# pre-io.net
KiCad netlist of a schematic drawn in EAGLE
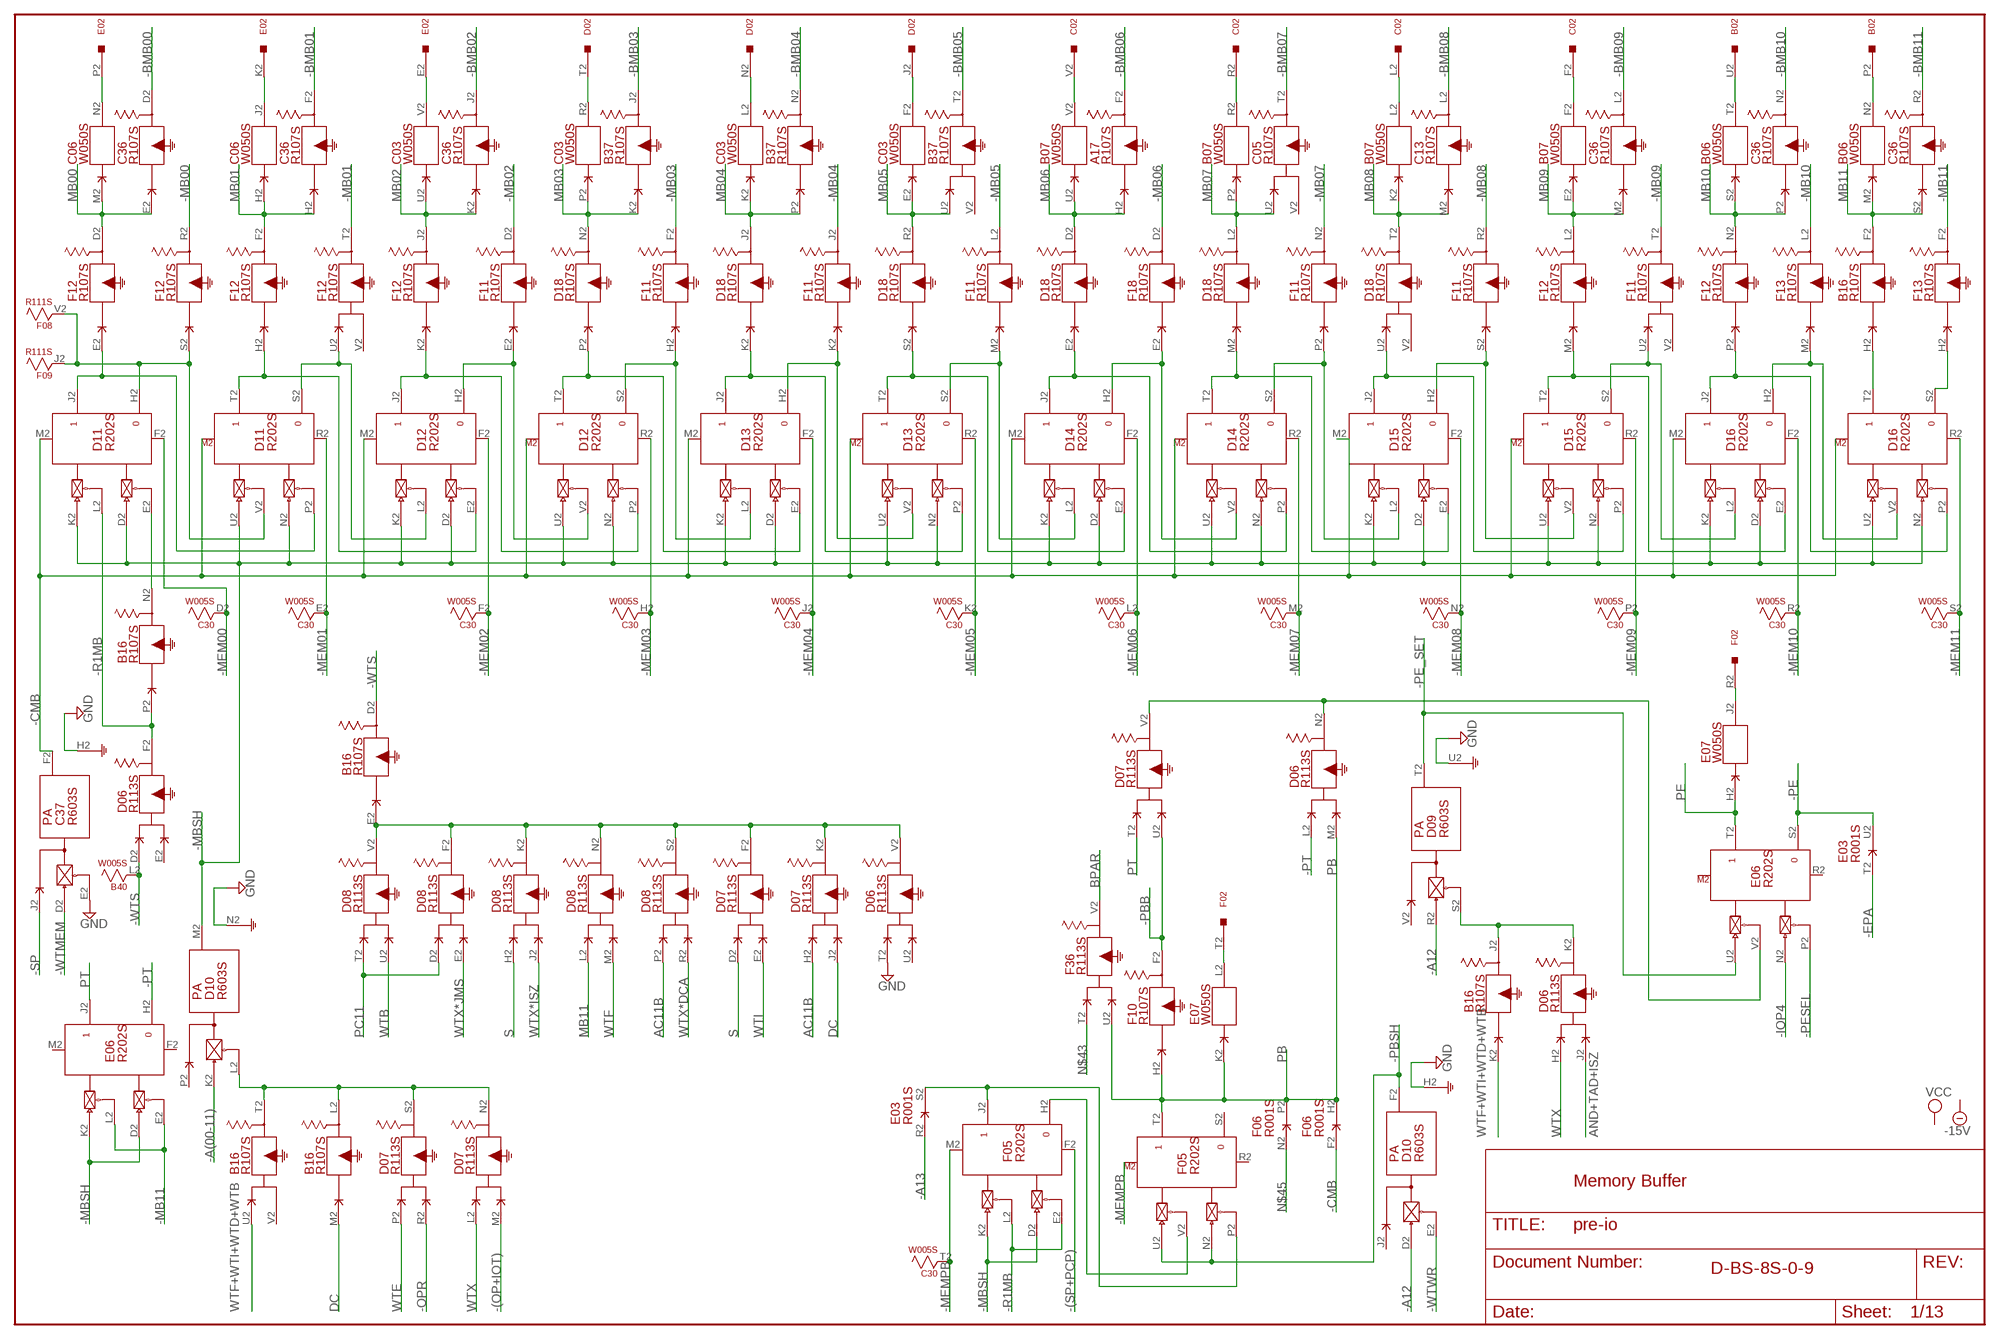
[diagram p0: schematic, sheet 1]
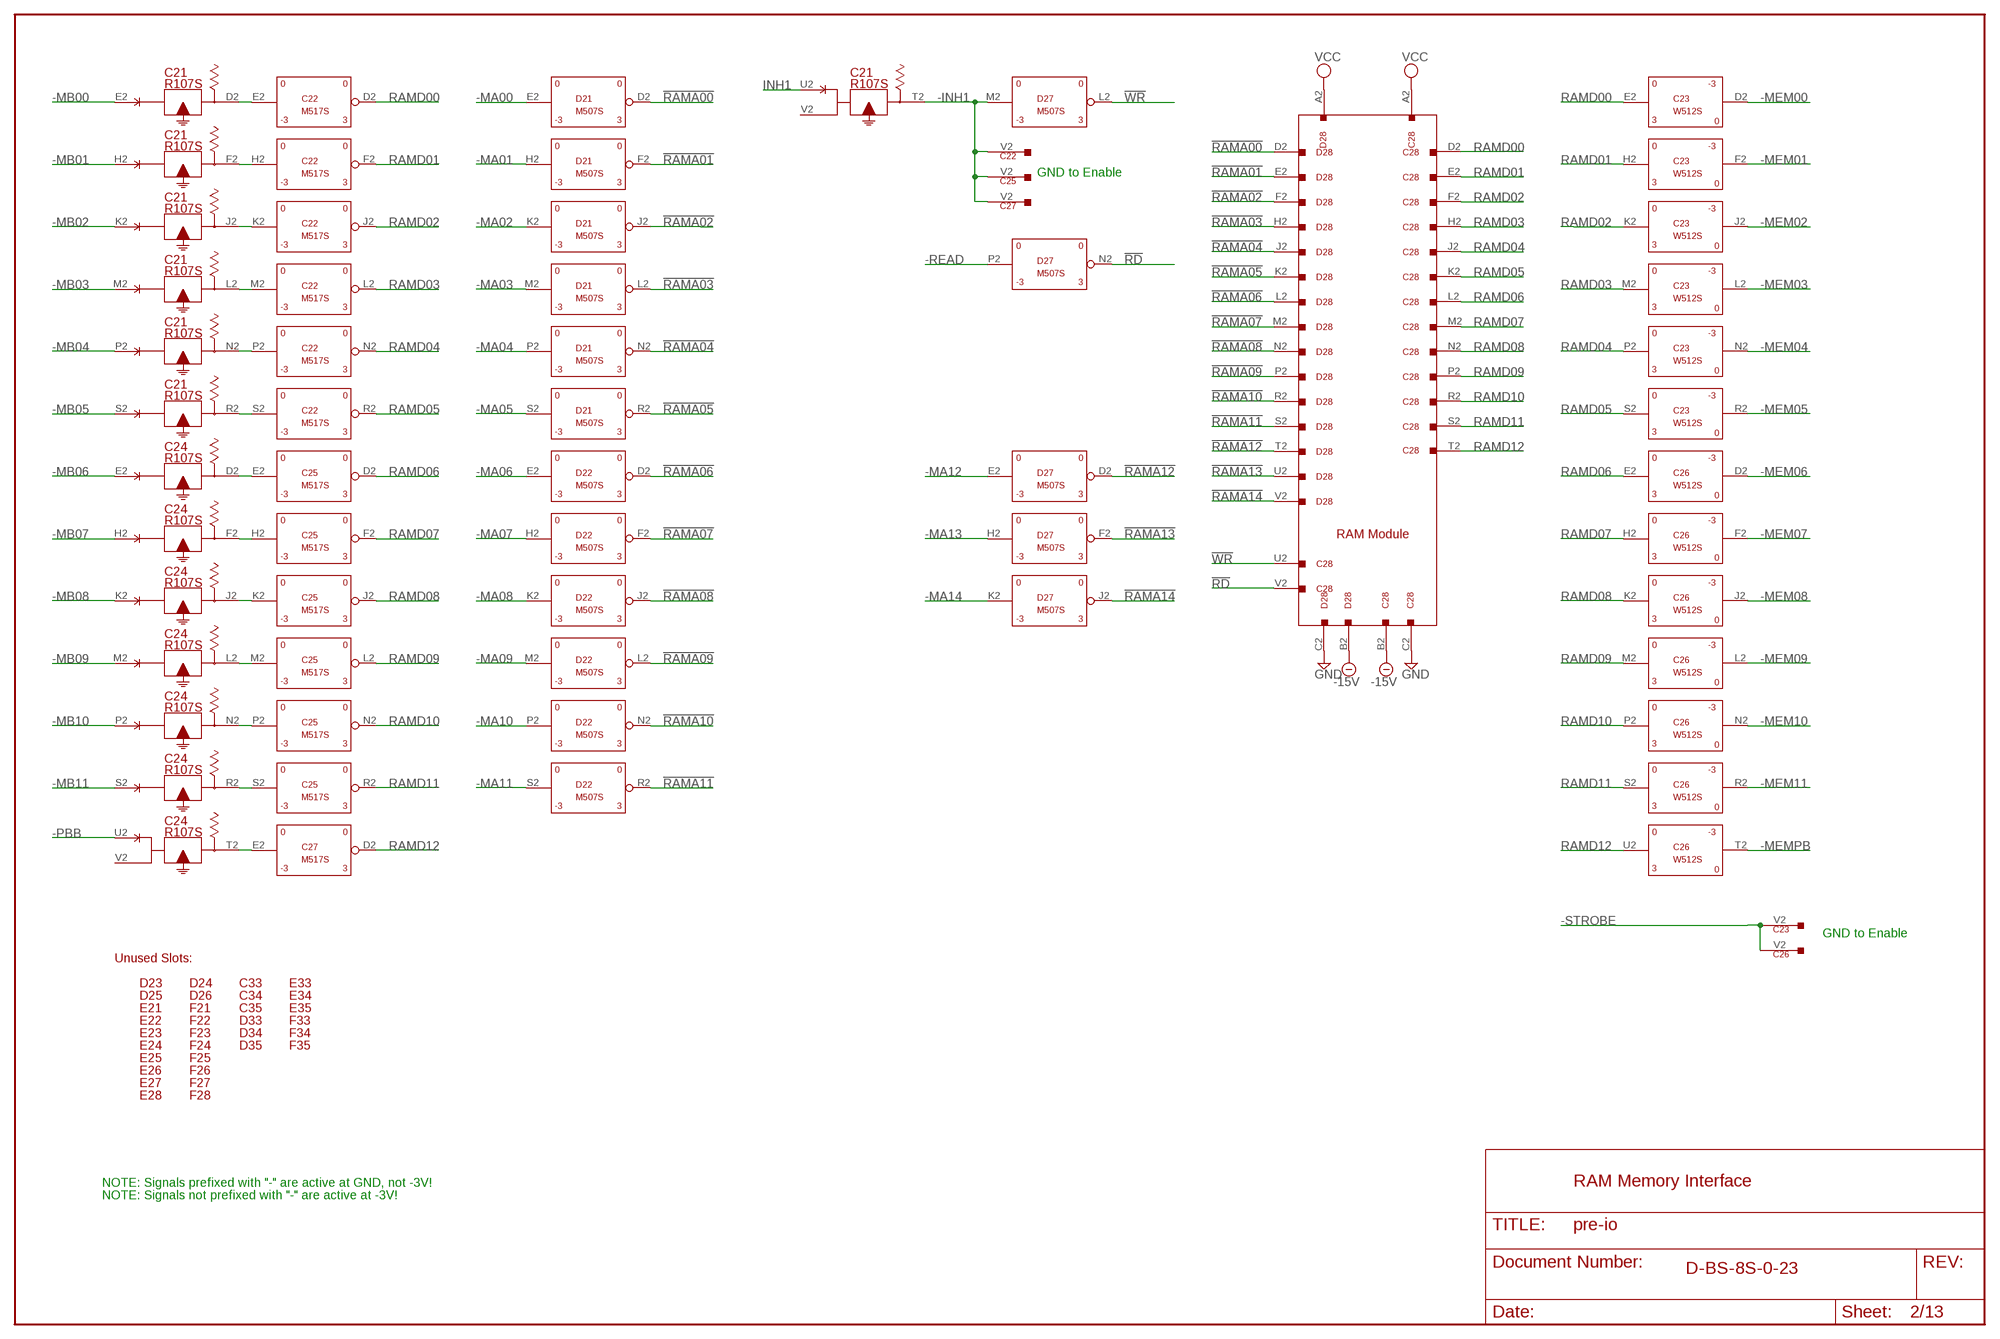
[diagram p1: schematic, sheet 2]
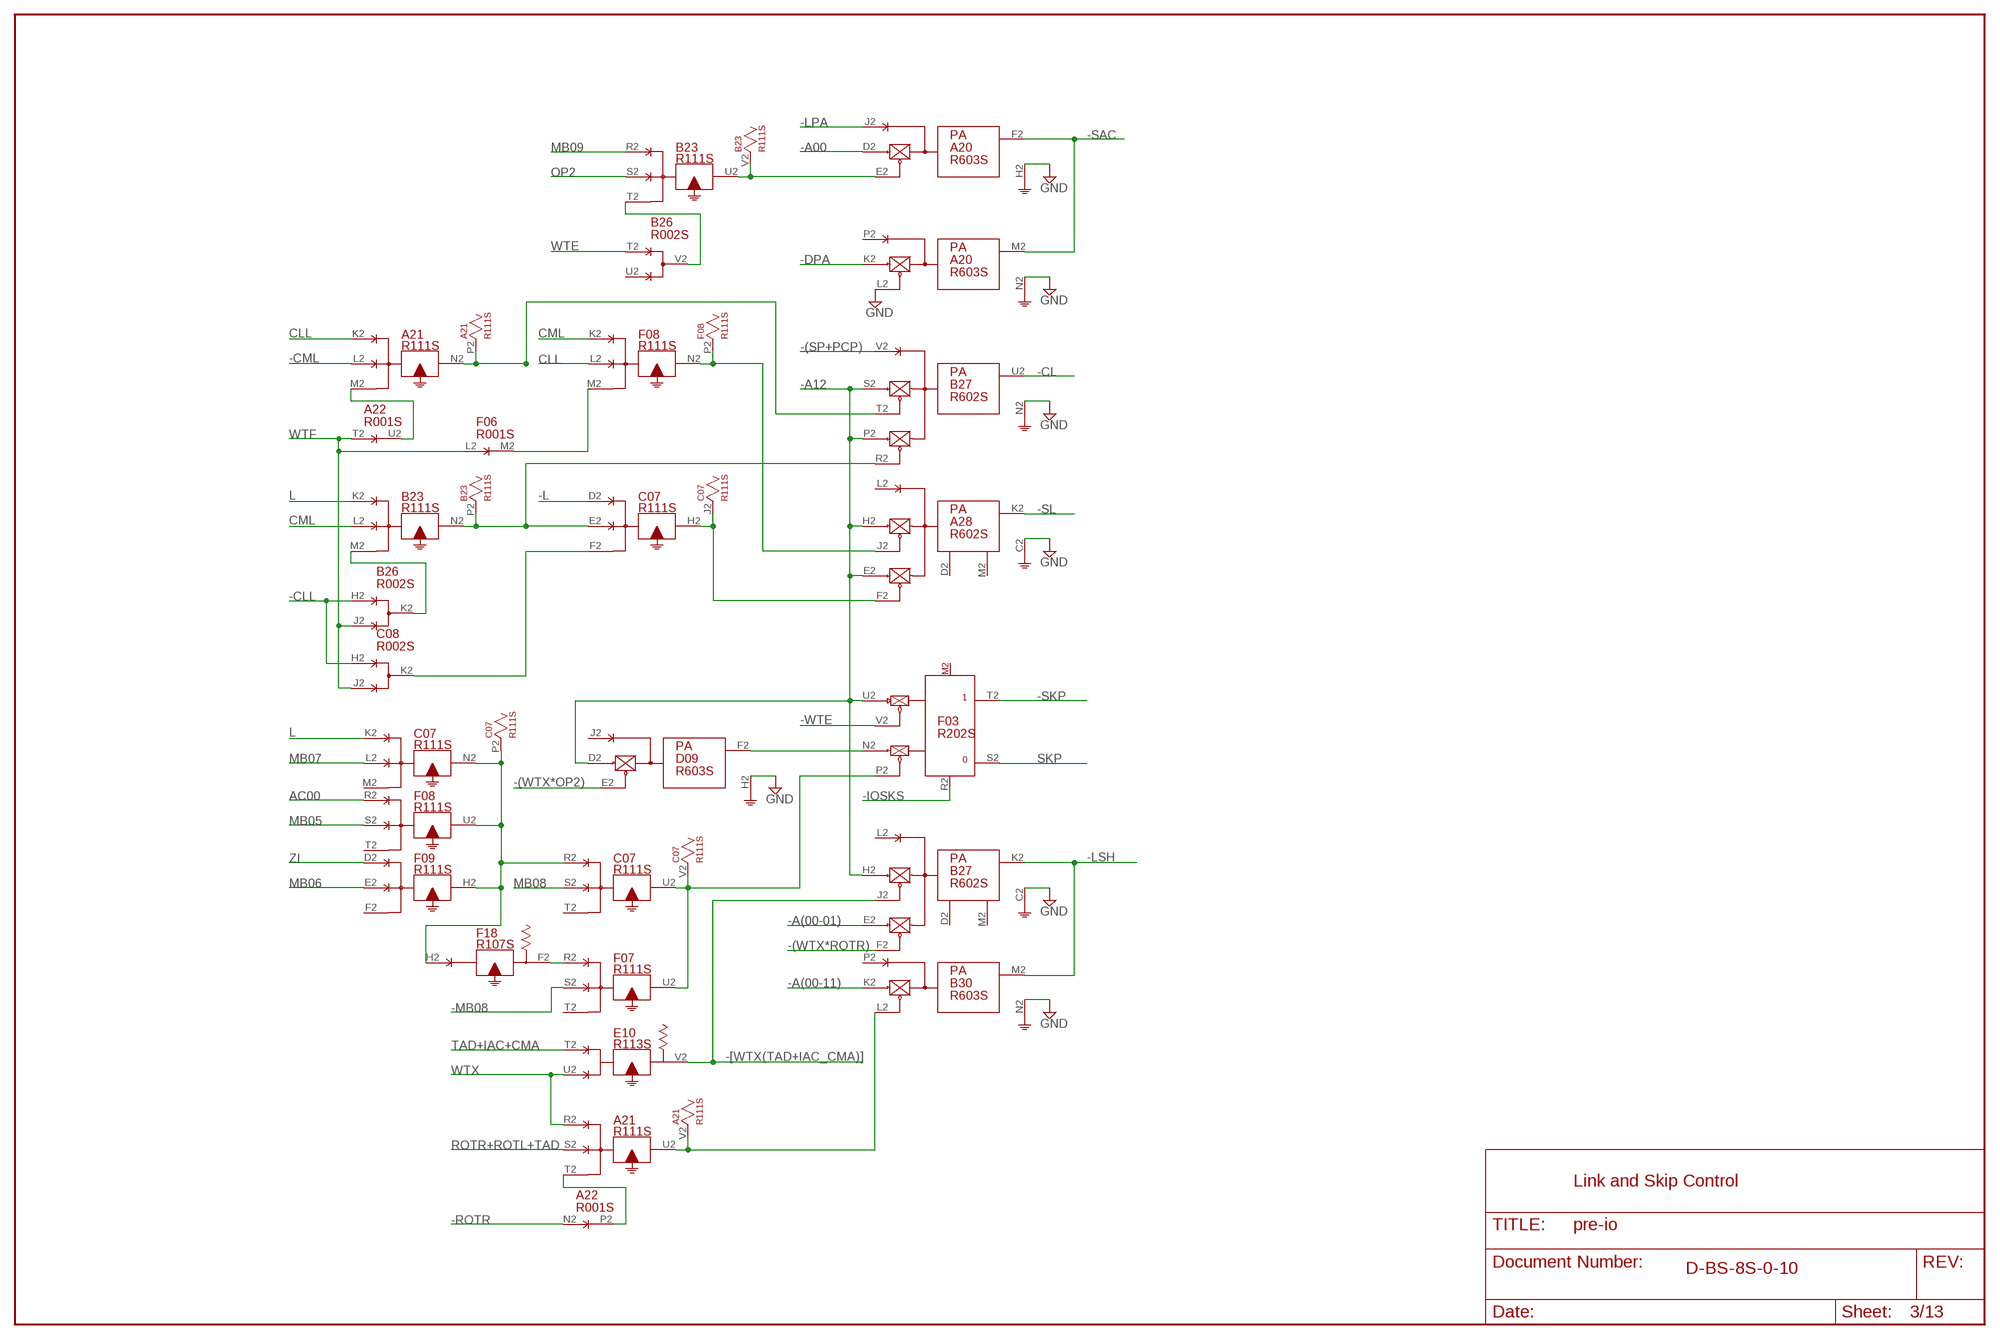
[diagram p2: schematic, sheet 3]
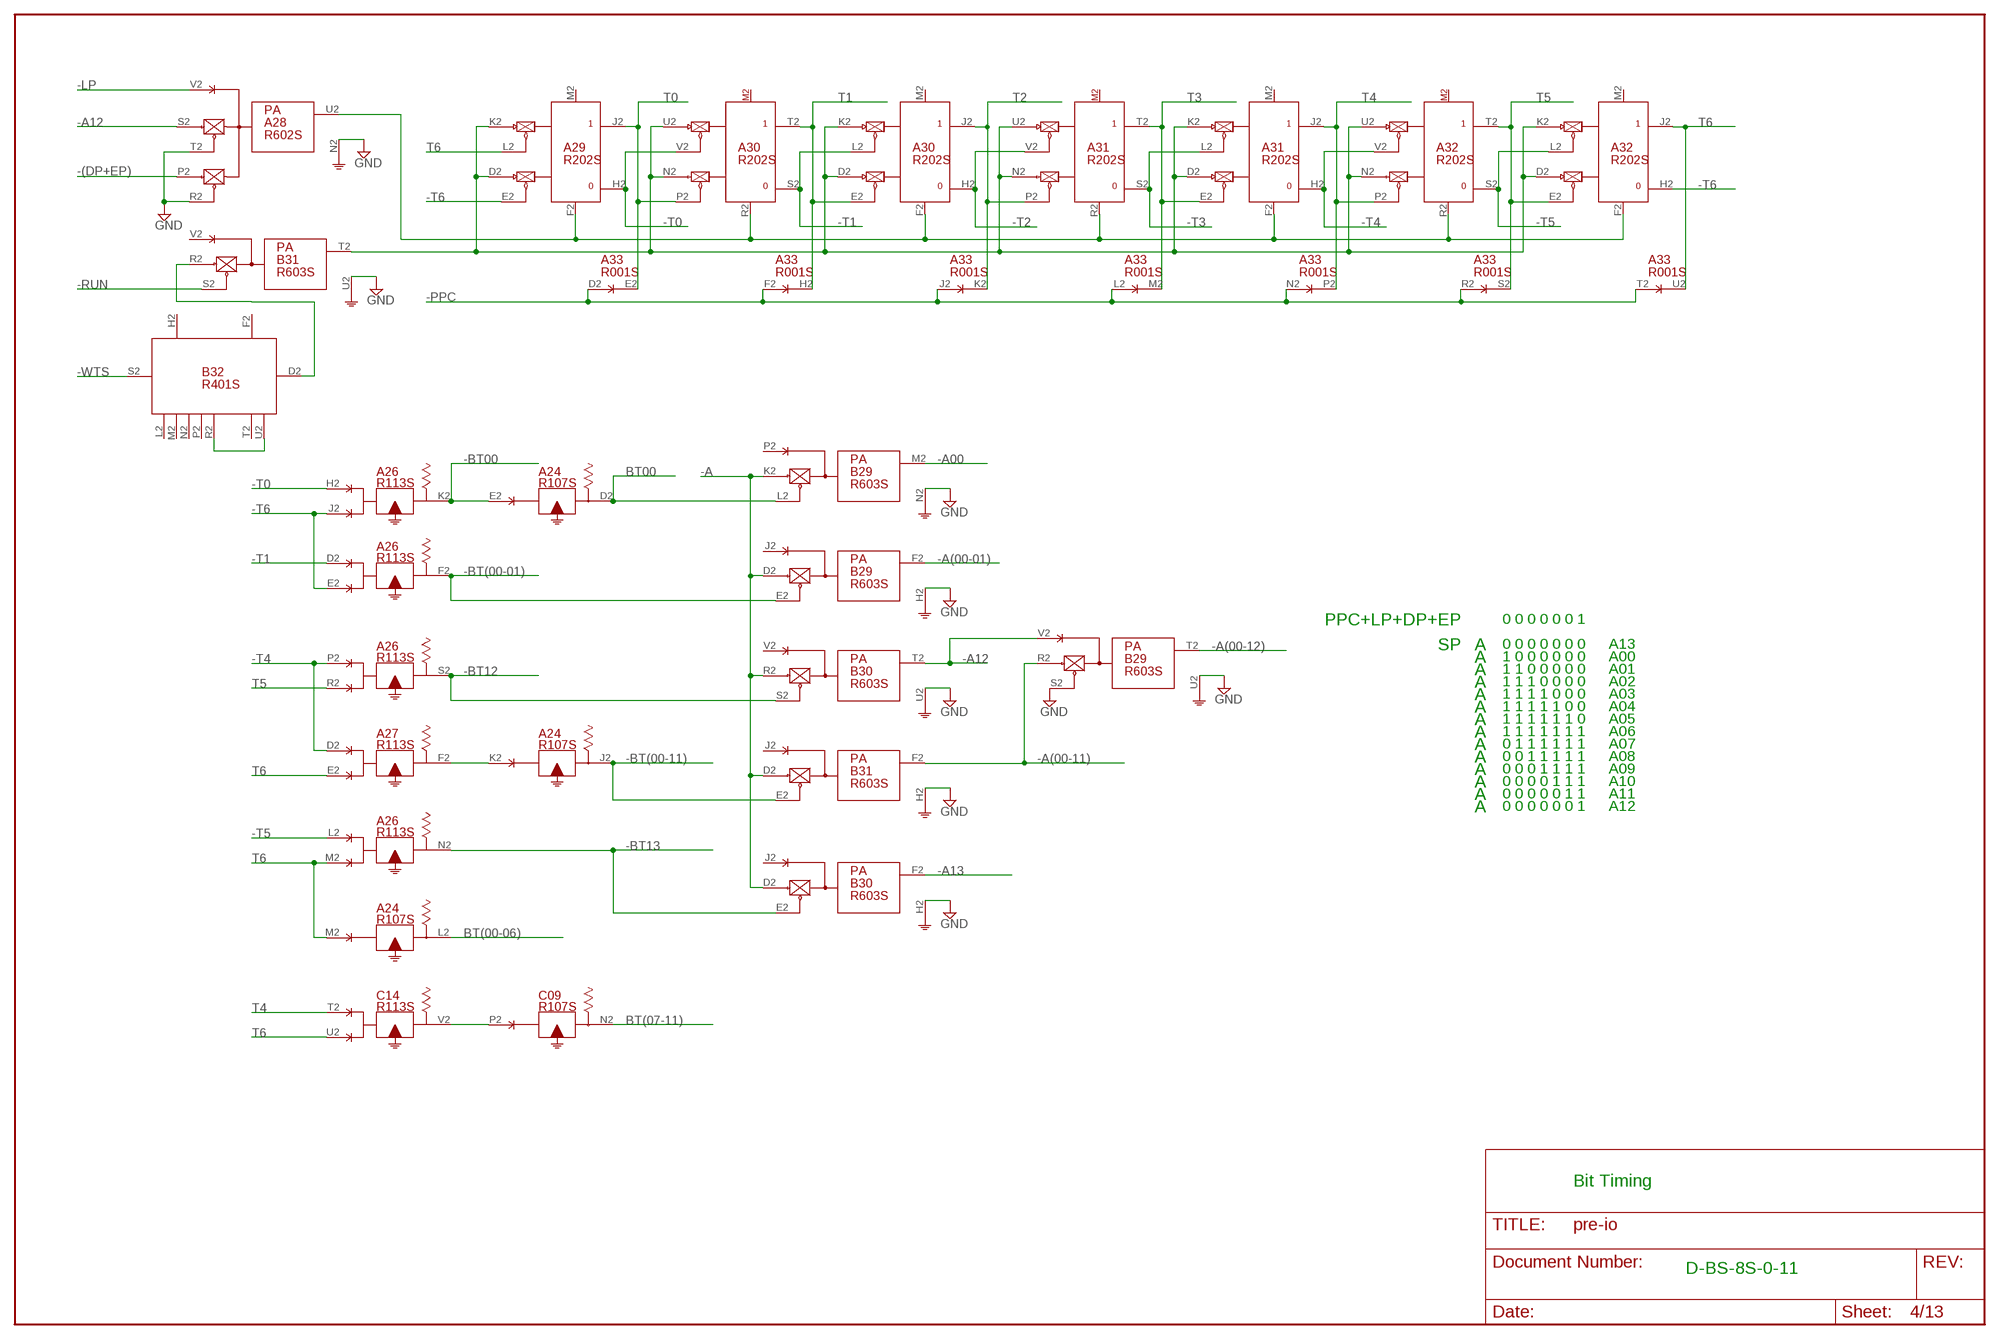
[diagram p3: schematic, sheet 4]
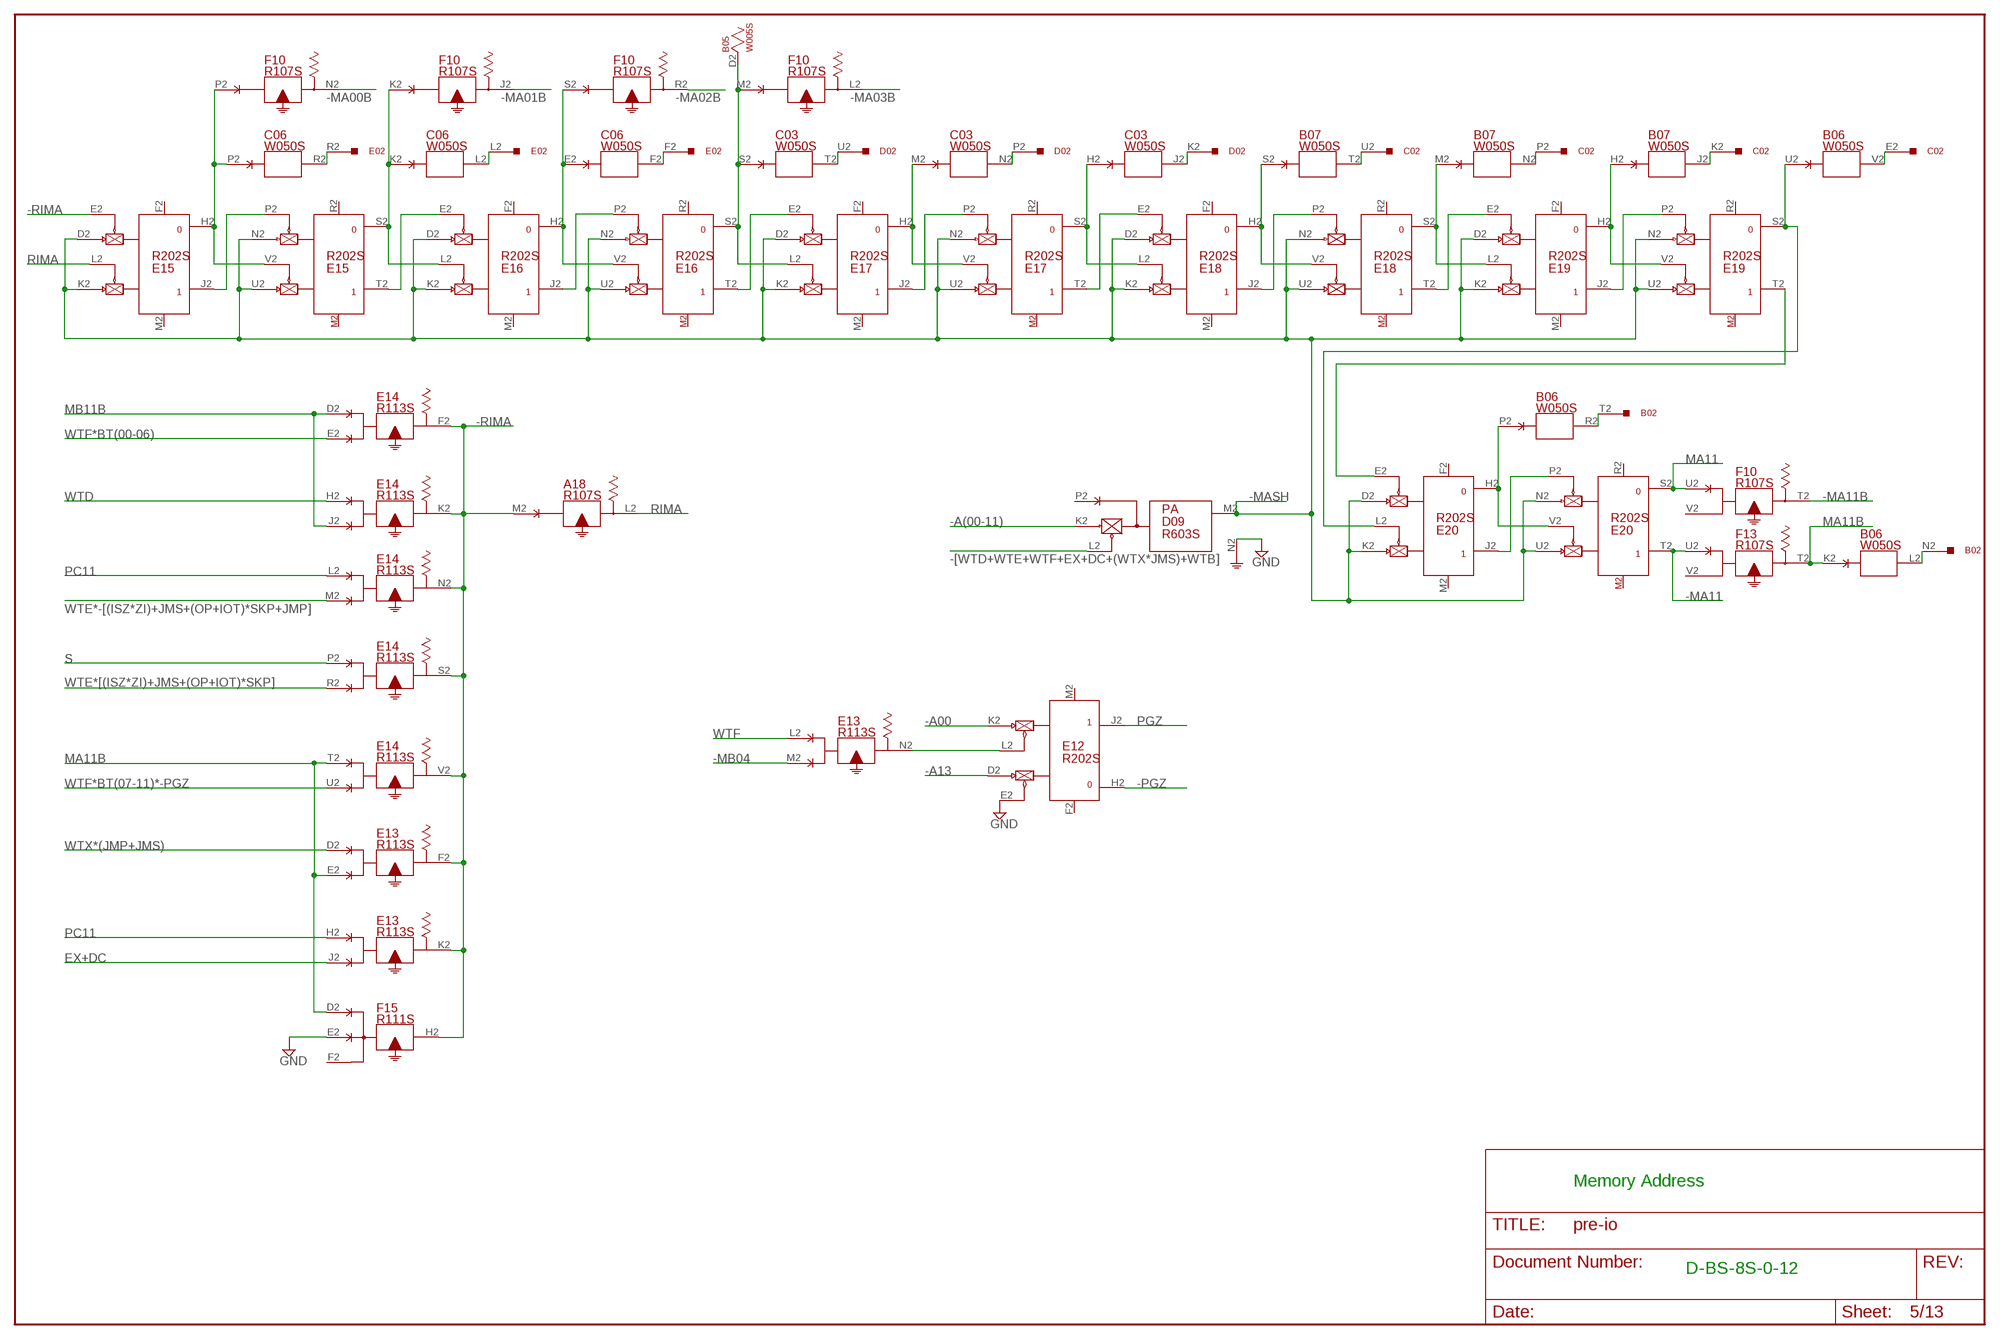
[diagram p4: schematic, sheet 5]
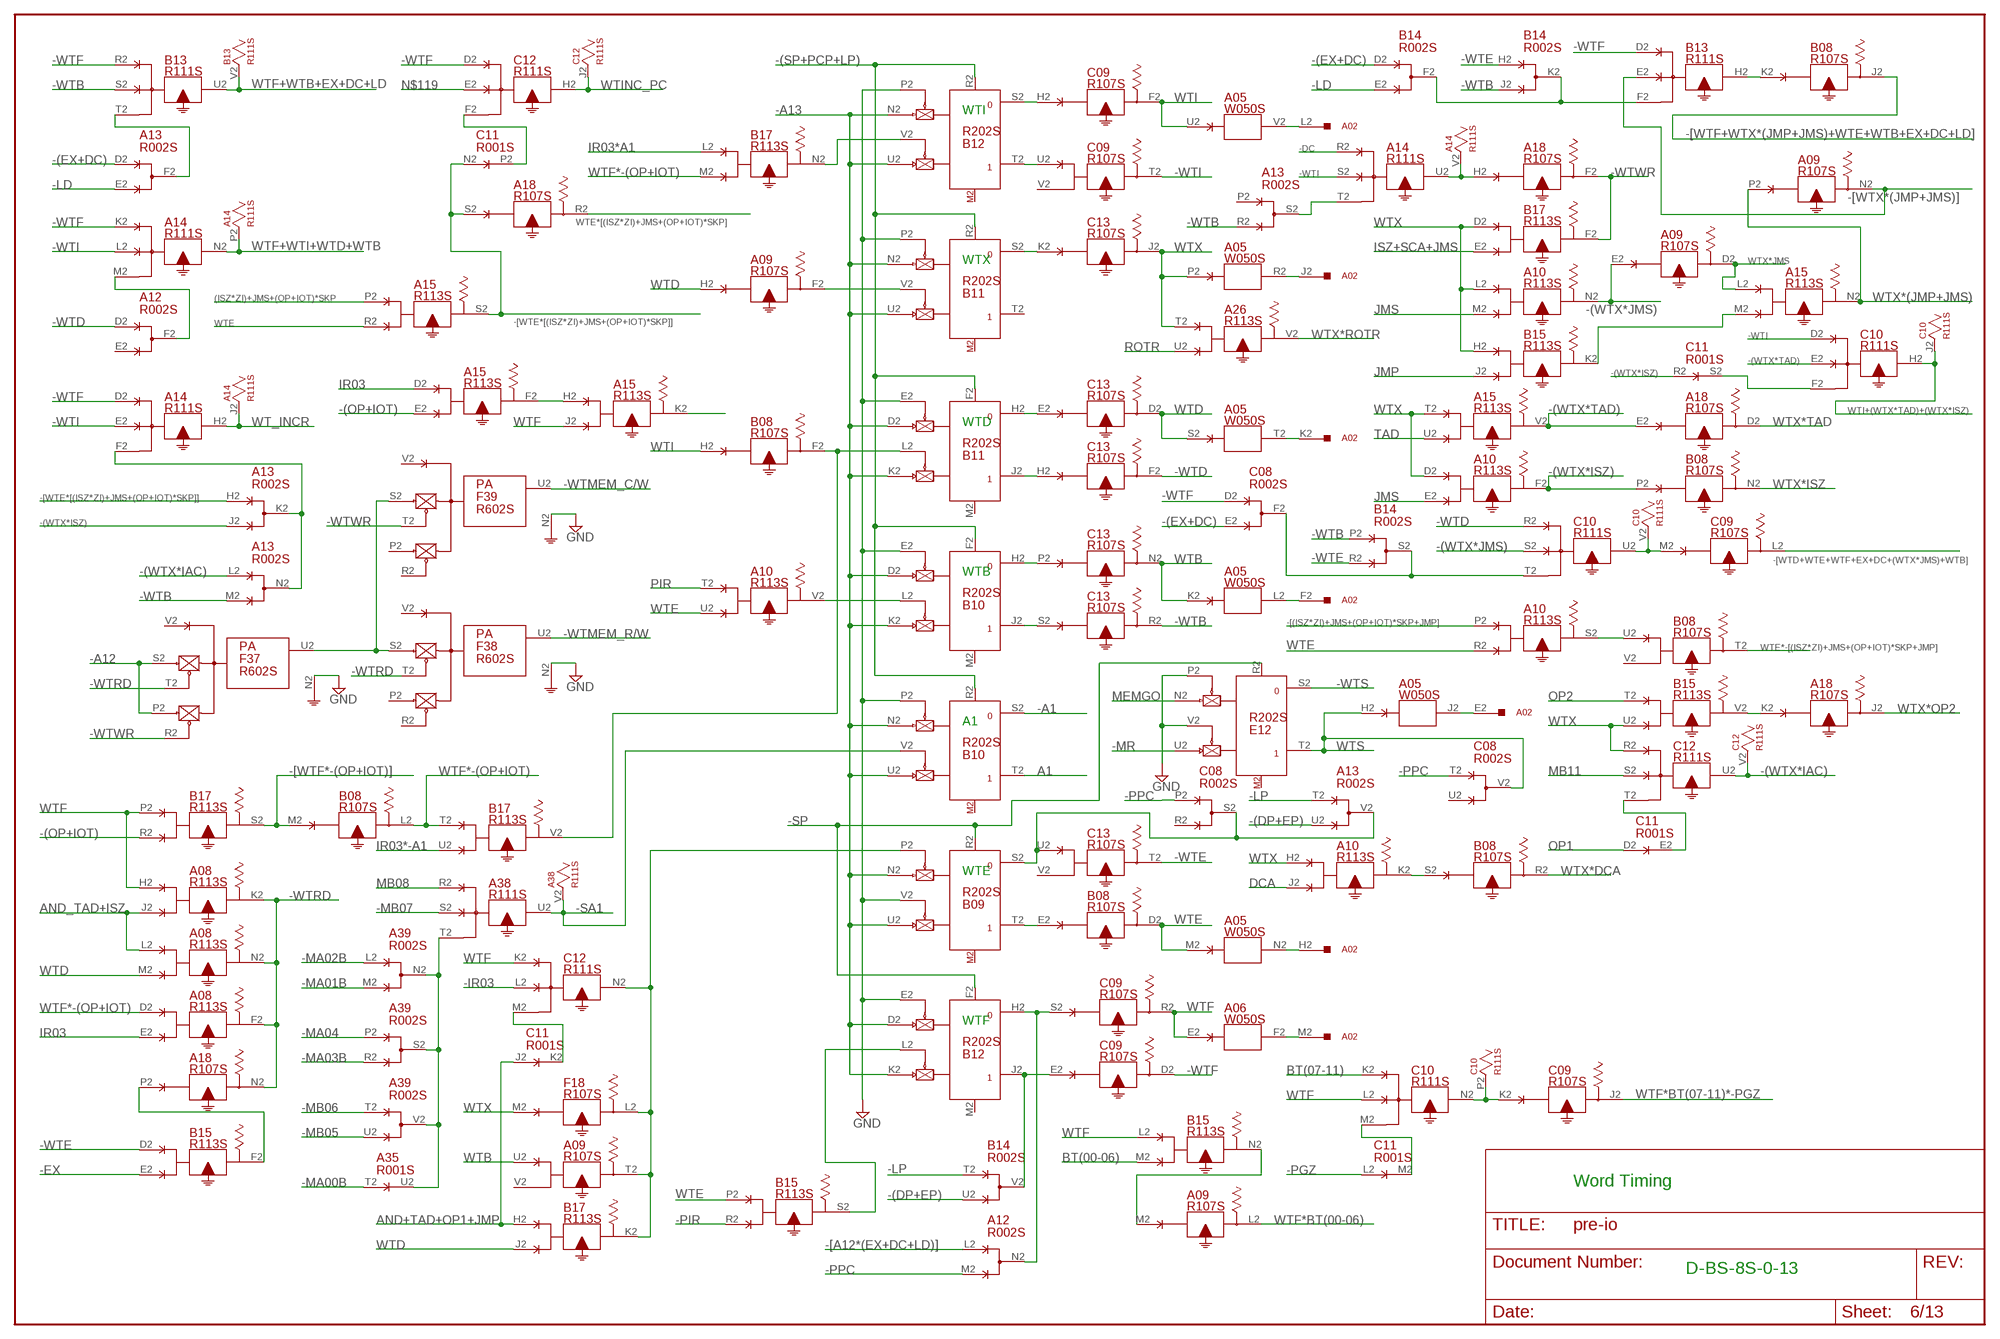
[diagram p5: schematic, sheet 6]
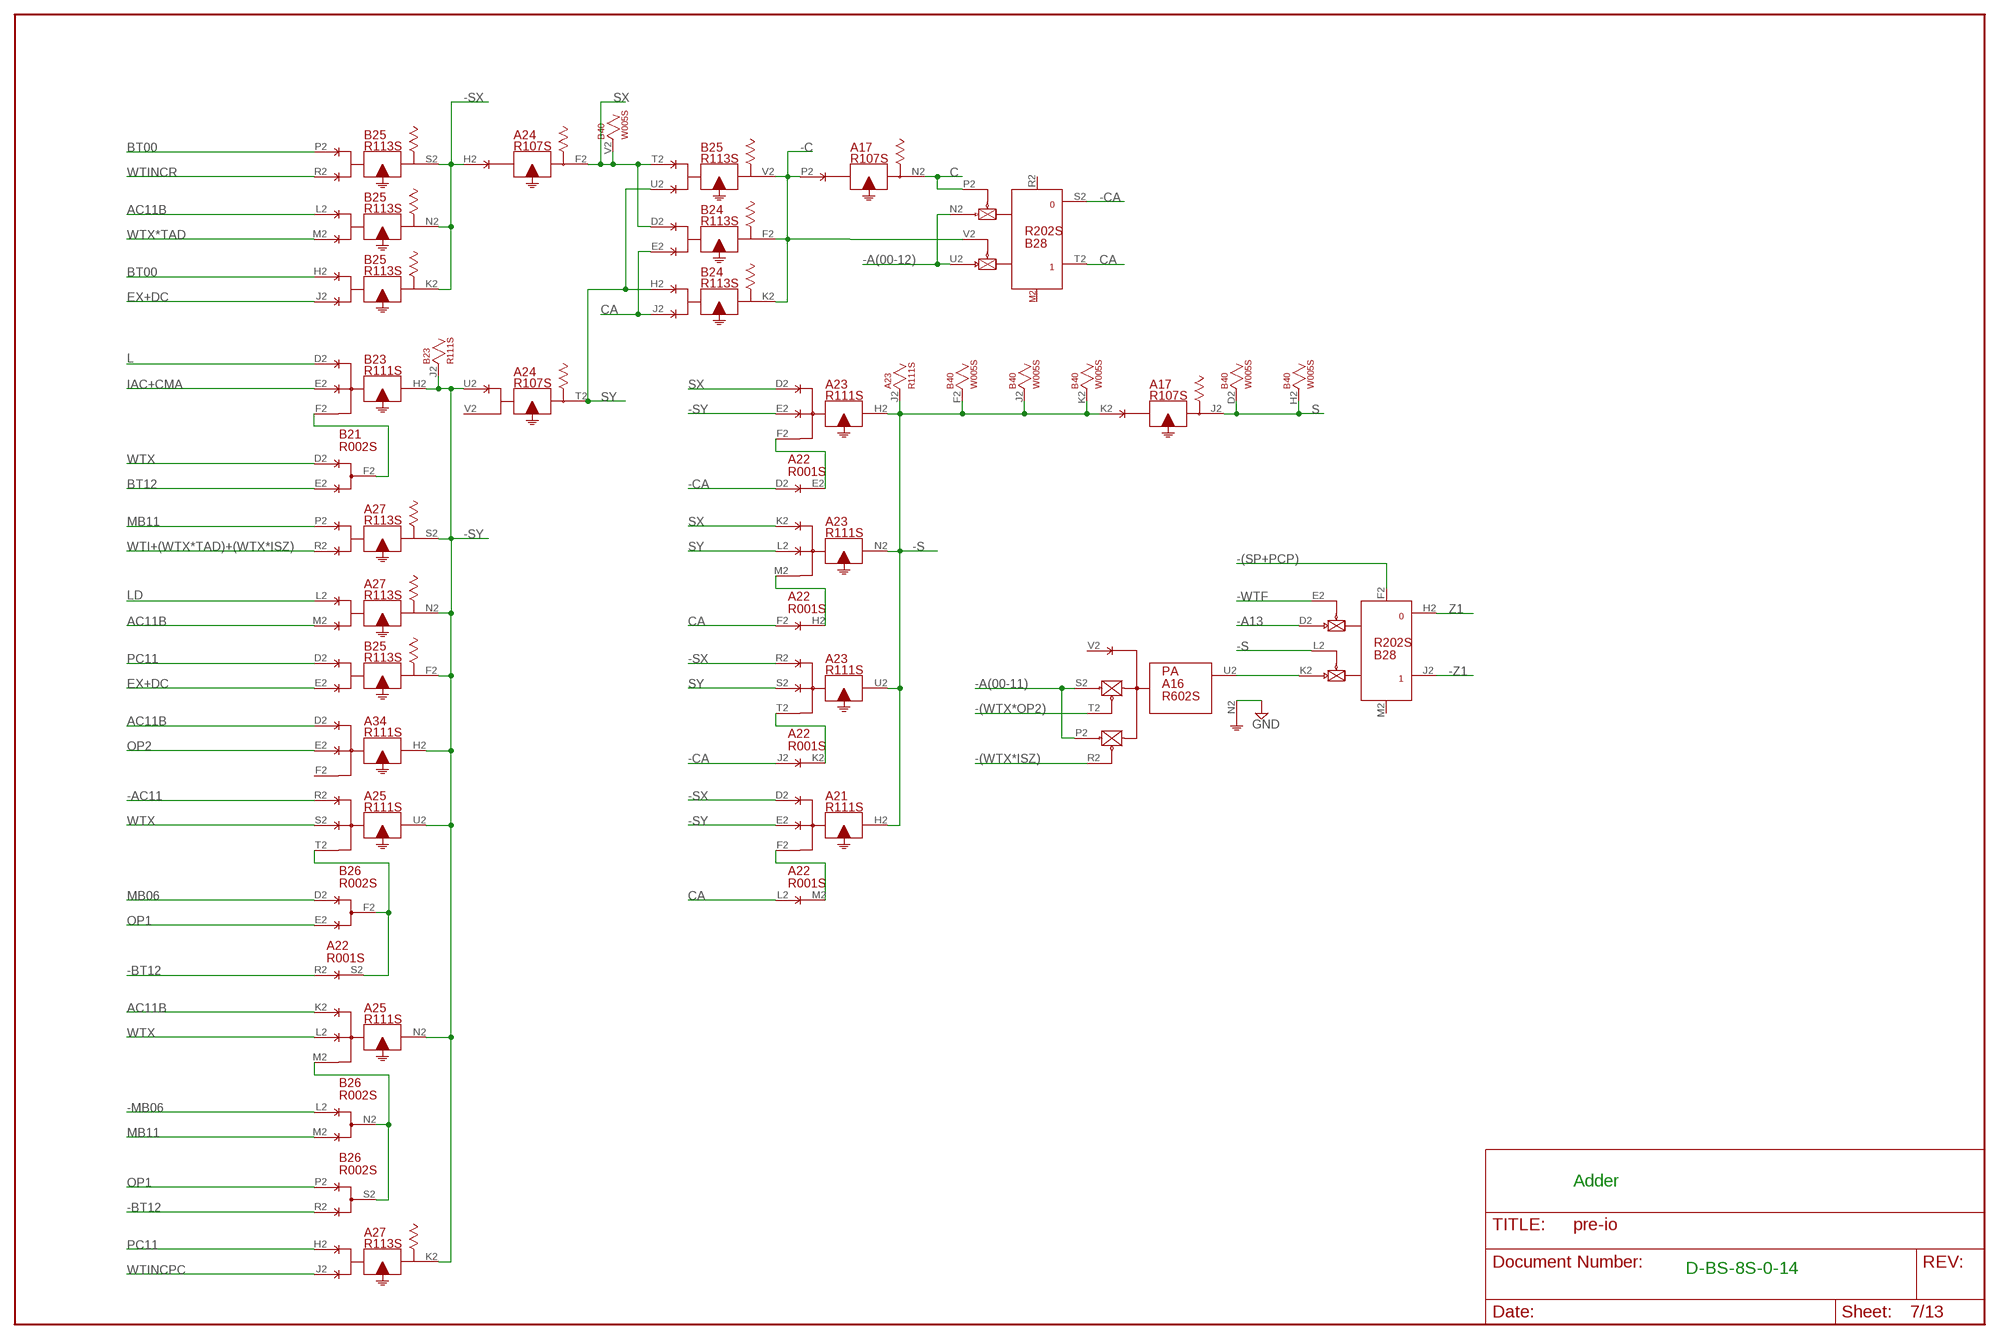
[diagram p6: schematic, sheet 7]
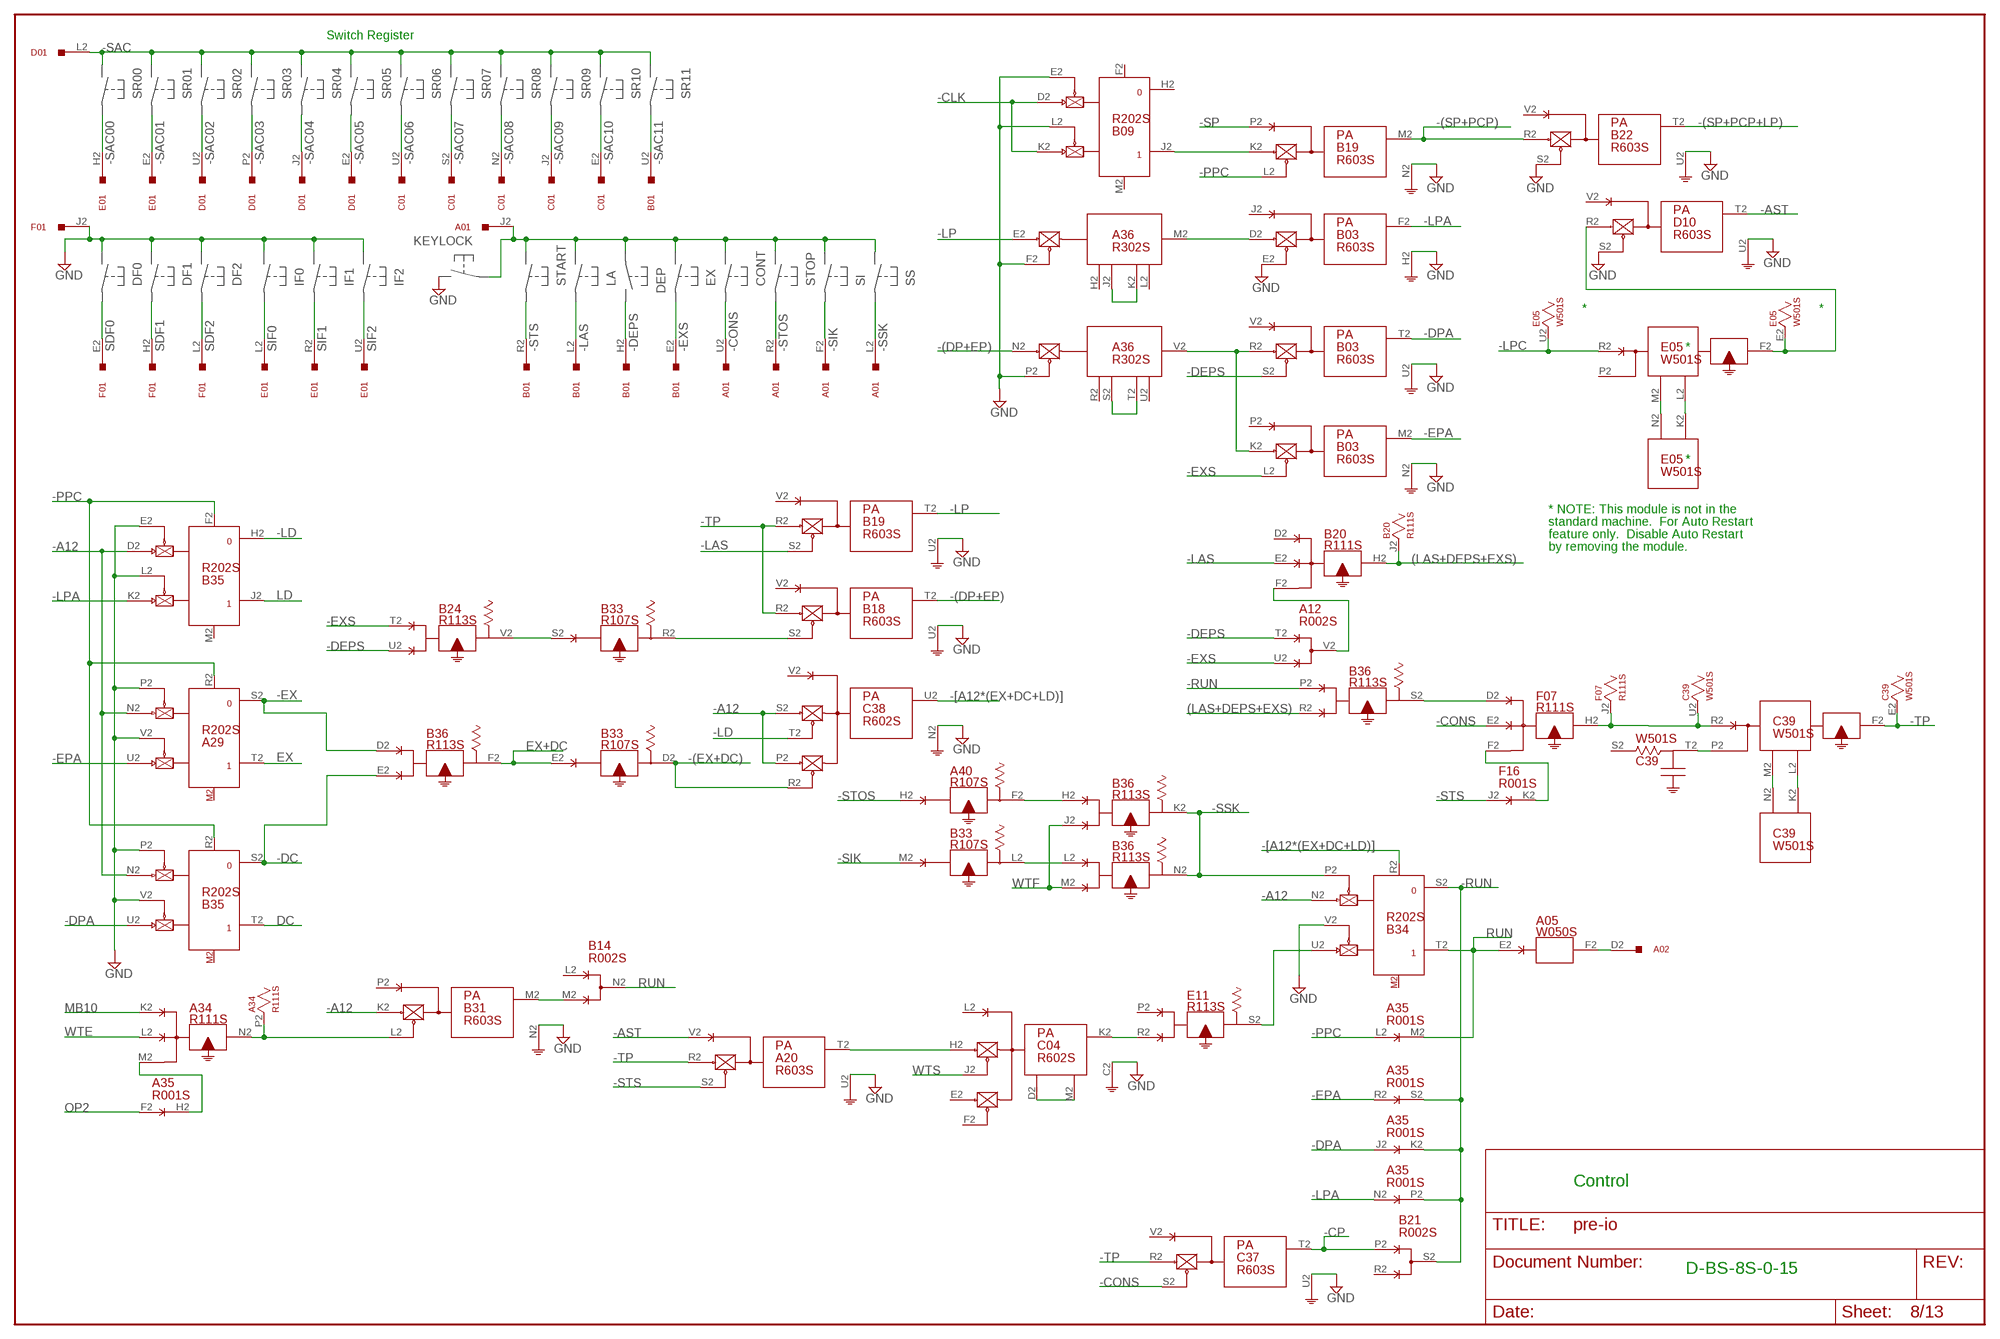
[diagram p7: schematic, sheet 8]
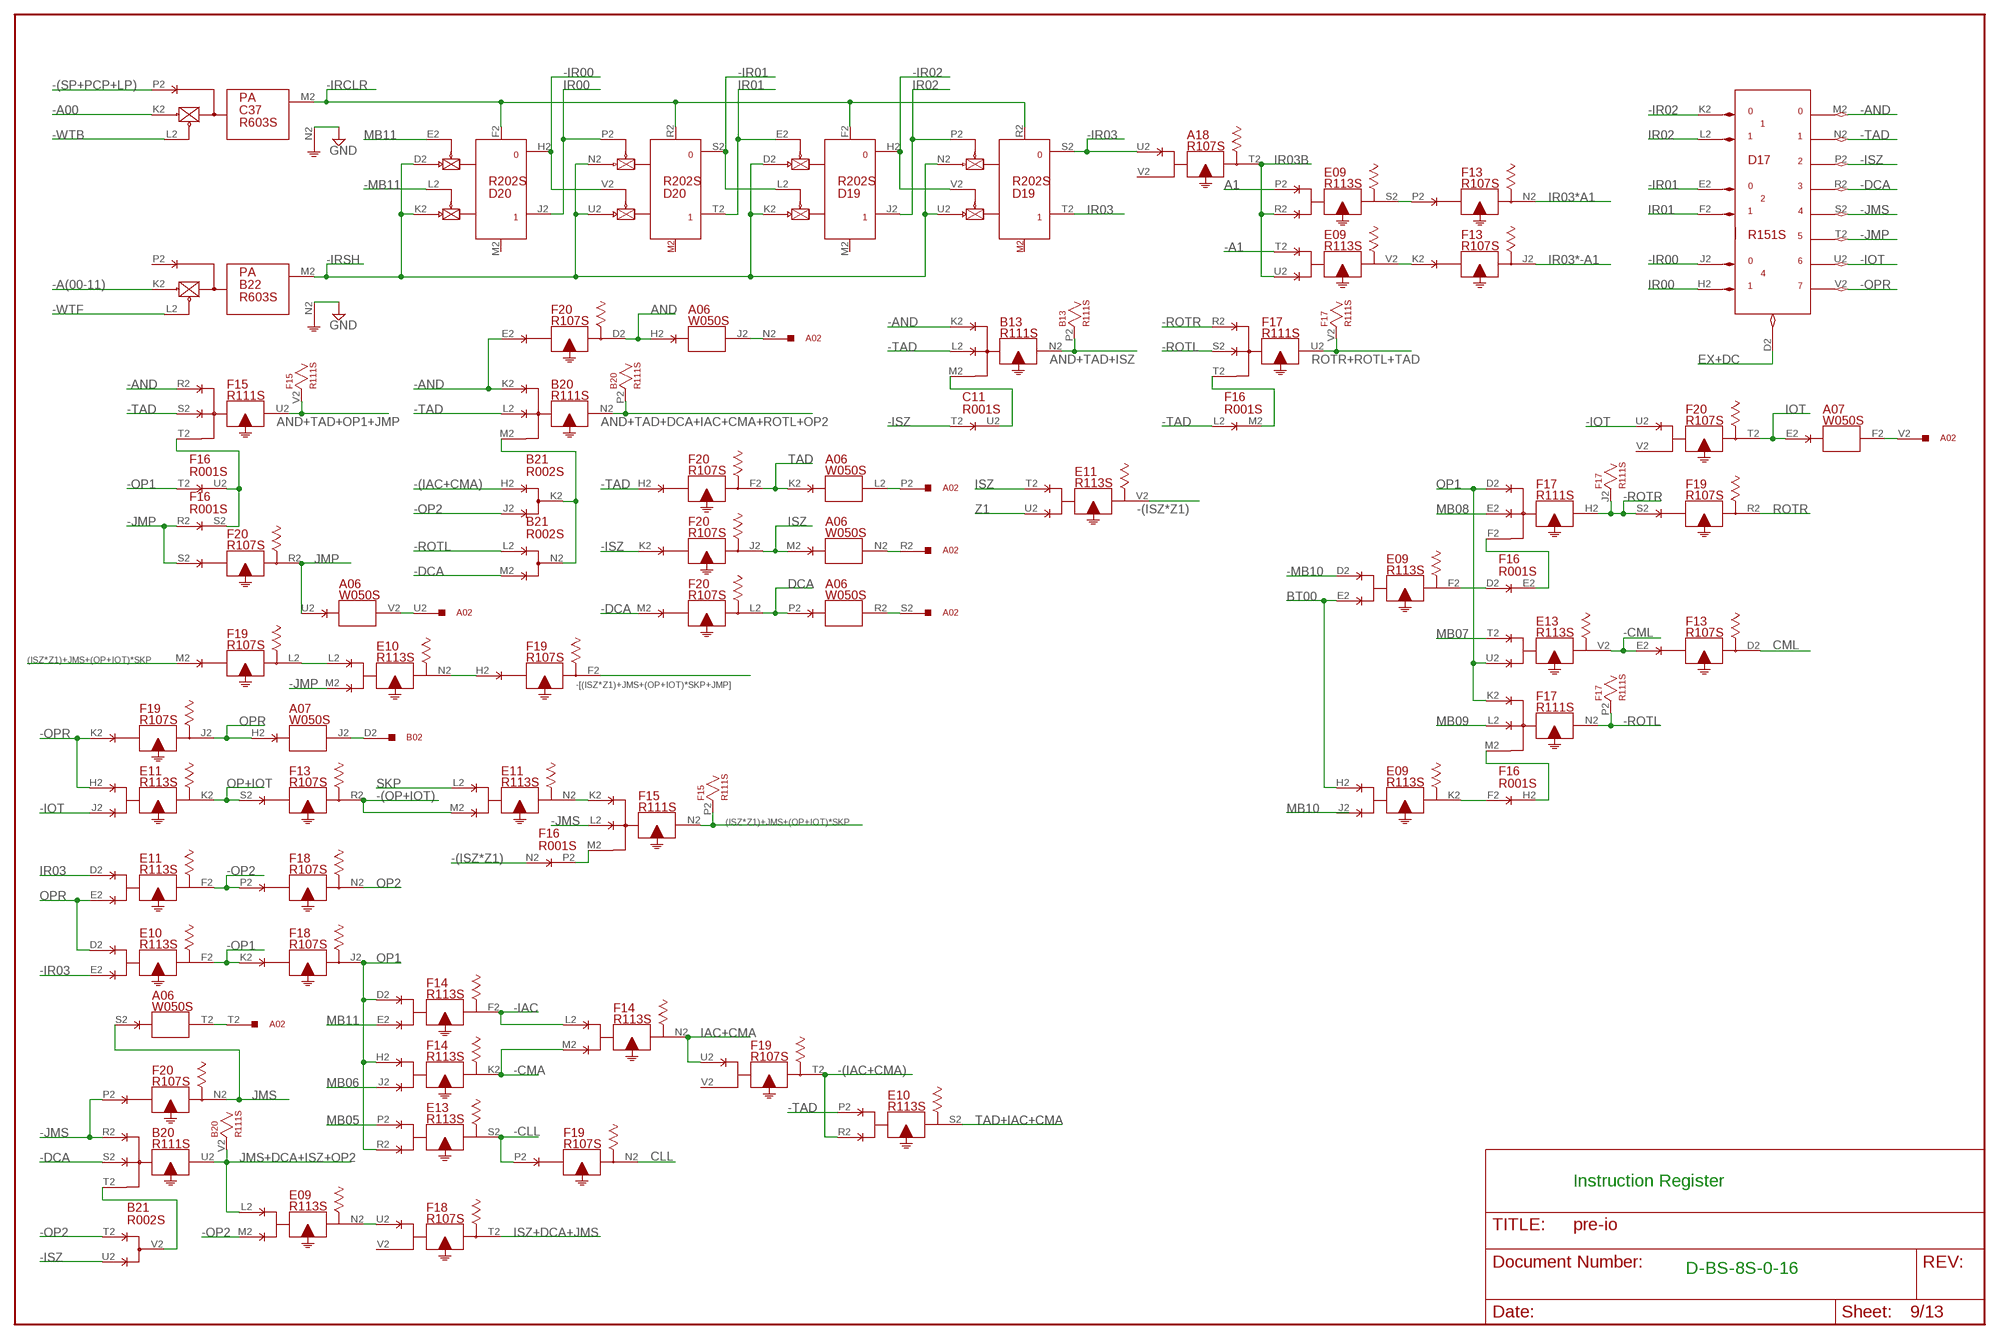
[diagram p8: schematic, sheet 9]
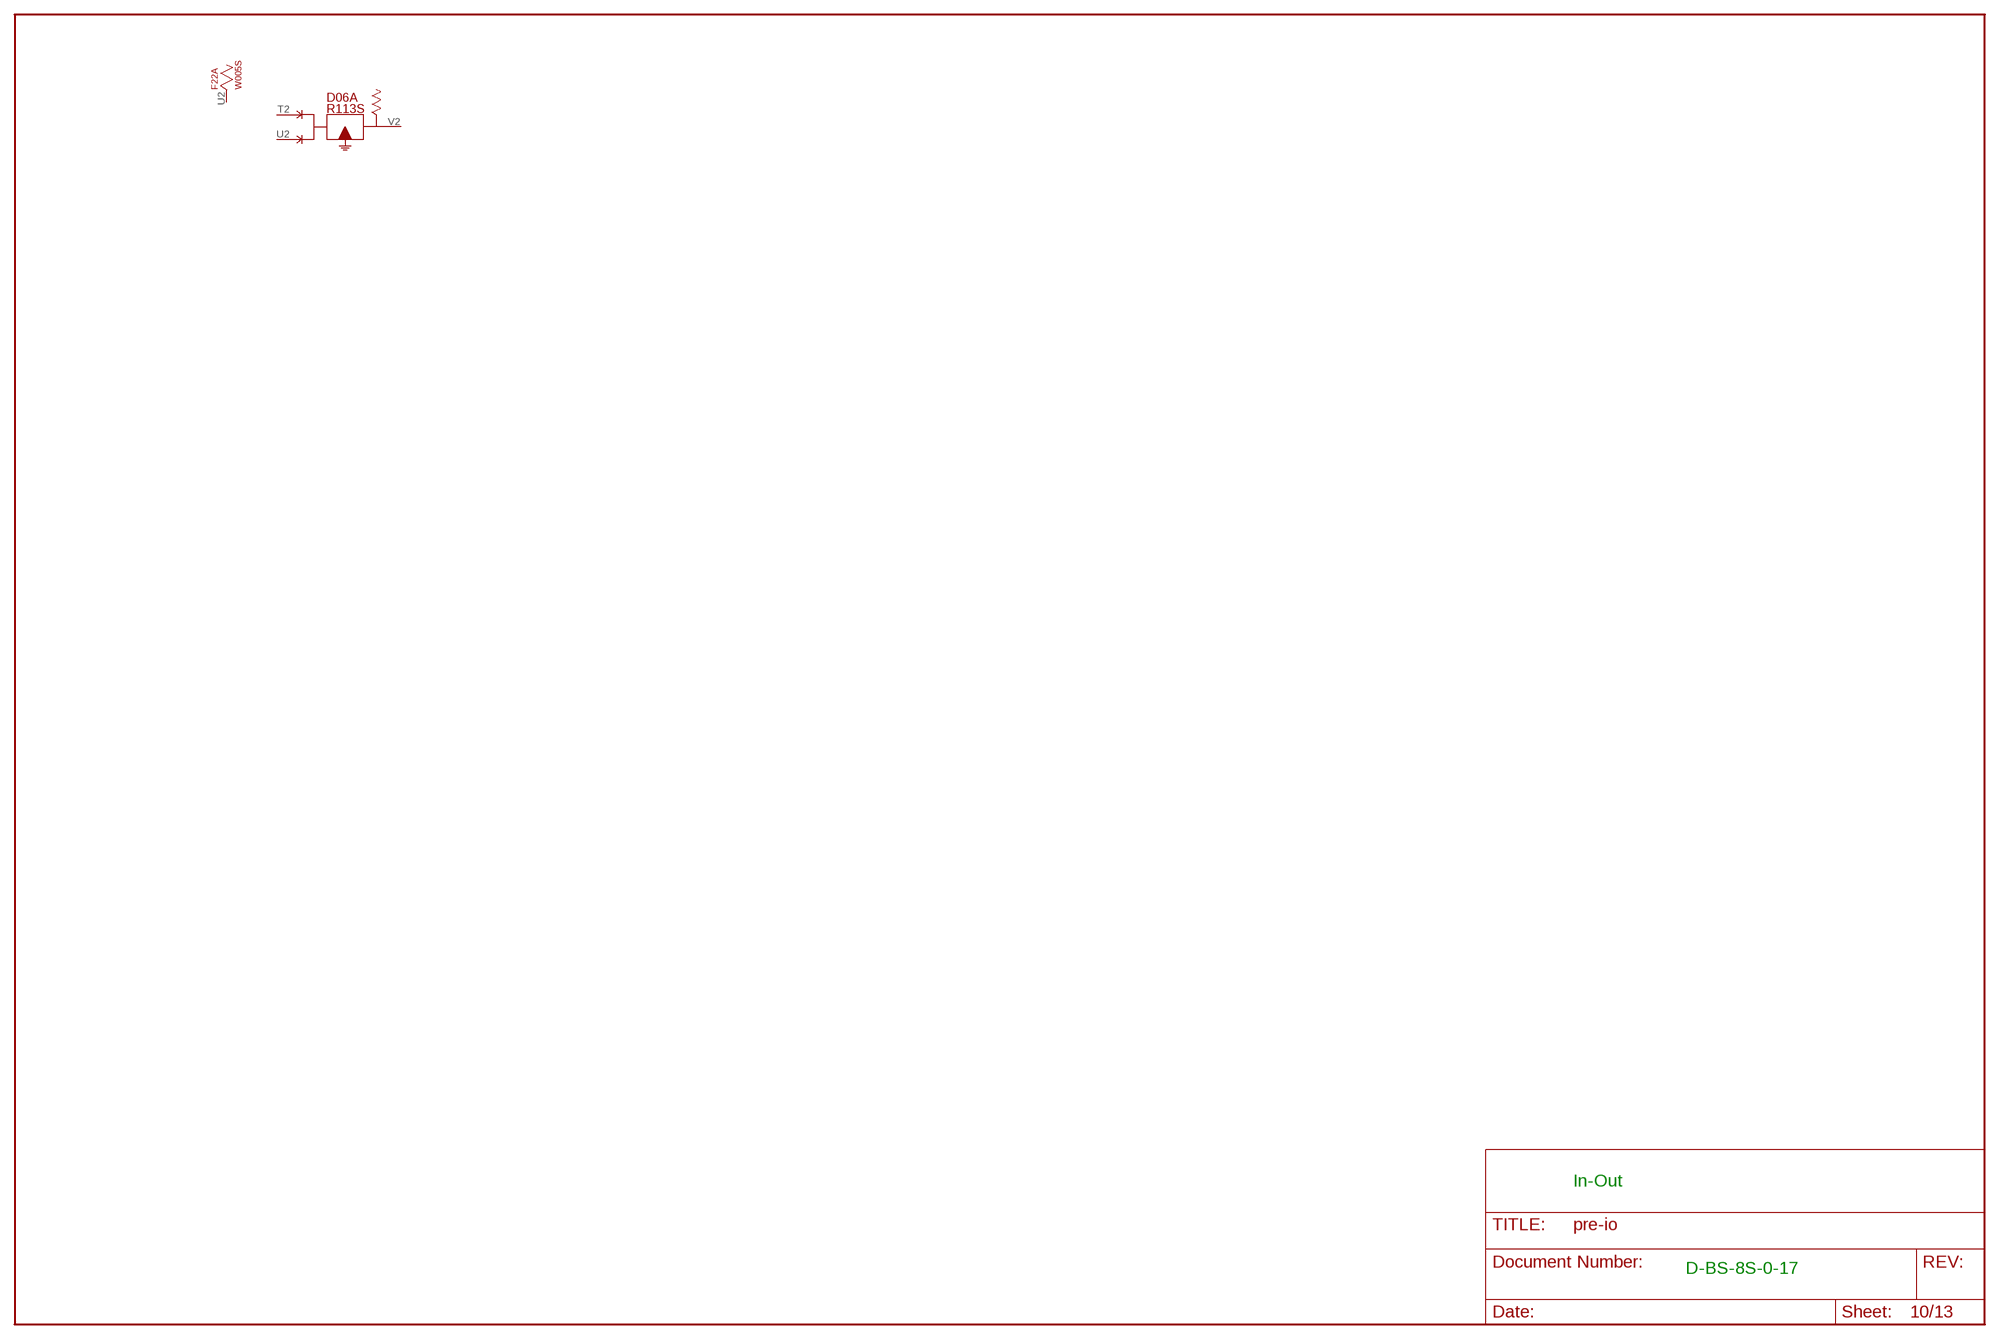
[diagram p9: schematic, sheet 10]
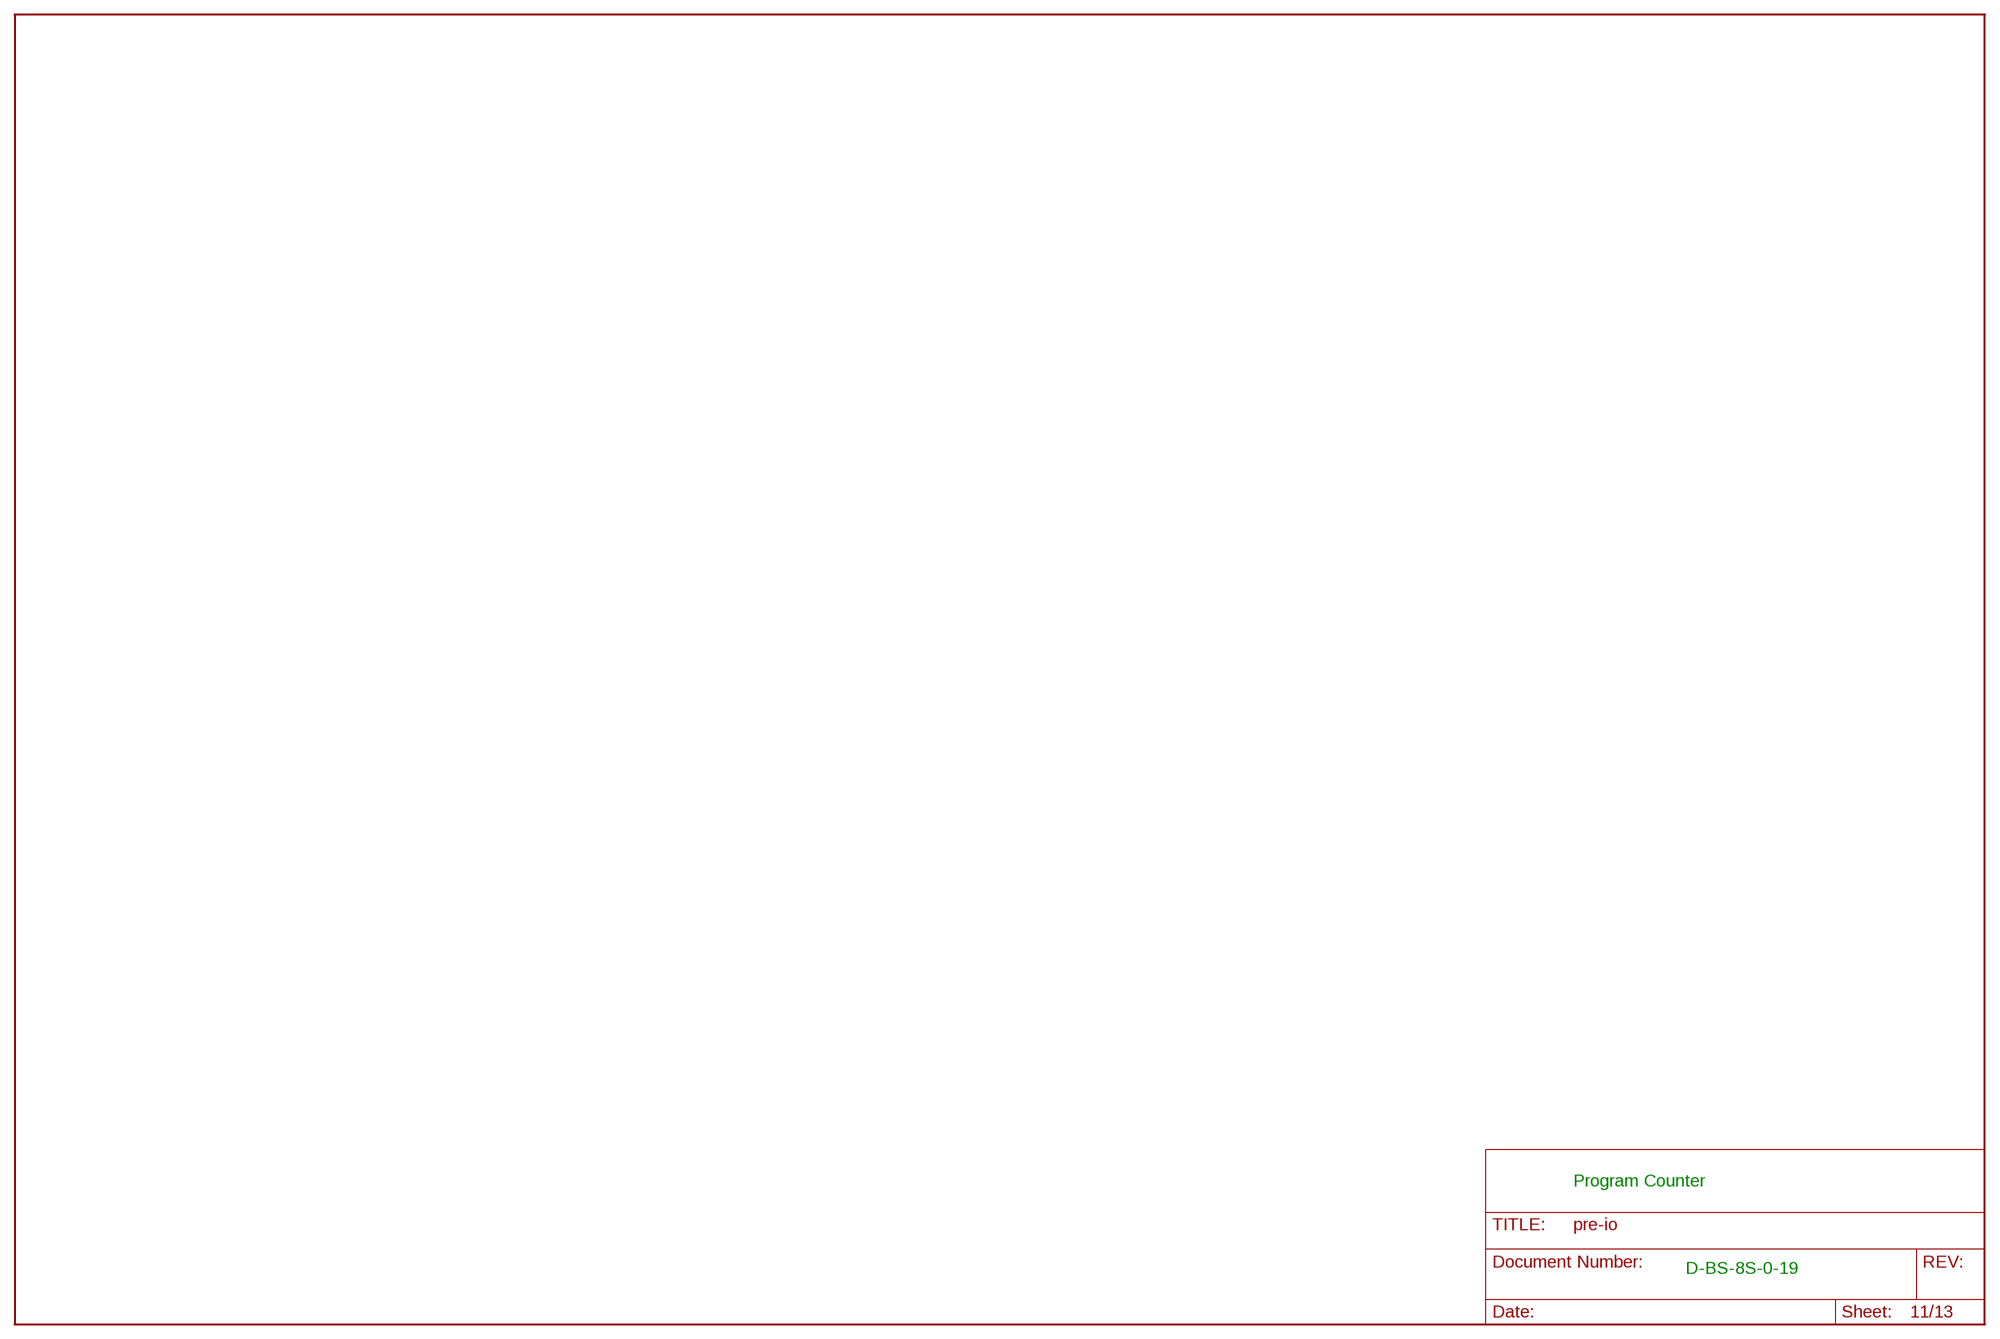
[diagram p10: schematic, sheet 11]
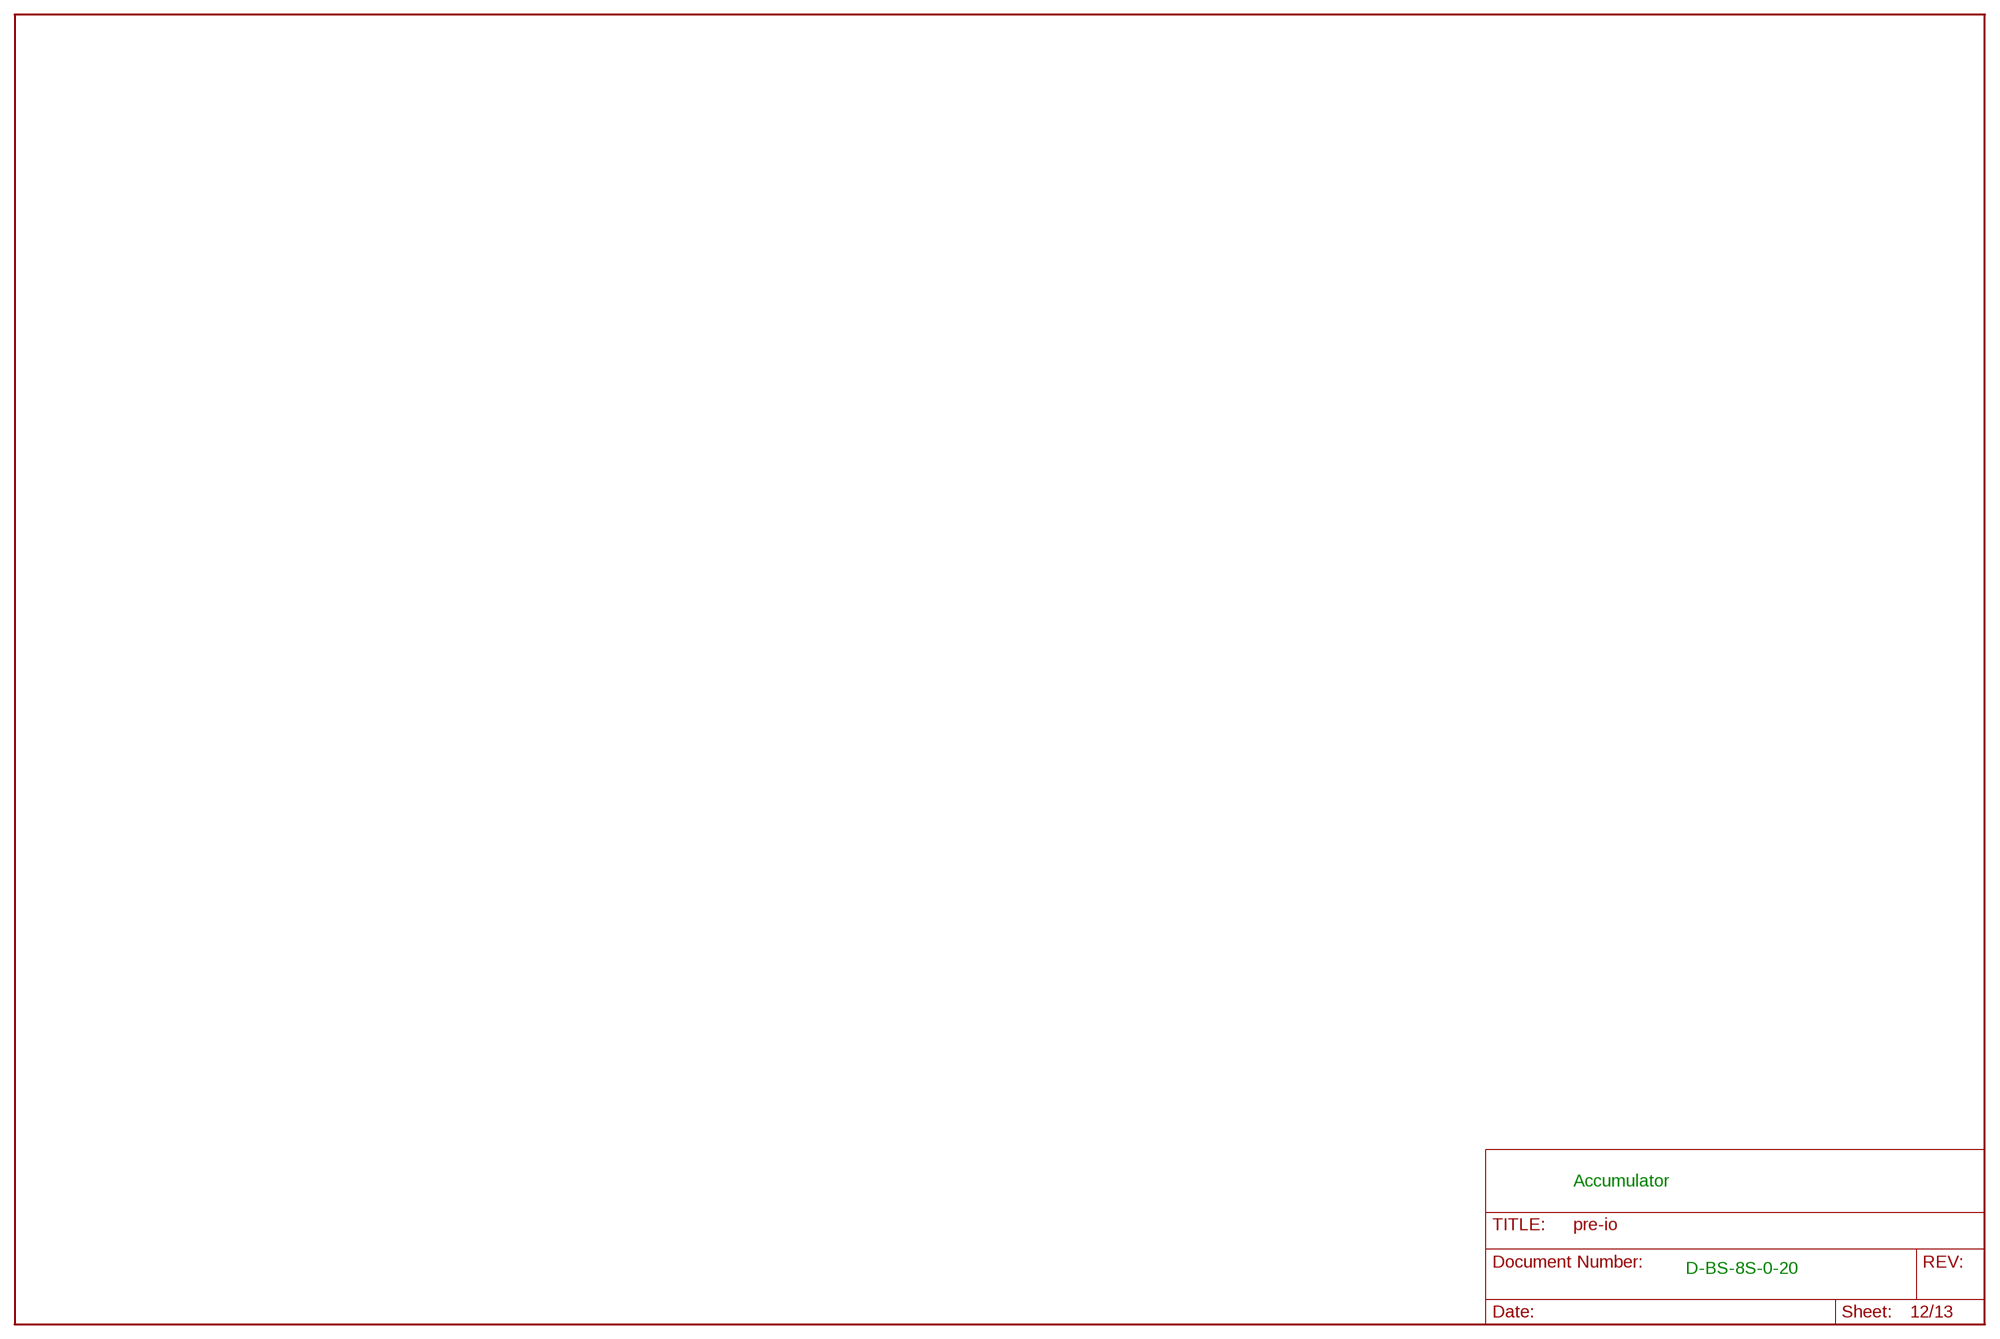
[diagram p11: schematic, sheet 12]
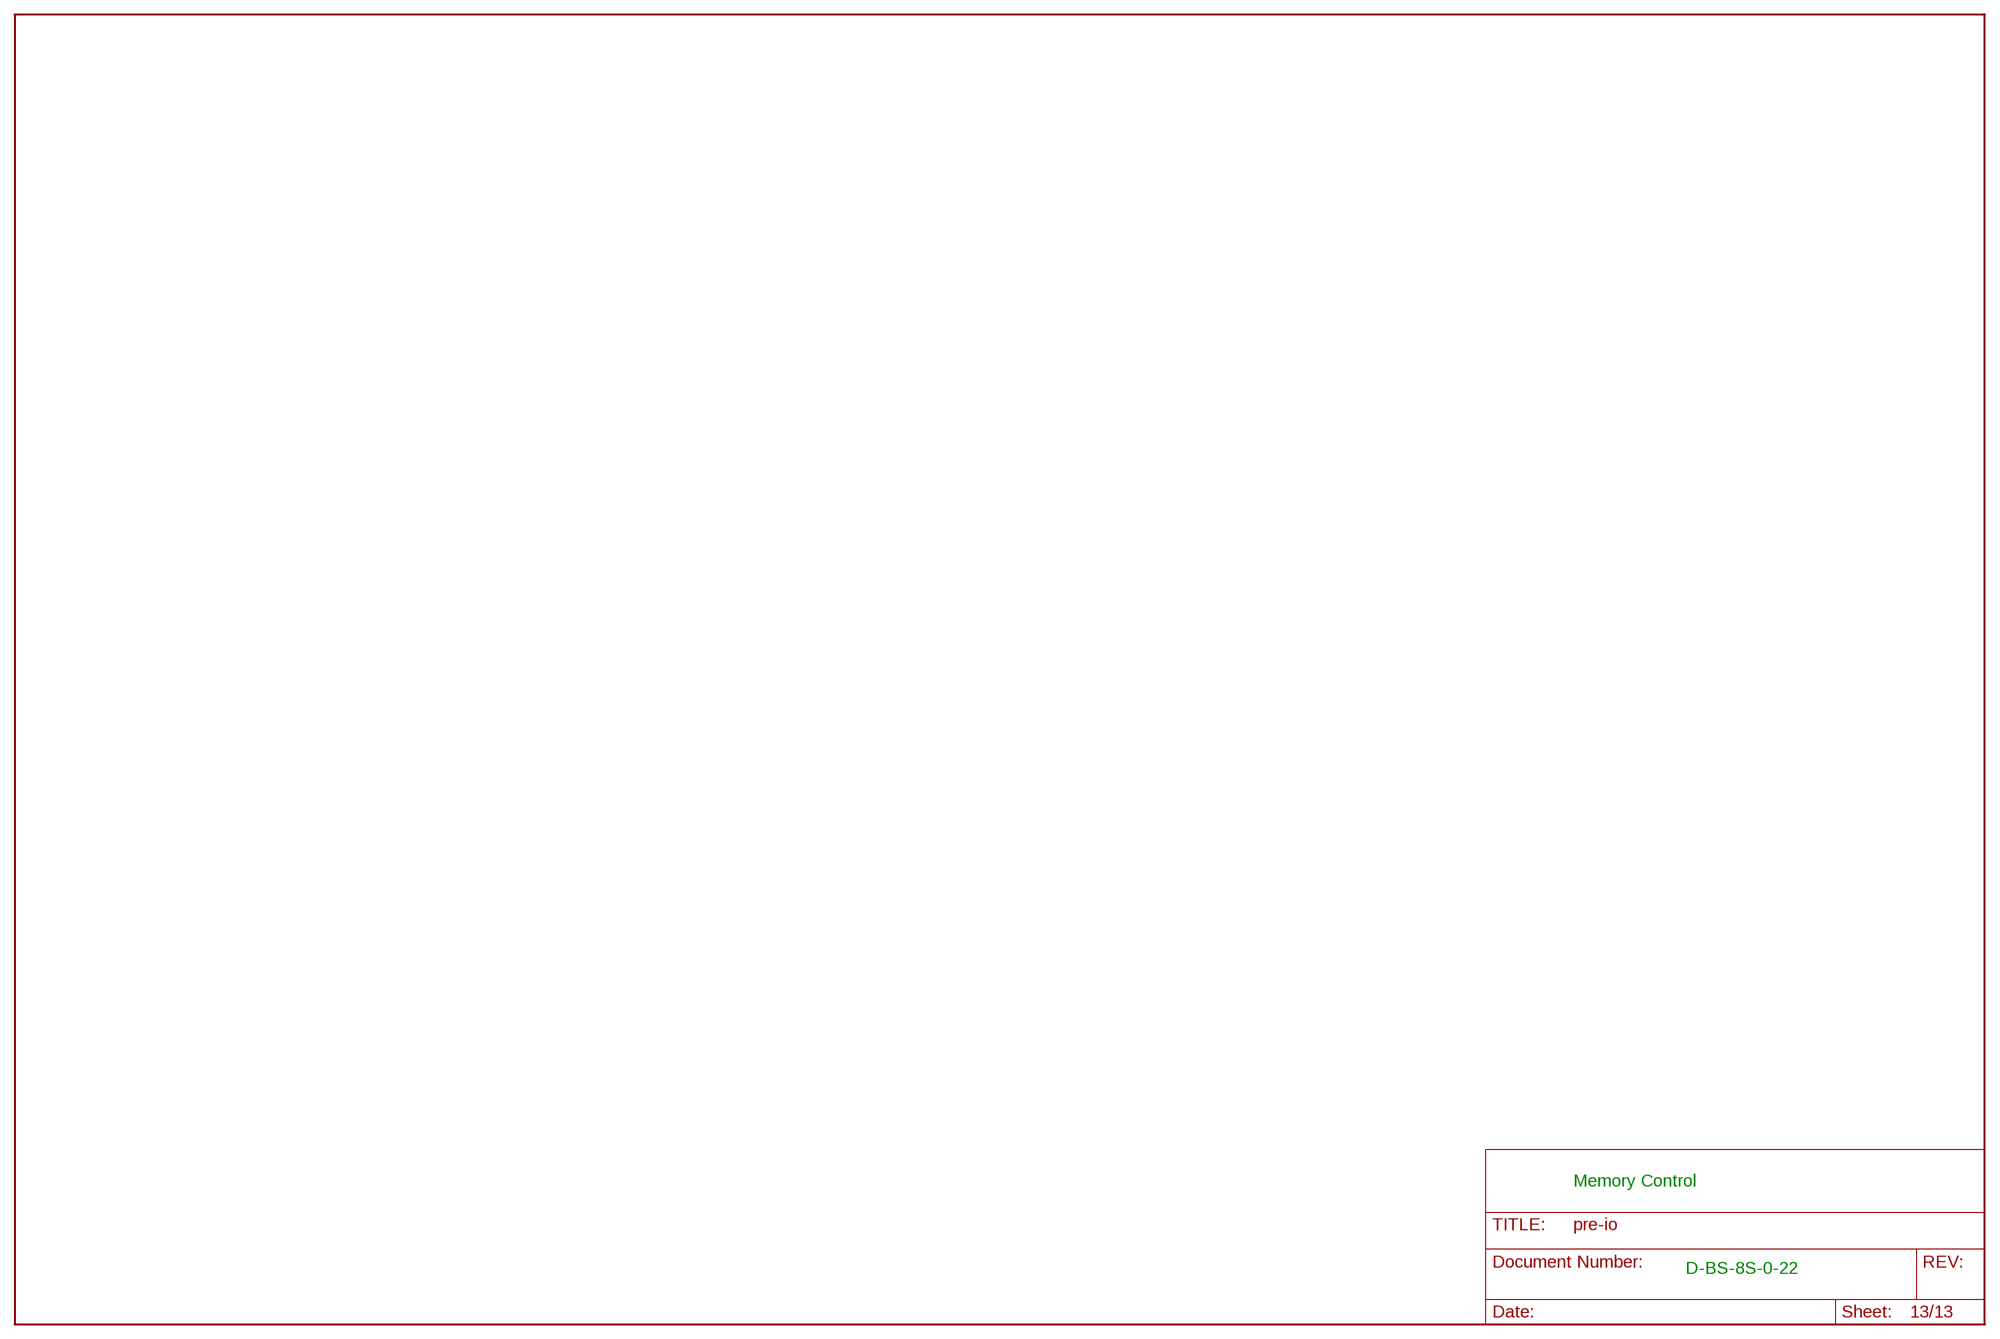
[diagram p12: schematic, sheet 13]

(export (version "E")
  (design (tool "Eeschema 10.0.6"))
  (components
    (comp (ref "D06A")
      (value "R113S")
      (footprint "eagle-import:H807S")
      (libsource (lib "eagle-import") (part "R113S"))
    )
    (comp (ref "F22A")
      (value "W005S")
      (footprint "eagle-import:H807S")
      (libsource (lib "eagle-import") (part "W005S"))
    )
    (comp (ref "A18")
      (value "R107S")
      (footprint "eagle-import:H807S")
      (libsource (lib "eagle-import") (part "R107S"))
    )
    (comp (ref "B02")
      (value "W023S")
      (footprint "eagle-import:H807S")
      (libsource (lib "eagle-import") (part "W023S"))
    )
    (comp (ref "B05")
      (value "W005S")
      (footprint "eagle-import:H807S")
      (libsource (lib "eagle-import") (part "W005S"))
    )
    (comp (ref "B06")
      (value "W050S")
      (footprint "eagle-import:H807S")
      (libsource (lib "eagle-import") (part "W050S"))
    )
    (comp (ref "B07")
      (value "W050S")
      (footprint "eagle-import:H807S")
      (libsource (lib "eagle-import") (part "W050S"))
    )
    (comp (ref "C02")
      (value "W023S")
      (footprint "eagle-import:H807S")
      (libsource (lib "eagle-import") (part "W023S"))
    )
    (comp (ref "C03")
      (value "W050S")
      (footprint "eagle-import:H807S")
      (libsource (lib "eagle-import") (part "W050S"))
    )
    (comp (ref "C06")
      (value "W050S")
      (footprint "eagle-import:H807S")
      (libsource (lib "eagle-import") (part "W050S"))
    )
    (comp (ref "D02")
      (value "W023S")
      (footprint "eagle-import:H807S")
      (libsource (lib "eagle-import") (part "W023S"))
    )
    (comp (ref "D09")
      (value "R603S")
      (footprint "eagle-import:H807S")
      (libsource (lib "eagle-import") (part "R603S"))
    )
    (comp (ref "E02")
      (value "W023S")
      (footprint "eagle-import:H807S")
      (libsource (lib "eagle-import") (part "W023S"))
    )
    (comp (ref "E12")
      (value "R202S")
      (footprint "eagle-import:H807S")
      (libsource (lib "eagle-import") (part "R202S"))
    )
    (comp (ref "E13")
      (value "R113S")
      (footprint "eagle-import:H807S")
      (libsource (lib "eagle-import") (part "R113S"))
    )
    (comp (ref "E14")
      (value "R113S")
      (footprint "eagle-import:H807S")
      (libsource (lib "eagle-import") (part "R113S"))
    )
    (comp (ref "E15")
      (value "R202S")
      (footprint "eagle-import:H807S")
      (libsource (lib "eagle-import") (part "R202S"))
    )
    (comp (ref "E16")
      (value "R202S")
      (footprint "eagle-import:H807S")
      (libsource (lib "eagle-import") (part "R202S"))
    )
    (comp (ref "E17")
      (value "R202S")
      (footprint "eagle-import:H807S")
      (libsource (lib "eagle-import") (part "R202S"))
    )
    (comp (ref "E18")
      (value "R202S")
      (footprint "eagle-import:H807S")
      (libsource (lib "eagle-import") (part "R202S"))
    )
    (comp (ref "E19")
      (value "R202S")
      (footprint "eagle-import:H807S")
      (libsource (lib "eagle-import") (part "R202S"))
    )
    (comp (ref "E20")
      (value "R202S")
      (footprint "eagle-import:H807S")
      (libsource (lib "eagle-import") (part "R202S"))
    )
    (comp (ref "F10")
      (value "R107S")
      (footprint "eagle-import:H807S")
      (libsource (lib "eagle-import") (part "R107S"))
    )
    (comp (ref "F13")
      (value "R107S")
      (footprint "eagle-import:H807S")
      (libsource (lib "eagle-import") (part "R107S"))
    )
    (comp (ref "F15")
      (value "R111S")
      (footprint "eagle-import:H807S")
      (libsource (lib "eagle-import") (part "R111S"))
    )
    (comp (ref "A20")
      (value "R603S")
      (footprint "eagle-import:H807S")
      (libsource (lib "eagle-import") (part "R603S"))
    )
    (comp (ref "A21")
      (value "R111S")
      (footprint "eagle-import:H807S")
      (libsource (lib "eagle-import") (part "R111S"))
    )
    (comp (ref "A22")
      (value "R001S")
      (footprint "eagle-import:H807S")
      (libsource (lib "eagle-import") (part "R001S"))
    )
    (comp (ref "A28")
      (value "R602S")
      (footprint "eagle-import:H807S")
      (libsource (lib "eagle-import") (part "R602S"))
    )
    (comp (ref "B23")
      (value "R111S")
      (footprint "eagle-import:H807S")
      (libsource (lib "eagle-import") (part "R111S"))
    )
    (comp (ref "B26")
      (value "R002S")
      (footprint "eagle-import:H807S")
      (libsource (lib "eagle-import") (part "R002S"))
    )
    (comp (ref "B27")
      (value "R602S")
      (footprint "eagle-import:H807S")
      (libsource (lib "eagle-import") (part "R602S"))
    )
    (comp (ref "B30")
      (value "R603S")
      (footprint "eagle-import:H807S")
      (libsource (lib "eagle-import") (part "R603S"))
    )
    (comp (ref "C07")
      (value "R111S")
      (footprint "eagle-import:H807S")
      (libsource (lib "eagle-import") (part "R111S"))
    )
    (comp (ref "C08")
      (value "R002S")
      (footprint "eagle-import:H807S")
      (libsource (lib "eagle-import") (part "R002S"))
    )
    (comp (ref "E10")
      (value "R113S")
      (footprint "eagle-import:H807S")
      (libsource (lib "eagle-import") (part "R113S"))
    )
    (comp (ref "F03")
      (value "R202S")
      (footprint "eagle-import:H807S")
      (libsource (lib "eagle-import") (part "R202S"))
    )
    (comp (ref "F06")
      (value "R001S")
      (footprint "eagle-import:H807S")
      (libsource (lib "eagle-import") (part "R001S"))
    )
    (comp (ref "F07")
      (value "R111S")
      (footprint "eagle-import:H807S")
      (libsource (lib "eagle-import") (part "R111S"))
    )
    (comp (ref "F08")
      (value "R111S")
      (footprint "eagle-import:H807S")
      (libsource (lib "eagle-import") (part "R111S"))
    )
    (comp (ref "F09")
      (value "R111S")
      (footprint "eagle-import:H807S")
      (libsource (lib "eagle-import") (part "R111S"))
    )
    (comp (ref "F18")
      (value "R107S")
      (footprint "eagle-import:H807S")
      (libsource (lib "eagle-import") (part "R107S"))
    )
    (comp (ref "A02")
      (value "W023S")
      (footprint "eagle-import:H807S")
      (libsource (lib "eagle-import") (part "W023S"))
    )
    (comp (ref "A06")
      (value "W050S")
      (footprint "eagle-import:H807S")
      (libsource (lib "eagle-import") (part "W050S"))
    )
    (comp (ref "A07")
      (value "W050S")
      (footprint "eagle-import:H807S")
      (libsource (lib "eagle-import") (part "W050S"))
    )
    (comp (ref "B13")
      (value "R111S")
      (footprint "eagle-import:H807S")
      (libsource (lib "eagle-import") (part "R111S"))
    )
    (comp (ref "B20")
      (value "R111S")
      (footprint "eagle-import:H807S")
      (libsource (lib "eagle-import") (part "R111S"))
    )
    (comp (ref "B21")
      (value "R002S")
      (footprint "eagle-import:H807S")
      (libsource (lib "eagle-import") (part "R002S"))
    )
    (comp (ref "B22")
      (value "R603S")
      (footprint "eagle-import:H807S")
      (libsource (lib "eagle-import") (part "R603S"))
    )
    (comp (ref "C11")
      (value "R001S")
      (footprint "eagle-import:H807S")
      (libsource (lib "eagle-import") (part "R001S"))
    )
    (comp (ref "C37")
      (value "R603S")
      (footprint "eagle-import:H807S")
      (libsource (lib "eagle-import") (part "R603S"))
    )
    (comp (ref "D17")
      (value "R151S")
      (footprint "eagle-import:H807S")
      (libsource (lib "eagle-import") (part "R151S"))
    )
    (comp (ref "D19")
      (value "R202S")
      (footprint "eagle-import:H807S")
      (libsource (lib "eagle-import") (part "R202S"))
    )
    (comp (ref "D20")
      (value "R202S")
      (footprint "eagle-import:H807S")
      (libsource (lib "eagle-import") (part "R202S"))
    )
    (comp (ref "E09")
      (value "R113S")
      (footprint "eagle-import:H807S")
      (libsource (lib "eagle-import") (part "R113S"))
    )
    (comp (ref "E11")
      (value "R113S")
      (footprint "eagle-import:H807S")
      (libsource (lib "eagle-import") (part "R113S"))
    )
    (comp (ref "F14")
      (value "R113S")
      (footprint "eagle-import:H807S")
      (libsource (lib "eagle-import") (part "R113S"))
    )
    (comp (ref "F16")
      (value "R001S")
      (footprint "eagle-import:H807S")
      (libsource (lib "eagle-import") (part "R001S"))
    )
    (comp (ref "F17")
      (value "R111S")
      (footprint "eagle-import:H807S")
      (libsource (lib "eagle-import") (part "R111S"))
    )
    (comp (ref "F19")
      (value "R107S")
      (footprint "eagle-import:H807S")
      (libsource (lib "eagle-import") (part "R107S"))
    )
    (comp (ref "F20")
      (value "R107S")
      (footprint "eagle-import:H807S")
      (libsource (lib "eagle-import") (part "R107S"))
    )
    (comp (ref "A24")
      (value "R107S")
      (footprint "eagle-import:H807S")
      (libsource (lib "eagle-import") (part "R107S"))
    )
    (comp (ref "A26")
      (value "R113S")
      (footprint "eagle-import:H807S")
      (libsource (lib "eagle-import") (part "R113S"))
    )
    (comp (ref "A27")
      (value "R113S")
      (footprint "eagle-import:H807S")
      (libsource (lib "eagle-import") (part "R113S"))
    )
    (comp (ref "A29")
      (value "R202S")
      (footprint "eagle-import:H807S")
      (libsource (lib "eagle-import") (part "R202S"))
    )
    (comp (ref "A30")
      (value "R202S")
      (footprint "eagle-import:H807S")
      (libsource (lib "eagle-import") (part "R202S"))
    )
    (comp (ref "A31")
      (value "R202S")
      (footprint "eagle-import:H807S")
      (libsource (lib "eagle-import") (part "R202S"))
    )
    (comp (ref "A32")
      (value "R202S")
      (footprint "eagle-import:H807S")
      (libsource (lib "eagle-import") (part "R202S"))
    )
    (comp (ref "A33")
      (value "R001S")
      (footprint "eagle-import:H807S")
      (libsource (lib "eagle-import") (part "R001S"))
    )
    (comp (ref "B29")
      (value "R603S")
      (footprint "eagle-import:H807S")
      (libsource (lib "eagle-import") (part "R603S"))
    )
    (comp (ref "B31")
      (value "R603S")
      (footprint "eagle-import:H807S")
      (libsource (lib "eagle-import") (part "R603S"))
    )
    (comp (ref "B32")
      (value "R401S")
      (footprint "eagle-import:H807S")
      (libsource (lib "eagle-import") (part "R401S"))
    )
    (comp (ref "C09")
      (value "R107S")
      (footprint "eagle-import:H807S")
      (libsource (lib "eagle-import") (part "R107S"))
    )
    (comp (ref "C14")
      (value "R113S")
      (footprint "eagle-import:H807S")
      (libsource (lib "eagle-import") (part "R113S"))
    )
    (comp (ref "C21")
      (value "R107S")
      (footprint "eagle-import:H807S")
      (libsource (lib "eagle-import") (part "R107S"))
    )
    (comp (ref "C22")
      (value "M517S")
      (footprint "eagle-import:H807S")
      (libsource (lib "eagle-import") (part "M517S"))
    )
    (comp (ref "C23")
      (value "W512S")
      (footprint "eagle-import:H807S")
      (libsource (lib "eagle-import") (part "W512S"))
    )
    (comp (ref "C24")
      (value "R107S")
      (footprint "eagle-import:H807S")
      (libsource (lib "eagle-import") (part "R107S"))
    )
    (comp (ref "C25")
      (value "M517S")
      (footprint "eagle-import:H807S")
      (libsource (lib "eagle-import") (part "M517S"))
    )
    (comp (ref "C26")
      (value "W512S")
      (footprint "eagle-import:H807S")
      (libsource (lib "eagle-import") (part "W512S"))
    )
    (comp (ref "C27")
      (value "M517S")
      (footprint "eagle-import:H807S")
      (libsource (lib "eagle-import") (part "M517S"))
    )
    (comp (ref "C28")
      (value "W023S")
      (footprint "eagle-import:H807S")
      (libsource (lib "eagle-import") (part "W023S"))
    )
    (comp (ref "C33")
      (value "EMPTYS")
      (footprint "eagle-import:H807S")
      (libsource (lib "eagle-import") (part "EMPTYS"))
    )
    (comp (ref "C34")
      (value "EMPTYS")
      (footprint "eagle-import:H807S")
      (libsource (lib "eagle-import") (part "EMPTYS"))
    )
    (comp (ref "C35")
      (value "EMPTYS")
      (footprint "eagle-import:H807S")
      (libsource (lib "eagle-import") (part "EMPTYS"))
    )
    (comp (ref "D21")
      (value "M507S")
      (footprint "eagle-import:H807S")
      (libsource (lib "eagle-import") (part "M507S"))
    )
    (comp (ref "D22")
      (value "M507S")
      (footprint "eagle-import:H807S")
      (libsource (lib "eagle-import") (part "M507S"))
    )
    (comp (ref "D23")
      (value "EMPTYS")
      (footprint "eagle-import:H807S")
      (libsource (lib "eagle-import") (part "EMPTYS"))
    )
    (comp (ref "D24")
      (value "EMPTYS")
      (footprint "eagle-import:H807S")
      (libsource (lib "eagle-import") (part "EMPTYS"))
    )
    (comp (ref "D25")
      (value "EMPTYS")
      (footprint "eagle-import:H807S")
      (libsource (lib "eagle-import") (part "EMPTYS"))
    )
    (comp (ref "D26")
      (value "EMPTYS")
      (footprint "eagle-import:H807S")
      (libsource (lib "eagle-import") (part "EMPTYS"))
    )
    (comp (ref "D27")
      (value "M507S")
      (footprint "eagle-import:H807S")
      (libsource (lib "eagle-import") (part "M507S"))
    )
    (comp (ref "D28")
      (value "W023S")
      (footprint "eagle-import:H807S")
      (libsource (lib "eagle-import") (part "W023S"))
    )
    (comp (ref "D33")
      (value "EMPTYS")
      (footprint "eagle-import:H807S")
      (libsource (lib "eagle-import") (part "EMPTYS"))
    )
    (comp (ref "D34")
      (value "EMPTYS")
      (footprint "eagle-import:H807S")
      (libsource (lib "eagle-import") (part "EMPTYS"))
    )
    (comp (ref "D35")
      (value "EMPTYS")
      (footprint "eagle-import:H807S")
      (libsource (lib "eagle-import") (part "EMPTYS"))
    )
    (comp (ref "E21")
      (value "EMPTYS")
      (footprint "eagle-import:H807S")
      (libsource (lib "eagle-import") (part "EMPTYS"))
    )
    (comp (ref "E22")
      (value "EMPTYS")
      (footprint "eagle-import:H807S")
      (libsource (lib "eagle-import") (part "EMPTYS"))
    )
    (comp (ref "E23")
      (value "EMPTYS")
      (footprint "eagle-import:H807S")
      (libsource (lib "eagle-import") (part "EMPTYS"))
    )
    (comp (ref "E24")
      (value "EMPTYS")
      (footprint "eagle-import:H807S")
      (libsource (lib "eagle-import") (part "EMPTYS"))
    )
    (comp (ref "E25")
      (value "EMPTYS")
      (footprint "eagle-import:H807S")
      (libsource (lib "eagle-import") (part "EMPTYS"))
    )
    (comp (ref "E26")
      (value "EMPTYS")
      (footprint "eagle-import:H807S")
      (libsource (lib "eagle-import") (part "EMPTYS"))
    )
    (comp (ref "E27")
      (value "EMPTYS")
      (footprint "eagle-import:H807S")
      (libsource (lib "eagle-import") (part "EMPTYS"))
    )
    (comp (ref "E28")
      (value "EMPTYS")
      (footprint "eagle-import:H807S")
      (libsource (lib "eagle-import") (part "EMPTYS"))
    )
    (comp (ref "E33")
      (value "EMPTYS")
      (footprint "eagle-import:H807S")
      (libsource (lib "eagle-import") (part "EMPTYS"))
    )
    (comp (ref "E34")
      (value "EMPTYS")
      (footprint "eagle-import:H807S")
      (libsource (lib "eagle-import") (part "EMPTYS"))
    )
    (comp (ref "E35")
      (value "EMPTYS")
      (footprint "eagle-import:H807S")
      (libsource (lib "eagle-import") (part "EMPTYS"))
    )
    (comp (ref "F21")
      (value "EMPTYS")
      (footprint "eagle-import:H807S")
      (libsource (lib "eagle-import") (part "EMPTYS"))
    )
    (comp (ref "F22")
      (value "EMPTYS")
      (footprint "eagle-import:H807S")
      (libsource (lib "eagle-import") (part "EMPTYS"))
    )
    (comp (ref "F23")
      (value "EMPTYS")
      (footprint "eagle-import:H807S")
      (libsource (lib "eagle-import") (part "EMPTYS"))
    )
    (comp (ref "F24")
      (value "EMPTYS")
      (footprint "eagle-import:H807S")
      (libsource (lib "eagle-import") (part "EMPTYS"))
    )
    (comp (ref "F25")
      (value "EMPTYS")
      (footprint "eagle-import:H807S")
      (libsource (lib "eagle-import") (part "EMPTYS"))
    )
    (comp (ref "F26")
      (value "EMPTYS")
      (footprint "eagle-import:H807S")
      (libsource (lib "eagle-import") (part "EMPTYS"))
    )
    (comp (ref "F27")
      (value "EMPTYS")
      (footprint "eagle-import:H807S")
      (libsource (lib "eagle-import") (part "EMPTYS"))
    )
    (comp (ref "F28")
      (value "EMPTYS")
      (footprint "eagle-import:H807S")
      (libsource (lib "eagle-import") (part "EMPTYS"))
    )
    (comp (ref "F33")
      (value "EMPTYS")
      (footprint "eagle-import:H807S")
      (libsource (lib "eagle-import") (part "EMPTYS"))
    )
    (comp (ref "F34")
      (value "EMPTYS")
      (footprint "eagle-import:H807S")
      (libsource (lib "eagle-import") (part "EMPTYS"))
    )
    (comp (ref "F35")
      (value "EMPTYS")
      (footprint "eagle-import:H807S")
      (libsource (lib "eagle-import") (part "EMPTYS"))
    )
    (comp (ref "A05")
      (value "W050S")
      (footprint "eagle-import:H807S")
      (libsource (lib "eagle-import") (part "W050S"))
    )
    (comp (ref "A08")
      (value "R113S")
      (footprint "eagle-import:H807S")
      (libsource (lib "eagle-import") (part "R113S"))
    )
    (comp (ref "A09")
      (value "R107S")
      (footprint "eagle-import:H807S")
      (libsource (lib "eagle-import") (part "R107S"))
    )
    (comp (ref "A10")
      (value "R113S")
      (footprint "eagle-import:H807S")
      (libsource (lib "eagle-import") (part "R113S"))
    )
    (comp (ref "A12")
      (value "R002S")
      (footprint "eagle-import:H807S")
      (libsource (lib "eagle-import") (part "R002S"))
    )
    (comp (ref "A13")
      (value "R002S")
      (footprint "eagle-import:H807S")
      (libsource (lib "eagle-import") (part "R002S"))
    )
    (comp (ref "A14")
      (value "R111S")
      (footprint "eagle-import:H807S")
      (libsource (lib "eagle-import") (part "R111S"))
    )
    (comp (ref "A15")
      (value "R113S")
      (footprint "eagle-import:H807S")
      (libsource (lib "eagle-import") (part "R113S"))
    )
    (comp (ref "A35")
      (value "R001S")
      (footprint "eagle-import:H807S")
      (libsource (lib "eagle-import") (part "R001S"))
    )
    (comp (ref "A38")
      (value "R111S")
      (footprint "eagle-import:H807S")
      (libsource (lib "eagle-import") (part "R111S"))
    )
    (comp (ref "A39")
      (value "R002S")
      (footprint "eagle-import:H807S")
      (libsource (lib "eagle-import") (part "R002S"))
    )
    (comp (ref "B08")
      (value "R107S")
      (footprint "eagle-import:H807S")
      (libsource (lib "eagle-import") (part "R107S"))
    )
    (comp (ref "B09")
      (value "R202S")
      (footprint "eagle-import:H807S")
      (libsource (lib "eagle-import") (part "R202S"))
    )
    (comp (ref "B10")
      (value "R202S")
      (footprint "eagle-import:H807S")
      (libsource (lib "eagle-import") (part "R202S"))
    )
    (comp (ref "B11")
      (value "R202S")
      (footprint "eagle-import:H807S")
      (libsource (lib "eagle-import") (part "R202S"))
    )
    (comp (ref "B12")
      (value "R202S")
      (footprint "eagle-import:H807S")
      (libsource (lib "eagle-import") (part "R202S"))
    )
    (comp (ref "B14")
      (value "R002S")
      (footprint "eagle-import:H807S")
      (libsource (lib "eagle-import") (part "R002S"))
    )
    (comp (ref "B15")
      (value "R113S")
      (footprint "eagle-import:H807S")
      (libsource (lib "eagle-import") (part "R113S"))
    )
    (comp (ref "B17")
      (value "R113S")
      (footprint "eagle-import:H807S")
      (libsource (lib "eagle-import") (part "R113S"))
    )
    (comp (ref "C10")
      (value "R111S")
      (footprint "eagle-import:H807S")
      (libsource (lib "eagle-import") (part "R111S"))
    )
    (comp (ref "C12")
      (value "R111S")
      (footprint "eagle-import:H807S")
      (libsource (lib "eagle-import") (part "R111S"))
    )
    (comp (ref "C13")
      (value "R107S")
      (footprint "eagle-import:H807S")
      (libsource (lib "eagle-import") (part "R107S"))
    )
    (comp (ref "F37")
      (value "R602S")
      (footprint "eagle-import:H807S")
      (libsource (lib "eagle-import") (part "R602S"))
    )
    (comp (ref "F38")
      (value "R602S")
      (footprint "eagle-import:H807S")
      (libsource (lib "eagle-import") (part "R602S"))
    )
    (comp (ref "F39")
      (value "R602S")
      (footprint "eagle-import:H807S")
      (libsource (lib "eagle-import") (part "R602S"))
    )
    (comp (ref "A01")
      (value "W023S")
      (footprint "eagle-import:H807S")
      (libsource (lib "eagle-import") (part "W023S"))
    )
    (comp (ref "A34")
      (value "R111S")
      (footprint "eagle-import:H807S")
      (libsource (lib "eagle-import") (part "R111S"))
    )
    (comp (ref "A36")
      (value "R302S")
      (footprint "eagle-import:H807S")
      (libsource (lib "eagle-import") (part "R302S"))
    )
    (comp (ref "A40")
      (value "R107S")
      (footprint "eagle-import:H807S")
      (libsource (lib "eagle-import") (part "R107S"))
    )
    (comp (ref "B01")
      (value "W023S")
      (footprint "eagle-import:H807S")
      (libsource (lib "eagle-import") (part "W023S"))
    )
    (comp (ref "B03")
      (value "R603S")
      (footprint "eagle-import:H807S")
      (libsource (lib "eagle-import") (part "R603S"))
    )
    (comp (ref "B18")
      (value "R603S")
      (footprint "eagle-import:H807S")
      (libsource (lib "eagle-import") (part "R603S"))
    )
    (comp (ref "B19")
      (value "R603S")
      (footprint "eagle-import:H807S")
      (libsource (lib "eagle-import") (part "R603S"))
    )
    (comp (ref "B24")
      (value "R113S")
      (footprint "eagle-import:H807S")
      (libsource (lib "eagle-import") (part "R113S"))
    )
    (comp (ref "B33")
      (value "R107S")
      (footprint "eagle-import:H807S")
      (libsource (lib "eagle-import") (part "R107S"))
    )
    (comp (ref "B34")
      (value "R202S")
      (footprint "eagle-import:H807S")
      (libsource (lib "eagle-import") (part "R202S"))
    )
    (comp (ref "B35")
      (value "R202S")
      (footprint "eagle-import:H807S")
      (libsource (lib "eagle-import") (part "R202S"))
    )
    (comp (ref "B36")
      (value "R113S")
      (footprint "eagle-import:H807S")
      (libsource (lib "eagle-import") (part "R113S"))
    )
    (comp (ref "C01")
      (value "W023S")
      (footprint "eagle-import:H807S")
      (libsource (lib "eagle-import") (part "W023S"))
    )
    (comp (ref "C04")
      (value "R602S")
      (footprint "eagle-import:H807S")
      (libsource (lib "eagle-import") (part "R602S"))
    )
    (comp (ref "C38")
      (value "R602S")
      (footprint "eagle-import:H807S")
      (libsource (lib "eagle-import") (part "R602S"))
    )
    (comp (ref "C39")
      (value "W501S")
      (footprint "eagle-import:H807S")
      (libsource (lib "eagle-import") (part "W501S"))
    )
    (comp (ref "D01")
      (value "W023S")
      (footprint "eagle-import:H807S")
      (libsource (lib "eagle-import") (part "W023S"))
    )
    (comp (ref "D10")
      (value "R603S")
      (footprint "eagle-import:H807S")
      (libsource (lib "eagle-import") (part "R603S"))
    )
    (comp (ref "E01")
      (value "W023S")
      (footprint "eagle-import:H807S")
      (libsource (lib "eagle-import") (part "W023S"))
    )
    (comp (ref "E05")
      (value "W501S")
      (footprint "eagle-import:H807S")
      (libsource (lib "eagle-import") (part "W501S"))
    )
    (comp (ref "F01")
      (value "W023S")
      (footprint "eagle-import:H807S")
      (libsource (lib "eagle-import") (part "W023S"))
    )
    (comp (ref "A16")
      (value "R602S")
      (footprint "eagle-import:H807S")
      (libsource (lib "eagle-import") (part "R602S"))
    )
    (comp (ref "A17")
      (value "R107S")
      (footprint "eagle-import:H807S")
      (libsource (lib "eagle-import") (part "R107S"))
    )
    (comp (ref "A23")
      (value "R111S")
      (footprint "eagle-import:H807S")
      (libsource (lib "eagle-import") (part "R111S"))
    )
    (comp (ref "A25")
      (value "R111S")
      (footprint "eagle-import:H807S")
      (libsource (lib "eagle-import") (part "R111S"))
    )
    (comp (ref "B25")
      (value "R113S")
      (footprint "eagle-import:H807S")
      (libsource (lib "eagle-import") (part "R113S"))
    )
    (comp (ref "B28")
      (value "R202S")
      (footprint "eagle-import:H807S")
      (libsource (lib "eagle-import") (part "R202S"))
    )
    (comp (ref "B40")
      (value "W005S")
      (footprint "eagle-import:H807S")
      (libsource (lib "eagle-import") (part "W005S"))
    )
    (comp (ref "B16")
      (value "R107S")
      (footprint "eagle-import:H807S")
      (libsource (lib "eagle-import") (part "R107S"))
    )
    (comp (ref "B37")
      (value "R107S")
      (footprint "eagle-import:H807S")
      (libsource (lib "eagle-import") (part "R107S"))
    )
    (comp (ref "C05")
      (value "R107S")
      (footprint "eagle-import:H807S")
      (libsource (lib "eagle-import") (part "R107S"))
    )
    (comp (ref "C30")
      (value "W005S")
      (footprint "eagle-import:H807S")
      (libsource (lib "eagle-import") (part "W005S"))
    )
    (comp (ref "C36")
      (value "R107S")
      (footprint "eagle-import:H807S")
      (libsource (lib "eagle-import") (part "R107S"))
    )
    (comp (ref "D06")
      (value "R113S")
      (footprint "eagle-import:H807S")
      (libsource (lib "eagle-import") (part "R113S"))
    )
    (comp (ref "D07")
      (value "R113S")
      (footprint "eagle-import:H807S")
      (libsource (lib "eagle-import") (part "R113S"))
    )
    (comp (ref "D08")
      (value "R113S")
      (footprint "eagle-import:H807S")
      (libsource (lib "eagle-import") (part "R113S"))
    )
    (comp (ref "D11")
      (value "R202S")
      (footprint "eagle-import:H807S")
      (libsource (lib "eagle-import") (part "R202S"))
    )
    (comp (ref "D12")
      (value "R202S")
      (footprint "eagle-import:H807S")
      (libsource (lib "eagle-import") (part "R202S"))
    )
    (comp (ref "D13")
      (value "R202S")
      (footprint "eagle-import:H807S")
      (libsource (lib "eagle-import") (part "R202S"))
    )
    (comp (ref "D14")
      (value "R202S")
      (footprint "eagle-import:H807S")
      (libsource (lib "eagle-import") (part "R202S"))
    )
    (comp (ref "D15")
      (value "R202S")
      (footprint "eagle-import:H807S")
      (libsource (lib "eagle-import") (part "R202S"))
    )
    (comp (ref "D16")
      (value "R202S")
      (footprint "eagle-import:H807S")
      (libsource (lib "eagle-import") (part "R202S"))
    )
    (comp (ref "D18")
      (value "R107S")
      (footprint "eagle-import:H807S")
      (libsource (lib "eagle-import") (part "R107S"))
    )
    (comp (ref "E03")
      (value "R001S")
      (footprint "eagle-import:H807S")
      (libsource (lib "eagle-import") (part "R001S"))
    )
    (comp (ref "E06")
      (value "R202S")
      (footprint "eagle-import:H807S")
      (libsource (lib "eagle-import") (part "R202S"))
    )
    (comp (ref "E07")
      (value "W050S")
      (footprint "eagle-import:H807S")
      (libsource (lib "eagle-import") (part "W050S"))
    )
    (comp (ref "F02")
      (value "W023S")
      (footprint "eagle-import:H807S")
      (libsource (lib "eagle-import") (part "W023S"))
    )
    (comp (ref "F05")
      (value "R202S")
      (footprint "eagle-import:H807S")
      (libsource (lib "eagle-import") (part "R202S"))
    )
    (comp (ref "F11")
      (value "R107S")
      (footprint "eagle-import:H807S")
      (libsource (lib "eagle-import") (part "R107S"))
    )
    (comp (ref "F12")
      (value "R107S")
      (footprint "eagle-import:H807S")
      (libsource (lib "eagle-import") (part "R107S"))
    )
    (comp (ref "F36")
      (value "R113S")
      (footprint "eagle-import:H807S")
      (libsource (lib "eagle-import") (part "R113S"))
    )
  )
  (nets
    (net (code "1") (name "(ISZ*Z1)+JMS+(OP+IOT)*SKP") (class "Default")
      (node (ref "F15") (pin "N2") (pinfunction "O$1_N2") (pintype "open_collector"))
      (node (ref "F15") (pin "P2") (pinfunction "P$1_P2") (pintype "passive"))
      (node (ref "F19") (pin "M2") (pinfunction "I$1_M2") (pintype "input"))
    )
    (net (code "2") (name "(ISZ*ZI)+JMS+(OP+IOT)*SKP") (class "Default")
      (node (ref "A15") (pin "P2") (pinfunction "I$1_P2") (pintype "input"))
    )
    (net (code "3") (name "(LAS+DEPS+EXS)") (class "Default")
      (node (ref "B20") (pin "H2") (pinfunction "O$1_H2") (pintype "open_collector"))
      (node (ref "B20") (pin "J2") (pinfunction "P$1_J2") (pintype "passive"))
      (node (ref "B36") (pin "R2") (pinfunction "I$2_R2") (pintype "input"))
    )
    (net (code "4") (name "-(DP+EP)") (class "Default")
      (node (ref "A13") (pin "U2") (pinfunction "E_U2") (pintype "input"))
      (node (ref "A28") (pin "P2") (pinfunction "E_P2") (pintype "input"))
      (node (ref "A36") (pin "N2") (pinfunction "E_N2") (pintype "input"))
      (node (ref "B14") (pin "U2") (pinfunction "E_U2") (pintype "input"))
      (node (ref "B18") (pin "T2") (pinfunction "O_T2") (pintype "open_collector"))
    )
    (net (code "5") (name "-(EX+DC)") (class "Default")
      (node (ref "A13") (pin "D2") (pinfunction "D_D2") (pintype "input"))
      (node (ref "B14") (pin "D2") (pinfunction "D_D2") (pintype "input"))
      (node (ref "B33") (pin "D2") (pinfunction "O$1_D2") (pintype "open_collector"))
      (node (ref "C08") (pin "E2") (pinfunction "E_E2") (pintype "input"))
      (node (ref "C38") (pin "R2") (pinfunction "F_R2") (pintype "input"))
    )
    (net (code "6") (name "-(IAC+CMA)") (class "Default")
      (node (ref "B21") (pin "H2") (pinfunction "D_H2") (pintype "input"))
      (node (ref "E10") (pin "R2") (pinfunction "I$2_R2") (pintype "input"))
      (node (ref "F19") (pin "T2") (pinfunction "O$1_T2") (pintype "open_collector"))
    )
    (net (code "7") (name "-(ISZ*Z1)") (class "Default")
      (node (ref "E11") (pin "V2") (pinfunction "O$1_V2") (pintype "open_collector"))
      (node (ref "F16") (pin "N2") (pinfunction "D_N2") (pintype "input"))
    )
    (net (code "8") (name "-(OP+IOT)") (class "Default")
      (node (ref "A15") (pin "E2") (pinfunction "I$2_E2") (pintype "input"))
      (node (ref "B17") (pin "R2") (pinfunction "I$2_R2") (pintype "input"))
      (node (ref "D07") (pin "M2") (pinfunction "I$2_M2") (pintype "input"))
      (node (ref "E11") (pin "M2") (pinfunction "I$2_M2") (pintype "input"))
      (node (ref "F13") (pin "R2") (pinfunction "O$1_R2") (pintype "open_collector"))
    )
    (net (code "9") (name "-(SP+PCP)") (class "Default")
      (node (ref "B19") (pin "M2") (pinfunction "O_M2") (pintype "open_collector"))
      (node (ref "B22") (pin "R2") (pinfunction "PU0_R2") (pintype "input"))
      (node (ref "B27") (pin "V2") (pinfunction "L_V2") (pintype "input"))
      (node (ref "B28") (pin "F2") (pinfunction "RESET_F2") (pintype "input"))
      (node (ref "F05") (pin "F2") (pinfunction "RESET_F2") (pintype "input"))
    )
    (net (code "10") (name "-(SP+PCP+LP)") (class "Default")
      (node (ref "B10") (pin "F2") (pinfunction "RESET_F2") (pintype "input"))
      (node (ref "B10") (pin "R2") (pinfunction "RESET_R2") (pintype "input"))
      (node (ref "B11") (pin "F2") (pinfunction "RESET_F2") (pintype "input"))
      (node (ref "B11") (pin "R2") (pinfunction "RESET_R2") (pintype "input"))
      (node (ref "B12") (pin "R2") (pinfunction "RESET_R2") (pintype "input"))
      (node (ref "B22") (pin "T2") (pinfunction "O_T2") (pintype "open_collector"))
      (node (ref "C37") (pin "P2") (pinfunction "I$1_P2") (pintype "passive"))
    )
    (net (code "11") (name "-(WTX*IAC)") (class "Default")
      (node (ref "A13") (pin "L2") (pinfunction "D_L2") (pintype "input"))
      (node (ref "C12") (pin "U2") (pinfunction "O$1_U2") (pintype "open_collector"))
      (node (ref "C12") (pin "V2") (pinfunction "P$1_V2") (pintype "passive"))
    )
    (net (code "12") (name "-(WTX*ISZ)") (class "Default")
      (node (ref "A10") (pin "F2") (pinfunction "O$1_F2") (pintype "open_collector"))
      (node (ref "A13") (pin "J2") (pinfunction "E_J2") (pintype "input"))
      (node (ref "A16") (pin "R2") (pinfunction "F_R2") (pintype "input"))
      (node (ref "B08") (pin "P2") (pinfunction "I$1_P2") (pintype "input"))
      (node (ref "C11") (pin "R2") (pinfunction "D_R2") (pintype "input"))
    )
    (net (code "13") (name "-(WTX*JMS)") (class "Default")
      (node (ref "A09") (pin "E2") (pinfunction "I$1_E2") (pintype "input"))
      (node (ref "A10") (pin "N2") (pinfunction "O$1_N2") (pintype "open_collector"))
      (node (ref "C10") (pin "S2") (pinfunction "I$2_S2") (pintype "input"))
    )
    (net (code "14") (name "-(WTX*OP2)") (class "Default")
      (node (ref "A16") (pin "T2") (pinfunction "J_T2") (pintype "input"))
      (node (ref "D09") (pin "E2") (pinfunction "EN0_E2") (pintype "passive"))
    )
    (net (code "15") (name "-(WTX*ROTR)") (class "Default")
      (node (ref "B27") (pin "F2") (pinfunction "F_F2") (pintype "input"))
    )
    (net (code "16") (name "-(WTX*TAD)") (class "Default")
      (node (ref "A15") (pin "V2") (pinfunction "O$1_V2") (pintype "open_collector"))
      (node (ref "A18") (pin "E2") (pinfunction "I$1_E2") (pintype "input"))
      (node (ref "C10") (pin "E2") (pinfunction "I$2_E2") (pintype "input"))
    )
    (net (code "17") (name "-15V") (class "Default")
      (node (ref "C28") (pin "B2") (pinfunction "P$2_B2") (pintype "bidirectional"))
      (node (ref "D28") (pin "B2") (pinfunction "P$2_B2") (pintype "bidirectional"))
    )
    (net (code "18") (name "-A") (class "Default")
      (node (ref "B29") (pin "D2") (pinfunction "PU0_D2") (pintype "input"))
      (node (ref "B29") (pin "K2") (pinfunction "PU0_K2") (pintype "input"))
      (node (ref "B30") (pin "D2") (pinfunction "PU0_D2") (pintype "input"))
      (node (ref "B30") (pin "R2") (pinfunction "PU0_R2") (pintype "input"))
      (node (ref "B31") (pin "D2") (pinfunction "PU0_D2") (pintype "input"))
    )
    (net (code "19") (name "-A(00-01)") (class "Default")
      (node (ref "B27") (pin "E2") (pinfunction "E_E2") (pintype "input"))
      (node (ref "B29") (pin "F2") (pinfunction "O_F2") (pintype "open_collector"))
    )
    (net (code "20") (name "-A(00-11)") (class "Default")
      (node (ref "A16") (pin "P2") (pinfunction "E_P2") (pintype "input"))
      (node (ref "A16") (pin "S2") (pinfunction "H_S2") (pintype "input"))
      (node (ref "B22") (pin "K2") (pinfunction "PU0_K2") (pintype "input"))
      (node (ref "B29") (pin "R2") (pinfunction "PU0_R2") (pintype "input"))
      (node (ref "B30") (pin "K2") (pinfunction "PU0_K2") (pintype "input"))
      (node (ref "B31") (pin "F2") (pinfunction "O_F2") (pintype "open_collector"))
      (node (ref "D09") (pin "K2") (pinfunction "PU0_K2") (pintype "input"))
      (node (ref "D10") (pin "K2") (pinfunction "PU0_K2") (pintype "input"))
    )
    (net (code "21") (name "-A(00-12)") (class "Default")
      (node (ref "B28") (pin "N2") (pinfunction "PU0_N2") (pintype "input"))
      (node (ref "B28") (pin "U2") (pinfunction "PU1_U2") (pintype "input"))
      (node (ref "B29") (pin "T2") (pinfunction "O_T2") (pintype "open_collector"))
    )
    (net (code "22") (name "-A00") (class "Default")
      (node (ref "A20") (pin "D2") (pinfunction "PU0_D2") (pintype "input"))
      (node (ref "B29") (pin "M2") (pinfunction "O_M2") (pintype "open_collector"))
      (node (ref "C37") (pin "K2") (pinfunction "PU0_K2") (pintype "input"))
      (node (ref "E12") (pin "K2") (pinfunction "PU1_K2") (pintype "input"))
    )
    (net (code "23") (name "-A1") (class "Default")
      (node (ref "B10") (pin "S2") (pinfunction "0_S2") (pintype "open_collector"))
      (node (ref "E09") (pin "T2") (pinfunction "I$1_T2") (pintype "input"))
    )
    (net (code "24") (name "-A12") (class "Default")
      (node (ref "A28") (pin "E2") (pinfunction "E_E2") (pintype "input"))
      (node (ref "A28") (pin "H2") (pinfunction "H_H2") (pintype "input"))
      (node (ref "A28") (pin "S2") (pinfunction "H_S2") (pintype "input"))
      (node (ref "A29") (pin "N2") (pinfunction "PU0_N2") (pintype "input"))
      (node (ref "B27") (pin "H2") (pinfunction "H_H2") (pintype "input"))
      (node (ref "B27") (pin "P2") (pinfunction "E_P2") (pintype "input"))
      (node (ref "B27") (pin "S2") (pinfunction "H_S2") (pintype "input"))
      (node (ref "B29") (pin "V2") (pinfunction "I$1_V2") (pintype "passive"))
      (node (ref "B30") (pin "T2") (pinfunction "O_T2") (pintype "open_collector"))
      (node (ref "B31") (pin "K2") (pinfunction "PU0_K2") (pintype "input"))
      (node (ref "B34") (pin "N2") (pinfunction "PU0_N2") (pintype "input"))
      (node (ref "B35") (pin "D2") (pinfunction "PU0_D2") (pintype "input"))
      (node (ref "B35") (pin "N2") (pinfunction "PU0_N2") (pintype "input"))
      (node (ref "C38") (pin "P2") (pinfunction "E_P2") (pintype "input"))
      (node (ref "C38") (pin "S2") (pinfunction "H_S2") (pintype "input"))
      (node (ref "D09") (pin "D2") (pinfunction "PU0_D2") (pintype "input"))
      (node (ref "D09") (pin "R2") (pinfunction "PU0_R2") (pintype "input"))
      (node (ref "D10") (pin "D2") (pinfunction "PU0_D2") (pintype "input"))
      (node (ref "F03") (pin "U2") (pinfunction "PU1_U2") (pintype "input"))
      (node (ref "F37") (pin "P2") (pinfunction "E_P2") (pintype "input"))
      (node (ref "F37") (pin "S2") (pinfunction "H_S2") (pintype "input"))
    )
    (net (code "25") (name "-A13") (class "Default")
      (node (ref "B09") (pin "N2") (pinfunction "PU0_N2") (pintype "input"))
      (node (ref "B09") (pin "U2") (pinfunction "PU1_U2") (pintype "input"))
      (node (ref "B10") (pin "D2") (pinfunction "PU0_D2") (pintype "input"))
      (node (ref "B10") (pin "K2") (pinfunction "PU1_K2") (pintype "input"))
      (node (ref "B10") (pin "N2") (pinfunction "PU0_N2") (pintype "input"))
      (node (ref "B10") (pin "U2") (pinfunction "PU1_U2") (pintype "input"))
      (node (ref "B11") (pin "D2") (pinfunction "PU0_D2") (pintype "input"))
      (node (ref "B11") (pin "K2") (pinfunction "PU1_K2") (pintype "input"))
      (node (ref "B11") (pin "N2") (pinfunction "PU0_N2") (pintype "input"))
      (node (ref "B11") (pin "U2") (pinfunction "PU1_U2") (pintype "input"))
      (node (ref "B12") (pin "D2") (pinfunction "PU0_D2") (pintype "input"))
      (node (ref "B12") (pin "K2") (pinfunction "PU1_K2") (pintype "input"))
      (node (ref "B12") (pin "N2") (pinfunction "PU0_N2") (pintype "input"))
      (node (ref "B12") (pin "U2") (pinfunction "PU1_U2") (pintype "input"))
      (node (ref "B28") (pin "D2") (pinfunction "PU0_D2") (pintype "input"))
      (node (ref "B30") (pin "F2") (pinfunction "O_F2") (pintype "open_collector"))
      (node (ref "E03") (pin "R2") (pinfunction "D_R2") (pintype "input"))
      (node (ref "E12") (pin "D2") (pinfunction "PU0_D2") (pintype "input"))
    )
    (net (code "26") (name "-AC11") (class "Default")
      (node (ref "A25") (pin "R2") (pinfunction "I$1_R2") (pintype "input"))
    )
    (net (code "27") (name "-AND") (class "Default")
      (node (ref "B13") (pin "K2") (pinfunction "I$1_K2") (pintype "input"))
      (node (ref "B20") (pin "K2") (pinfunction "I$1_K2") (pintype "input"))
      (node (ref "D17") (pin "M2") (pinfunction "M_M2") (pintype "output"))
      (node (ref "F15") (pin "R2") (pinfunction "I$1_R2") (pintype "input"))
      (node (ref "F20") (pin "E2") (pinfunction "I$1_E2") (pintype "input"))
    )
    (net (code "28") (name "-AST") (class "Default")
      (node (ref "A20") (pin "V2") (pinfunction "I$1_V2") (pintype "passive"))
      (node (ref "D10") (pin "T2") (pinfunction "O_T2") (pintype "open_collector"))
    )
    (net (code "29") (name "-BMB00") (class "Default")
      (node (ref "C36") (pin "D2") (pinfunction "O$1_D2") (pintype "open_collector"))
    )
    (net (code "30") (name "-BMB01") (class "Default")
      (node (ref "C36") (pin "F2") (pinfunction "O$1_F2") (pintype "open_collector"))
    )
    (net (code "31") (name "-BMB02") (class "Default")
      (node (ref "C36") (pin "J2") (pinfunction "O$1_J2") (pintype "open_collector"))
    )
    (net (code "32") (name "-BMB03") (class "Default")
      (node (ref "B37") (pin "J2") (pinfunction "O$1_J2") (pintype "open_collector"))
    )
    (net (code "33") (name "-BMB04") (class "Default")
      (node (ref "B37") (pin "N2") (pinfunction "O$1_N2") (pintype "open_collector"))
    )
    (net (code "34") (name "-BMB05") (class "Default")
      (node (ref "B37") (pin "T2") (pinfunction "O$1_T2") (pintype "open_collector"))
    )
    (net (code "35") (name "-BMB06") (class "Default")
      (node (ref "A17") (pin "F2") (pinfunction "O$1_F2") (pintype "open_collector"))
    )
    (net (code "36") (name "-BMB07") (class "Default")
      (node (ref "C05") (pin "T2") (pinfunction "O$1_T2") (pintype "open_collector"))
    )
    (net (code "37") (name "-BMB08") (class "Default")
      (node (ref "C13") (pin "L2") (pinfunction "O$1_L2") (pintype "open_collector"))
    )
    (net (code "38") (name "-BMB09") (class "Default")
      (node (ref "C36") (pin "L2") (pinfunction "O$1_L2") (pintype "open_collector"))
    )
    (net (code "39") (name "-BMB10") (class "Default")
      (node (ref "C36") (pin "N2") (pinfunction "O$1_N2") (pintype "open_collector"))
    )
    (net (code "40") (name "-BMB11") (class "Default")
      (node (ref "C36") (pin "R2") (pinfunction "O$1_R2") (pintype "open_collector"))
    )
    (net (code "41") (name "-BT(00-01)") (class "Default")
      (node (ref "A26") (pin "F2") (pinfunction "O$1_F2") (pintype "open_collector"))
      (node (ref "B29") (pin "E2") (pinfunction "EN0_E2") (pintype "passive"))
    )
    (net (code "42") (name "-BT(00-11)") (class "Default")
      (node (ref "A24") (pin "J2") (pinfunction "O$1_J2") (pintype "open_collector"))
      (node (ref "B31") (pin "E2") (pinfunction "EN0_E2") (pintype "passive"))
    )
    (net (code "43") (name "-BT00") (class "Default")
      (node (ref "A24") (pin "E2") (pinfunction "I$1_E2") (pintype "input"))
      (node (ref "A26") (pin "K2") (pinfunction "O$1_K2") (pintype "open_collector"))
    )
    (net (code "44") (name "-BT12") (class "Default")
      (node (ref "A22") (pin "R2") (pinfunction "D_R2") (pintype "input"))
      (node (ref "A26") (pin "S2") (pinfunction "O$1_S2") (pintype "open_collector"))
      (node (ref "B26") (pin "R2") (pinfunction "E_R2") (pintype "input"))
      (node (ref "B30") (pin "S2") (pinfunction "EN0_S2") (pintype "passive"))
    )
    (net (code "45") (name "-BT13") (class "Default")
      (node (ref "A26") (pin "N2") (pinfunction "O$1_N2") (pintype "open_collector"))
      (node (ref "B30") (pin "E2") (pinfunction "EN0_E2") (pintype "passive"))
    )
    (net (code "46") (name "-C") (class "Default")
      (node (ref "A17") (pin "P2") (pinfunction "I$1_P2") (pintype "input"))
      (node (ref "B24") (pin "F2") (pinfunction "O$1_F2") (pintype "open_collector"))
      (node (ref "B24") (pin "K2") (pinfunction "O$1_K2") (pintype "open_collector"))
      (node (ref "B25") (pin "V2") (pinfunction "O$1_V2") (pintype "open_collector"))
      (node (ref "B28") (pin "V2") (pinfunction "EN1_V2") (pintype "input"))
    )
    (net (code "47") (name "-CA") (class "Default")
      (node (ref "A22") (pin "D2") (pinfunction "D_D2") (pintype "input"))
      (node (ref "A22") (pin "J2") (pinfunction "D_J2") (pintype "input"))
      (node (ref "B28") (pin "S2") (pinfunction "0_S2") (pintype "open_collector"))
    )
    (net (code "48") (name "-CL") (class "Default")
      (node (ref "B27") (pin "U2") (pinfunction "K_U2") (pintype "open_collector"))
    )
    (net (code "49") (name "-CLK") (class "Default")
      (node (ref "B09") (pin "D2") (pinfunction "PU0_D2") (pintype "input"))
      (node (ref "B09") (pin "K2") (pinfunction "PU1_K2") (pintype "input"))
    )
    (net (code "50") (name "-CLL") (class "Default")
      (node (ref "B26") (pin "H2") (pinfunction "D_H2") (pintype "input"))
      (node (ref "C08") (pin "H2") (pinfunction "D_H2") (pintype "input"))
      (node (ref "E13") (pin "S2") (pinfunction "O$1_S2") (pintype "open_collector"))
      (node (ref "F19") (pin "P2") (pinfunction "I$1_P2") (pintype "input"))
    )
    (net (code "51") (name "-CMA") (class "Default")
      (node (ref "F14") (pin "K2") (pinfunction "O$1_K2") (pintype "open_collector"))
      (node (ref "F14") (pin "M2") (pinfunction "I$2_M2") (pintype "input"))
    )
    (net (code "52") (name "-CMB") (class "Default")
      (node (ref "C37") (pin "F2") (pinfunction "O_F2") (pintype "open_collector"))
      (node (ref "D11") (pin "M2") (pinfunction "SET_M2") (pintype "passive"))
      (node (ref "D12") (pin "M2") (pinfunction "SET_M2") (pintype "passive"))
      (node (ref "D13") (pin "M2") (pinfunction "SET_M2") (pintype "passive"))
      (node (ref "D14") (pin "M2") (pinfunction "SET_M2") (pintype "passive"))
      (node (ref "D15") (pin "M2") (pinfunction "SET_M2") (pintype "passive"))
      (node (ref "D16") (pin "M2") (pinfunction "SET_M2") (pintype "passive"))
      (node (ref "F06") (pin "F2") (pinfunction "D_F2") (pintype "input"))
    )
    (net (code "53") (name "-CML") (class "Default")
      (node (ref "A21") (pin "L2") (pinfunction "I$2_L2") (pintype "input"))
      (node (ref "E13") (pin "V2") (pinfunction "O$1_V2") (pintype "open_collector"))
      (node (ref "F13") (pin "E2") (pinfunction "I$1_E2") (pintype "input"))
    )
    (net (code "54") (name "-CONS") (class "Default")
      (node (ref "A01") (pin "U2") (pinfunction "P$2_U2") (pintype "bidirectional"))
      (node (ref "C37") (pin "S2") (pinfunction "EN0_S2") (pintype "passive"))
      (node (ref "F07") (pin "E2") (pinfunction "I$2_E2") (pintype "input"))
    )
    (net (code "55") (name "-CP") (class "Default")
      (node (ref "B21") (pin "P2") (pinfunction "D_P2") (pintype "input"))
      (node (ref "C37") (pin "T2") (pinfunction "O_T2") (pintype "open_collector"))
    )
    (net (code "56") (name "-DC") (class "Default")
      (node (ref "A14") (pin "R2") (pinfunction "I$1_R2") (pintype "input"))
      (node (ref "B35") (pin "S2") (pinfunction "0_S2") (pintype "open_collector"))
      (node (ref "B36") (pin "E2") (pinfunction "I$2_E2") (pintype "input"))
    )
    (net (code "57") (name "-DCA") (class "Default")
      (node (ref "B20") (pin "S2") (pinfunction "I$2_S2") (pintype "input"))
      (node (ref "B21") (pin "M2") (pinfunction "E_M2") (pintype "input"))
      (node (ref "D17") (pin "R2") (pinfunction "R_R2") (pintype "output"))
      (node (ref "F20") (pin "M2") (pinfunction "I$1_M2") (pintype "input"))
    )
    (net (code "58") (name "-DEPS") (class "Default")
      (node (ref "A12") (pin "T2") (pinfunction "D_T2") (pintype "input"))
      (node (ref "B01") (pin "H2") (pinfunction "P$2_H2") (pintype "bidirectional"))
      (node (ref "B03") (pin "S2") (pinfunction "EN0_S2") (pintype "passive"))
      (node (ref "B24") (pin "U2") (pinfunction "I$2_U2") (pintype "input"))
    )
    (net (code "59") (name "-DPA") (class "Default")
      (node (ref "A20") (pin "K2") (pinfunction "PU0_K2") (pintype "input"))
      (node (ref "A35") (pin "J2") (pinfunction "D_J2") (pintype "input"))
      (node (ref "B03") (pin "T2") (pinfunction "O_T2") (pintype "open_collector"))
      (node (ref "B35") (pin "U2") (pinfunction "PU1_U2") (pintype "input"))
    )
    (net (code "60") (name "-EPA") (class "Default")
      (node (ref "A29") (pin "U2") (pinfunction "PU1_U2") (pintype "input"))
      (node (ref "A35") (pin "R2") (pinfunction "D_R2") (pintype "input"))
      (node (ref "B03") (pin "M2") (pinfunction "O_M2") (pintype "open_collector"))
      (node (ref "E03") (pin "T2") (pinfunction "D_T2") (pintype "input"))
    )
    (net (code "61") (name "-EX") (class "Default")
      (node (ref "A29") (pin "S2") (pinfunction "0_S2") (pintype "open_collector"))
      (node (ref "B15") (pin "E2") (pinfunction "I$2_E2") (pintype "input"))
      (node (ref "B36") (pin "D2") (pinfunction "I$1_D2") (pintype "input"))
    )
    (net (code "62") (name "-EXS") (class "Default")
      (node (ref "A12") (pin "U2") (pinfunction "E_U2") (pintype "input"))
      (node (ref "B01") (pin "E2") (pinfunction "P$2_E2") (pintype "bidirectional"))
      (node (ref "B03") (pin "L2") (pinfunction "EN0_L2") (pintype "passive"))
      (node (ref "B24") (pin "T2") (pinfunction "I$1_T2") (pintype "input"))
    )
    (net (code "63") (name "-IAC") (class "Default")
      (node (ref "F14") (pin "F2") (pinfunction "O$1_F2") (pintype "open_collector"))
      (node (ref "F14") (pin "L2") (pinfunction "I$1_L2") (pintype "input"))
    )
    (net (code "64") (name "-INH1") (class "Default")
      (node (ref "C21") (pin "T2") (pinfunction "O$1_T2") (pintype "open_collector"))
      (node (ref "C22") (pin "V2") (pinfunction "P$1_V2") (pintype "input"))
      (node (ref "C25") (pin "V2") (pinfunction "P$1_V2") (pintype "input"))
      (node (ref "C27") (pin "V2") (pinfunction "P$1_V2") (pintype "input"))
      (node (ref "D27") (pin "M2") (pinfunction "IN_M2") (pintype "input"))
    )
    (net (code "65") (name "-IOP4") (class "Default")
      (node (ref "E06") (pin "N2") (pinfunction "PU0_N2") (pintype "input"))
    )
    (net (code "66") (name "-IOSKS") (class "Default")
      (node (ref "F03") (pin "R2") (pinfunction "RESET_R2") (pintype "input"))
    )
    (net (code "67") (name "-IOT") (class "Default")
      (node (ref "D17") (pin "U2") (pinfunction "U_U2") (pintype "output"))
      (node (ref "E11") (pin "J2") (pinfunction "I$2_J2") (pintype "input"))
      (node (ref "F20") (pin "U2") (pinfunction "I$1_U2") (pintype "input"))
    )
    (net (code "68") (name "-IR00") (class "Default")
      (node (ref "D17") (pin "J2") (pinfunction "J_J2") (pintype "input"))
      (node (ref "D20") (pin "H2") (pinfunction "0_H2") (pintype "open_collector"))
      (node (ref "D20") (pin "V2") (pinfunction "EN1_V2") (pintype "input"))
    )
    (net (code "69") (name "-IR01") (class "Default")
      (node (ref "D17") (pin "E2") (pinfunction "E_E2") (pintype "input"))
      (node (ref "D19") (pin "L2") (pinfunction "EN1_L2") (pintype "input"))
      (node (ref "D20") (pin "S2") (pinfunction "0_S2") (pintype "open_collector"))
    )
    (net (code "70") (name "-IR02") (class "Default")
      (node (ref "D17") (pin "K2") (pinfunction "K_K2") (pintype "input"))
      (node (ref "D19") (pin "H2") (pinfunction "0_H2") (pintype "open_collector"))
      (node (ref "D19") (pin "V2") (pinfunction "EN1_V2") (pintype "input"))
    )
    (net (code "71") (name "-IR03") (class "Default")
      (node (ref "A18") (pin "U2") (pinfunction "I$1_U2") (pintype "input"))
      (node (ref "C12") (pin "L2") (pinfunction "I$2_L2") (pintype "input"))
      (node (ref "D19") (pin "S2") (pinfunction "0_S2") (pintype "open_collector"))
      (node (ref "E10") (pin "E2") (pinfunction "I$2_E2") (pintype "input"))
    )
    (net (code "72") (name "-IRCLR") (class "Default")
      (node (ref "C37") (pin "M2") (pinfunction "O_M2") (pintype "open_collector"))
      (node (ref "D19") (pin "F2") (pinfunction "RESET_F2") (pintype "input"))
      (node (ref "D19") (pin "R2") (pinfunction "RESET_R2") (pintype "input"))
      (node (ref "D20") (pin "F2") (pinfunction "RESET_F2") (pintype "input"))
      (node (ref "D20") (pin "R2") (pinfunction "RESET_R2") (pintype "input"))
    )
    (net (code "73") (name "-IRSH") (class "Default")
      (node (ref "B22") (pin "M2") (pinfunction "O_M2") (pintype "open_collector"))
      (node (ref "D19") (pin "D2") (pinfunction "PU0_D2") (pintype "input"))
      (node (ref "D19") (pin "K2") (pinfunction "PU1_K2") (pintype "input"))
      (node (ref "D19") (pin "N2") (pinfunction "PU0_N2") (pintype "input"))
      (node (ref "D19") (pin "U2") (pinfunction "PU1_U2") (pintype "input"))
      (node (ref "D20") (pin "D2") (pinfunction "PU0_D2") (pintype "input"))
      (node (ref "D20") (pin "K2") (pinfunction "PU1_K2") (pintype "input"))
      (node (ref "D20") (pin "N2") (pinfunction "PU0_N2") (pintype "input"))
      (node (ref "D20") (pin "U2") (pinfunction "PU1_U2") (pintype "input"))
    )
    (net (code "74") (name "-ISZ") (class "Default")
      (node (ref "B21") (pin "U2") (pinfunction "E_U2") (pintype "input"))
      (node (ref "C11") (pin "T2") (pinfunction "D_T2") (pintype "input"))
      (node (ref "D17") (pin "P2") (pinfunction "P_P2") (pintype "output"))
      (node (ref "F20") (pin "K2") (pinfunction "I$1_K2") (pintype "input"))
    )
    (net (code "75") (name "-JMP") (class "Default")
      (node (ref "D17") (pin "T2") (pinfunction "T_T2") (pintype "output"))
      (node (ref "E10") (pin "M2") (pinfunction "I$2_M2") (pintype "input"))
      (node (ref "F16") (pin "R2") (pinfunction "D_R2") (pintype "input"))
      (node (ref "F20") (pin "S2") (pinfunction "I$1_S2") (pintype "input"))
    )
    (net (code "76") (name "-JMS") (class "Default")
      (node (ref "B20") (pin "R2") (pinfunction "I$1_R2") (pintype "input"))
      (node (ref "D17") (pin "S2") (pinfunction "S_S2") (pintype "output"))
      (node (ref "F15") (pin "L2") (pinfunction "I$2_L2") (pintype "input"))
      (node (ref "F20") (pin "P2") (pinfunction "I$1_P2") (pintype "input"))
    )
    (net (code "77") (name "-L") (class "Default")
      (node (ref "C07") (pin "D2") (pinfunction "I$1_D2") (pintype "input"))
    )
    (net (code "78") (name "-LAS") (class "Default")
      (node (ref "B01") (pin "L2") (pinfunction "P$2_L2") (pintype "bidirectional"))
      (node (ref "B19") (pin "S2") (pinfunction "EN0_S2") (pintype "passive"))
      (node (ref "B20") (pin "E2") (pinfunction "I$2_E2") (pintype "input"))
    )
    (net (code "79") (name "-LD") (class "Default")
      (node (ref "A13") (pin "E2") (pinfunction "E_E2") (pintype "input"))
      (node (ref "B14") (pin "E2") (pinfunction "E_E2") (pintype "input"))
      (node (ref "B35") (pin "H2") (pinfunction "0_H2") (pintype "open_collector"))
      (node (ref "C38") (pin "T2") (pinfunction "J_T2") (pintype "input"))
    )
    (net (code "80") (name "-LP") (class "Default")
      (node (ref "A13") (pin "T2") (pinfunction "D_T2") (pintype "input"))
      (node (ref "A28") (pin "V2") (pinfunction "L_V2") (pintype "input"))
      (node (ref "A36") (pin "E2") (pinfunction "E_E2") (pintype "input"))
      (node (ref "B14") (pin "T2") (pinfunction "D_T2") (pintype "input"))
      (node (ref "B19") (pin "T2") (pinfunction "O_T2") (pintype "open_collector"))
    )
    (net (code "81") (name "-LPA") (class "Default")
      (node (ref "A20") (pin "J2") (pinfunction "I$1_J2") (pintype "passive"))
      (node (ref "A35") (pin "N2") (pinfunction "D_N2") (pintype "input"))
      (node (ref "B03") (pin "F2") (pinfunction "O_F2") (pintype "open_collector"))
      (node (ref "B35") (pin "K2") (pinfunction "PU1_K2") (pintype "input"))
    )
    (net (code "82") (name "-LPC") (class "Default")
      (node (ref "E05") (pin "R2") (pinfunction "R_R2") (pintype "input"))
      (node (ref "E05") (pin "U2") (pinfunction "P$1_U2") (pintype "passive"))
    )
    (net (code "83") (name "-LSH") (class "Default")
      (node (ref "B27") (pin "K2") (pinfunction "K_K2") (pintype "open_collector"))
      (node (ref "B30") (pin "M2") (pinfunction "O_M2") (pintype "open_collector"))
    )
    (net (code "84") (name "-MA00") (class "Default")
      (node (ref "D21") (pin "E2") (pinfunction "IN_E2") (pintype "input"))
    )
    (net (code "85") (name "-MA00B") (class "Default")
      (node (ref "A35") (pin "T2") (pinfunction "D_T2") (pintype "input"))
      (node (ref "F10") (pin "N2") (pinfunction "O$1_N2") (pintype "open_collector"))
    )
    (net (code "86") (name "-MA01") (class "Default")
      (node (ref "D21") (pin "H2") (pinfunction "IN_H2") (pintype "input"))
    )
    (net (code "87") (name "-MA01B") (class "Default")
      (node (ref "A39") (pin "M2") (pinfunction "E_M2") (pintype "input"))
      (node (ref "F10") (pin "J2") (pinfunction "O$1_J2") (pintype "open_collector"))
    )
    (net (code "88") (name "-MA02") (class "Default")
      (node (ref "D21") (pin "K2") (pinfunction "IN_K2") (pintype "input"))
    )
    (net (code "89") (name "-MA02B") (class "Default")
      (node (ref "A39") (pin "L2") (pinfunction "D_L2") (pintype "input"))
      (node (ref "F10") (pin "R2") (pinfunction "O$1_R2") (pintype "open_collector"))
    )
    (net (code "90") (name "-MA03") (class "Default")
      (node (ref "D21") (pin "M2") (pinfunction "IN_M2") (pintype "input"))
    )
    (net (code "91") (name "-MA03B") (class "Default")
      (node (ref "A39") (pin "R2") (pinfunction "E_R2") (pintype "input"))
      (node (ref "F10") (pin "L2") (pinfunction "O$1_L2") (pintype "open_collector"))
    )
    (net (code "92") (name "-MA04") (class "Default")
      (node (ref "A39") (pin "P2") (pinfunction "D_P2") (pintype "input"))
      (node (ref "D21") (pin "P2") (pinfunction "IN_P2") (pintype "input"))
    )
    (net (code "93") (name "-MA05") (class "Default")
      (node (ref "D21") (pin "S2") (pinfunction "IN_S2") (pintype "input"))
    )
    (net (code "94") (name "-MA06") (class "Default")
      (node (ref "D22") (pin "E2") (pinfunction "IN_E2") (pintype "input"))
    )
    (net (code "95") (name "-MA07") (class "Default")
      (node (ref "D22") (pin "H2") (pinfunction "IN_H2") (pintype "input"))
    )
    (net (code "96") (name "-MA08") (class "Default")
      (node (ref "D22") (pin "K2") (pinfunction "IN_K2") (pintype "input"))
    )
    (net (code "97") (name "-MA09") (class "Default")
      (node (ref "D22") (pin "M2") (pinfunction "IN_M2") (pintype "input"))
    )
    (net (code "98") (name "-MA10") (class "Default")
      (node (ref "D22") (pin "P2") (pinfunction "IN_P2") (pintype "input"))
    )
    (net (code "99") (name "-MA11") (class "Default")
      (node (ref "D22") (pin "S2") (pinfunction "IN_S2") (pintype "input"))
      (node (ref "E20") (pin "T2") (pinfunction "1_T2") (pintype "open_collector"))
      (node (ref "F13") (pin "U2") (pinfunction "I$1_U2") (pintype "input"))
    )
    (net (code "100") (name "-MA11B") (class "Default")
      (node (ref "F10") (pin "T2") (pinfunction "O$1_T2") (pintype "open_collector"))
    )
    (net (code "101") (name "-MA12") (class "Default")
      (node (ref "D27") (pin "E2") (pinfunction "IN_E2") (pintype "input"))
    )
    (net (code "102") (name "-MA13") (class "Default")
      (node (ref "D27") (pin "H2") (pinfunction "IN_H2") (pintype "input"))
    )
    (net (code "103") (name "-MA14") (class "Default")
      (node (ref "D27") (pin "K2") (pinfunction "IN_K2") (pintype "input"))
    )
    (net (code "104") (name "-MASH") (class "Default")
      (node (ref "D09") (pin "M2") (pinfunction "O_M2") (pintype "open_collector"))
      (node (ref "E15") (pin "D2") (pinfunction "PU0_D2") (pintype "input"))
      (node (ref "E15") (pin "K2") (pinfunction "PU1_K2") (pintype "input"))
      (node (ref "E15") (pin "N2") (pinfunction "PU0_N2") (pintype "input"))
      (node (ref "E15") (pin "U2") (pinfunction "PU1_U2") (pintype "input"))
      (node (ref "E16") (pin "D2") (pinfunction "PU0_D2") (pintype "input"))
      (node (ref "E16") (pin "K2") (pinfunction "PU1_K2") (pintype "input"))
      (node (ref "E16") (pin "N2") (pinfunction "PU0_N2") (pintype "input"))
      (node (ref "E16") (pin "U2") (pinfunction "PU1_U2") (pintype "input"))
      (node (ref "E17") (pin "D2") (pinfunction "PU0_D2") (pintype "input"))
      (node (ref "E17") (pin "K2") (pinfunction "PU1_K2") (pintype "input"))
      (node (ref "E17") (pin "N2") (pinfunction "PU0_N2") (pintype "input"))
      (node (ref "E17") (pin "U2") (pinfunction "PU1_U2") (pintype "input"))
      (node (ref "E18") (pin "D2") (pinfunction "PU0_D2") (pintype "input"))
      (node (ref "E18") (pin "K2") (pinfunction "PU1_K2") (pintype "input"))
      (node (ref "E18") (pin "N2") (pinfunction "PU0_N2") (pintype "input"))
      (node (ref "E18") (pin "U2") (pinfunction "PU1_U2") (pintype "input"))
      (node (ref "E19") (pin "D2") (pinfunction "PU0_D2") (pintype "input"))
      (node (ref "E19") (pin "K2") (pinfunction "PU1_K2") (pintype "input"))
      (node (ref "E19") (pin "N2") (pinfunction "PU0_N2") (pintype "input"))
      (node (ref "E19") (pin "U2") (pinfunction "PU1_U2") (pintype "input"))
      (node (ref "E20") (pin "D2") (pinfunction "PU0_D2") (pintype "input"))
      (node (ref "E20") (pin "K2") (pinfunction "PU1_K2") (pintype "input"))
      (node (ref "E20") (pin "N2") (pinfunction "PU0_N2") (pintype "input"))
      (node (ref "E20") (pin "U2") (pinfunction "PU1_U2") (pintype "input"))
    )
    (net (code "105") (name "-MB00") (class "Default")
      (node (ref "C21") (pin "E2") (pinfunction "I$1_E2") (pintype "input"))
      (node (ref "F12") (pin "R2") (pinfunction "O$1_R2") (pintype "open_collector"))
    )
    (net (code "106") (name "-MB01") (class "Default")
      (node (ref "C21") (pin "H2") (pinfunction "I$1_H2") (pintype "input"))
      (node (ref "F12") (pin "T2") (pinfunction "O$1_T2") (pintype "open_collector"))
    )
    (net (code "107") (name "-MB02") (class "Default")
      (node (ref "C21") (pin "K2") (pinfunction "I$1_K2") (pintype "input"))
      (node (ref "F11") (pin "D2") (pinfunction "O$1_D2") (pintype "open_collector"))
    )
    (net (code "108") (name "-MB03") (class "Default")
      (node (ref "C21") (pin "M2") (pinfunction "I$1_M2") (pintype "input"))
      (node (ref "F11") (pin "F2") (pinfunction "O$1_F2") (pintype "open_collector"))
    )
    (net (code "109") (name "-MB04") (class "Default")
      (node (ref "C21") (pin "P2") (pinfunction "I$1_P2") (pintype "input"))
      (node (ref "E13") (pin "M2") (pinfunction "I$2_M2") (pintype "input"))
      (node (ref "F11") (pin "J2") (pinfunction "O$1_J2") (pintype "open_collector"))
    )
    (net (code "110") (name "-MB05") (class "Default")
      (node (ref "A39") (pin "U2") (pinfunction "E_U2") (pintype "input"))
      (node (ref "C21") (pin "S2") (pinfunction "I$1_S2") (pintype "input"))
      (node (ref "F11") (pin "L2") (pinfunction "O$1_L2") (pintype "open_collector"))
    )
    (net (code "111") (name "-MB06") (class "Default")
      (node (ref "A39") (pin "T2") (pinfunction "D_T2") (pintype "input"))
      (node (ref "B26") (pin "L2") (pinfunction "D_L2") (pintype "input"))
      (node (ref "C24") (pin "E2") (pinfunction "I$1_E2") (pintype "input"))
      (node (ref "F18") (pin "D2") (pinfunction "O$1_D2") (pintype "open_collector"))
    )
    (net (code "112") (name "-MB07") (class "Default")
      (node (ref "A38") (pin "S2") (pinfunction "I$2_S2") (pintype "input"))
      (node (ref "C24") (pin "H2") (pinfunction "I$1_H2") (pintype "input"))
      (node (ref "F11") (pin "N2") (pinfunction "O$1_N2") (pintype "open_collector"))
    )
    (net (code "113") (name "-MB08") (class "Default")
      (node (ref "C24") (pin "K2") (pinfunction "I$1_K2") (pintype "input"))
      (node (ref "F07") (pin "S2") (pinfunction "I$2_S2") (pintype "input"))
      (node (ref "F11") (pin "R2") (pinfunction "O$1_R2") (pintype "open_collector"))
    )
    (net (code "114") (name "-MB09") (class "Default")
      (node (ref "C24") (pin "M2") (pinfunction "I$1_M2") (pintype "input"))
      (node (ref "F11") (pin "T2") (pinfunction "O$1_T2") (pintype "open_collector"))
    )
    (net (code "115") (name "-MB10") (class "Default")
      (node (ref "C24") (pin "P2") (pinfunction "I$1_P2") (pintype "input"))
      (node (ref "E09") (pin "D2") (pinfunction "I$1_D2") (pintype "input"))
      (node (ref "F13") (pin "L2") (pinfunction "O$1_L2") (pintype "open_collector"))
    )
    (net (code "116") (name "-MB11") (class "Default")
      (node (ref "C24") (pin "S2") (pinfunction "I$1_S2") (pintype "input"))
      (node (ref "D20") (pin "L2") (pinfunction "EN1_L2") (pintype "input"))
      (node (ref "E06") (pin "E2") (pinfunction "EN0_E2") (pintype "input"))
      (node (ref "E06") (pin "L2") (pinfunction "EN1_L2") (pintype "input"))
      (node (ref "F13") (pin "F2") (pinfunction "O$1_F2") (pintype "open_collector"))
    )
    (net (code "117") (name "-MBSH") (class "Default")
      (node (ref "D10") (pin "M2") (pinfunction "O_M2") (pintype "open_collector"))
      (node (ref "D11") (pin "D2") (pinfunction "PU0_D2") (pintype "input"))
      (node (ref "D11") (pin "K2") (pinfunction "PU1_K2") (pintype "input"))
      (node (ref "D11") (pin "N2") (pinfunction "PU0_N2") (pintype "input"))
      (node (ref "D11") (pin "U2") (pinfunction "PU1_U2") (pintype "input"))
      (node (ref "D12") (pin "D2") (pinfunction "PU0_D2") (pintype "input"))
      (node (ref "D12") (pin "K2") (pinfunction "PU1_K2") (pintype "input"))
      (node (ref "D12") (pin "N2") (pinfunction "PU0_N2") (pintype "input"))
      (node (ref "D12") (pin "U2") (pinfunction "PU1_U2") (pintype "input"))
      (node (ref "D13") (pin "D2") (pinfunction "PU0_D2") (pintype "input"))
      (node (ref "D13") (pin "K2") (pinfunction "PU1_K2") (pintype "input"))
      (node (ref "D13") (pin "N2") (pinfunction "PU0_N2") (pintype "input"))
      (node (ref "D13") (pin "U2") (pinfunction "PU1_U2") (pintype "input"))
      (node (ref "D14") (pin "D2") (pinfunction "PU0_D2") (pintype "input"))
      (node (ref "D14") (pin "K2") (pinfunction "PU1_K2") (pintype "input"))
      (node (ref "D14") (pin "N2") (pinfunction "PU0_N2") (pintype "input"))
      (node (ref "D14") (pin "U2") (pinfunction "PU1_U2") (pintype "input"))
      (node (ref "D15") (pin "D2") (pinfunction "PU0_D2") (pintype "input"))
      (node (ref "D15") (pin "K2") (pinfunction "PU1_K2") (pintype "input"))
      (node (ref "D15") (pin "N2") (pinfunction "PU0_N2") (pintype "input"))
      (node (ref "D15") (pin "U2") (pinfunction "PU1_U2") (pintype "input"))
      (node (ref "D16") (pin "D2") (pinfunction "PU0_D2") (pintype "input"))
      (node (ref "D16") (pin "K2") (pinfunction "PU1_K2") (pintype "input"))
      (node (ref "D16") (pin "N2") (pinfunction "PU0_N2") (pintype "input"))
      (node (ref "D16") (pin "U2") (pinfunction "PU1_U2") (pintype "input"))
      (node (ref "E06") (pin "D2") (pinfunction "PU0_D2") (pintype "input"))
      (node (ref "E06") (pin "K2") (pinfunction "PU1_K2") (pintype "input"))
      (node (ref "F05") (pin "D2") (pinfunction "PU0_D2") (pintype "input"))
      (node (ref "F05") (pin "K2") (pinfunction "PU1_K2") (pintype "input"))
    )
    (net (code "118") (name "-MEM00") (class "Default")
      (node (ref "C23") (pin "D2") (pinfunction "OUT_D2") (pintype "output"))
      (node (ref "C30") (pin "D2") (pinfunction "P$1_D2") (pintype "passive"))
      (node (ref "D11") (pin "F2") (pinfunction "RESET_F2") (pintype "input"))
    )
    (net (code "119") (name "-MEM01") (class "Default")
      (node (ref "C23") (pin "F2") (pinfunction "OUT_F2") (pintype "output"))
      (node (ref "C30") (pin "E2") (pinfunction "P$1_E2") (pintype "passive"))
      (node (ref "D11") (pin "R2") (pinfunction "RESET_R2") (pintype "input"))
    )
    (net (code "120") (name "-MEM02") (class "Default")
      (node (ref "C23") (pin "J2") (pinfunction "OUT_J2") (pintype "output"))
      (node (ref "C30") (pin "F2") (pinfunction "P$1_F2") (pintype "passive"))
      (node (ref "D12") (pin "F2") (pinfunction "RESET_F2") (pintype "input"))
    )
    (net (code "121") (name "-MEM03") (class "Default")
      (node (ref "C23") (pin "L2") (pinfunction "OUT_L2") (pintype "output"))
      (node (ref "C30") (pin "H2") (pinfunction "P$1_H2") (pintype "passive"))
      (node (ref "D12") (pin "R2") (pinfunction "RESET_R2") (pintype "input"))
    )
    (net (code "122") (name "-MEM04") (class "Default")
      (node (ref "C23") (pin "N2") (pinfunction "OUT_N2") (pintype "output"))
      (node (ref "C30") (pin "J2") (pinfunction "P$1_J2") (pintype "passive"))
      (node (ref "D13") (pin "F2") (pinfunction "RESET_F2") (pintype "input"))
    )
    (net (code "123") (name "-MEM05") (class "Default")
      (node (ref "C23") (pin "R2") (pinfunction "OUT_R2") (pintype "output"))
      (node (ref "C30") (pin "K2") (pinfunction "P$1_K2") (pintype "passive"))
      (node (ref "D13") (pin "R2") (pinfunction "RESET_R2") (pintype "input"))
    )
    (net (code "124") (name "-MEM06") (class "Default")
      (node (ref "C26") (pin "D2") (pinfunction "OUT_D2") (pintype "output"))
      (node (ref "C30") (pin "L2") (pinfunction "P$1_L2") (pintype "passive"))
      (node (ref "D14") (pin "F2") (pinfunction "RESET_F2") (pintype "input"))
    )
    (net (code "125") (name "-MEM07") (class "Default")
      (node (ref "C26") (pin "F2") (pinfunction "OUT_F2") (pintype "output"))
      (node (ref "C30") (pin "M2") (pinfunction "P$1_M2") (pintype "passive"))
      (node (ref "D14") (pin "R2") (pinfunction "RESET_R2") (pintype "input"))
    )
    (net (code "126") (name "-MEM08") (class "Default")
      (node (ref "C26") (pin "J2") (pinfunction "OUT_J2") (pintype "output"))
      (node (ref "C30") (pin "N2") (pinfunction "P$1_N2") (pintype "passive"))
      (node (ref "D15") (pin "F2") (pinfunction "RESET_F2") (pintype "input"))
    )
    (net (code "127") (name "-MEM09") (class "Default")
      (node (ref "C26") (pin "L2") (pinfunction "OUT_L2") (pintype "output"))
      (node (ref "C30") (pin "P2") (pinfunction "P$1_P2") (pintype "passive"))
      (node (ref "D15") (pin "R2") (pinfunction "RESET_R2") (pintype "input"))
    )
    (net (code "128") (name "-MEM10") (class "Default")
      (node (ref "C26") (pin "N2") (pinfunction "OUT_N2") (pintype "output"))
      (node (ref "C30") (pin "R2") (pinfunction "P$1_R2") (pintype "passive"))
      (node (ref "D16") (pin "F2") (pinfunction "RESET_F2") (pintype "input"))
    )
    (net (code "129") (name "-MEM11") (class "Default")
      (node (ref "C26") (pin "R2") (pinfunction "OUT_R2") (pintype "output"))
      (node (ref "C30") (pin "S2") (pinfunction "P$1_S2") (pintype "passive"))
      (node (ref "D16") (pin "R2") (pinfunction "RESET_R2") (pintype "input"))
    )
    (net (code "130") (name "-MEMPB") (class "Default")
      (node (ref "C26") (pin "T2") (pinfunction "OUT_T2") (pintype "output"))
      (node (ref "C30") (pin "T2") (pinfunction "P$1_T2") (pintype "passive"))
      (node (ref "F05") (pin "M2") (pinfunction "SET_M2") (pintype "passive"))
    )
    (net (code "131") (name "-MR") (class "Default")
      (node (ref "E12") (pin "U2") (pinfunction "PU1_U2") (pintype "input"))
    )
    (net (code "132") (name "-OP1") (class "Default")
      (node (ref "E10") (pin "F2") (pinfunction "O$1_F2") (pintype "open_collector"))
      (node (ref "F16") (pin "T2") (pinfunction "D_T2") (pintype "input"))
      (node (ref "F18") (pin "K2") (pinfunction "I$1_K2") (pintype "input"))
    )
    (net (code "133") (name "-OP2") (class "Default")
      (node (ref "B21") (pin "J2") (pinfunction "E_J2") (pintype "input"))
      (node (ref "B21") (pin "T2") (pinfunction "D_T2") (pintype "input"))
      (node (ref "E09") (pin "M2") (pinfunction "I$2_M2") (pintype "input"))
      (node (ref "E11") (pin "F2") (pinfunction "O$1_F2") (pintype "open_collector"))
      (node (ref "F18") (pin "P2") (pinfunction "I$1_P2") (pintype "input"))
    )
    (net (code "134") (name "-OPR") (class "Default")
      (node (ref "D07") (pin "R2") (pinfunction "I$2_R2") (pintype "input"))
      (node (ref "D17") (pin "V2") (pinfunction "V_V2") (pintype "output"))
      (node (ref "E11") (pin "H2") (pinfunction "I$1_H2") (pintype "input"))
      (node (ref "F19") (pin "K2") (pinfunction "I$1_K2") (pintype "input"))
    )
    (net (code "135") (name "-PBB") (class "Default")
      (node (ref "C24") (pin "U2") (pinfunction "I$1_U2") (pintype "input"))
      (node (ref "D07") (pin "U2") (pinfunction "I$2_U2") (pintype "input"))
      (node (ref "F10") (pin "F2") (pinfunction "O$1_F2") (pintype "open_collector"))
    )
    (net (code "136") (name "-PBSH") (class "Default")
      (node (ref "D10") (pin "F2") (pinfunction "O_F2") (pintype "open_collector"))
      (node (ref "F05") (pin "N2") (pinfunction "PU0_N2") (pintype "input"))
      (node (ref "F05") (pin "U2") (pinfunction "PU1_U2") (pintype "input"))
    )
    (net (code "137") (name "-PE") (class "Default")
      (node (ref "E03") (pin "U2") (pinfunction "E_U2") (pintype "open_collector"))
      (node (ref "E06") (pin "S2") (pinfunction "0_S2") (pintype "open_collector"))
    )
    (net (code "138") (name "-PESEL") (class "Default")
      (node (ref "E06") (pin "P2") (pinfunction "EN0_P2") (pintype "input"))
    )
    (net (code "139") (name "-PE_SET") (class "Default")
      (node (ref "D09") (pin "T2") (pinfunction "O_T2") (pintype "open_collector"))
      (node (ref "E06") (pin "U2") (pinfunction "PU1_U2") (pintype "input"))
    )
    (net (code "140") (name "-PGZ") (class "Default")
      (node (ref "C11") (pin "L2") (pinfunction "D_L2") (pintype "input"))
      (node (ref "E12") (pin "H2") (pinfunction "0_H2") (pintype "open_collector"))
    )
    (net (code "141") (name "-PIR") (class "Default")
      (node (ref "B15") (pin "R2") (pinfunction "I$2_R2") (pintype "input"))
    )
    (net (code "142") (name "-PPC") (class "Default")
      (node (ref "A12") (pin "M2") (pinfunction "E_M2") (pintype "input"))
      (node (ref "A29") (pin "R2") (pinfunction "RESET_R2") (pintype "input"))
      (node (ref "A33") (pin "D2") (pinfunction "D_D2") (pintype "input"))
      (node (ref "A33") (pin "F2") (pinfunction "D_F2") (pintype "input"))
      (node (ref "A33") (pin "J2") (pinfunction "D_J2") (pintype "input"))
      (node (ref "A33") (pin "L2") (pinfunction "D_L2") (pintype "input"))
      (node (ref "A33") (pin "N2") (pinfunction "D_N2") (pintype "input"))
      (node (ref "A33") (pin "R2") (pinfunction "D_R2") (pintype "input"))
      (node (ref "A33") (pin "T2") (pinfunction "D_T2") (pintype "input"))
      (node (ref "A35") (pin "L2") (pinfunction "D_L2") (pintype "input"))
      (node (ref "B19") (pin "L2") (pinfunction "EN0_L2") (pintype "passive"))
      (node (ref "B35") (pin "F2") (pinfunction "RESET_F2") (pintype "input"))
      (node (ref "B35") (pin "R2") (pinfunction "RESET_R2") (pintype "input"))
      (node (ref "C08") (pin "P2") (pinfunction "D_P2") (pintype "input"))
      (node (ref "C08") (pin "T2") (pinfunction "D_T2") (pintype "input"))
    )
    (net (code "143") (name "-PT") (class "Default")
      (node (ref "D06") (pin "L2") (pinfunction "I$1_L2") (pintype "input"))
      (node (ref "E06") (pin "H2") (pinfunction "0_H2") (pintype "open_collector"))
    )
    (net (code "144") (name "-R1MB") (class "Default")
      (node (ref "B16") (pin "P2") (pinfunction "I$1_P2") (pintype "input"))
      (node (ref "D06") (pin "F2") (pinfunction "O$1_F2") (pintype "open_collector"))
      (node (ref "D11") (pin "L2") (pinfunction "EN1_L2") (pintype "input"))
      (node (ref "F05") (pin "E2") (pinfunction "EN0_E2") (pintype "input"))
      (node (ref "F05") (pin "L2") (pinfunction "EN1_L2") (pintype "input"))
    )
    (net (code "145") (name "-READ") (class "Default")
      (node (ref "D27") (pin "P2") (pinfunction "IN_P2") (pintype "input"))
    )
    (net (code "146") (name "-RIMA") (class "Default")
      (node (ref "A18") (pin "M2") (pinfunction "I$1_M2") (pintype "input"))
      (node (ref "E13") (pin "F2") (pinfunction "O$1_F2") (pintype "open_collector"))
      (node (ref "E13") (pin "K2") (pinfunction "O$1_K2") (pintype "open_collector"))
      (node (ref "E14") (pin "F2") (pinfunction "O$1_F2") (pintype "open_collector"))
      (node (ref "E14") (pin "K2") (pinfunction "O$1_K2") (pintype "open_collector"))
      (node (ref "E14") (pin "N2") (pinfunction "O$1_N2") (pintype "open_collector"))
      (node (ref "E14") (pin "S2") (pinfunction "O$1_S2") (pintype "open_collector"))
      (node (ref "E14") (pin "V2") (pinfunction "O$1_V2") (pintype "open_collector"))
      (node (ref "E15") (pin "E2") (pinfunction "EN0_E2") (pintype "input"))
      (node (ref "F15") (pin "H2") (pinfunction "O$1_H2") (pintype "open_collector"))
    )
    (net (code "147") (name "-ROTL") (class "Default")
      (node (ref "B21") (pin "L2") (pinfunction "D_L2") (pintype "input"))
      (node (ref "F17") (pin "N2") (pinfunction "O$1_N2") (pintype "open_collector"))
      (node (ref "F17") (pin "P2") (pinfunction "P$1_P2") (pintype "passive"))
      (node (ref "F17") (pin "S2") (pinfunction "I$2_S2") (pintype "input"))
    )
    (net (code "148") (name "-ROTR") (class "Default")
      (node (ref "A22") (pin "N2") (pinfunction "D_N2") (pintype "input"))
      (node (ref "F17") (pin "H2") (pinfunction "O$1_H2") (pintype "open_collector"))
      (node (ref "F17") (pin "J2") (pinfunction "P$1_J2") (pintype "passive"))
      (node (ref "F17") (pin "R2") (pinfunction "I$1_R2") (pintype "input"))
      (node (ref "F19") (pin "S2") (pinfunction "I$1_S2") (pintype "input"))
    )
    (net (code "149") (name "-RUN") (class "Default")
      (node (ref "A35") (pin "K2") (pinfunction "E_K2") (pintype "open_collector"))
      (node (ref "A35") (pin "P2") (pinfunction "E_P2") (pintype "open_collector"))
      (node (ref "A35") (pin "S2") (pinfunction "E_S2") (pintype "open_collector"))
      (node (ref "B21") (pin "S2") (pinfunction "F_S2") (pintype "open_collector"))
      (node (ref "B31") (pin "S2") (pinfunction "EN0_S2") (pintype "passive"))
      (node (ref "B34") (pin "S2") (pinfunction "0_S2") (pintype "open_collector"))
      (node (ref "B36") (pin "P2") (pinfunction "I$1_P2") (pintype "input"))
    )
    (net (code "150") (name "-S") (class "Default")
      (node (ref "A17") (pin "K2") (pinfunction "I$1_K2") (pintype "input"))
      (node (ref "A21") (pin "H2") (pinfunction "O$1_H2") (pintype "open_collector"))
      (node (ref "A23") (pin "H2") (pinfunction "O$1_H2") (pintype "open_collector"))
      (node (ref "A23") (pin "J2") (pinfunction "P$1_J2") (pintype "passive"))
      (node (ref "A23") (pin "N2") (pinfunction "O$1_N2") (pintype "open_collector"))
      (node (ref "A23") (pin "U2") (pinfunction "O$1_U2") (pintype "open_collector"))
      (node (ref "B28") (pin "L2") (pinfunction "EN1_L2") (pintype "input"))
      (node (ref "B40") (pin "F2") (pinfunction "P$1_F2") (pintype "passive"))
      (node (ref "B40") (pin "J2") (pinfunction "P$1_J2") (pintype "passive"))
      (node (ref "B40") (pin "K2") (pinfunction "P$1_K2") (pintype "passive"))
    )
    (net (code "151") (name "-SA1") (class "Default")
      (node (ref "A38") (pin "U2") (pinfunction "O$1_U2") (pintype "open_collector"))
      (node (ref "A38") (pin "V2") (pinfunction "P$1_V2") (pintype "passive"))
      (node (ref "B10") (pin "V2") (pinfunction "EN1_V2") (pintype "input"))
    )
    (net (code "152") (name "-SAC") (class "Default")
      (node (ref "A20") (pin "F2") (pinfunction "O_F2") (pintype "open_collector"))
      (node (ref "A20") (pin "M2") (pinfunction "O_M2") (pintype "open_collector"))
      (node (ref "D01") (pin "L2") (pinfunction "P$2_L2") (pintype "bidirectional"))
    )
    (net (code "153") (name "-SAC00") (class "Default")
      (node (ref "E01") (pin "H2") (pinfunction "P$2_H2") (pintype "bidirectional"))
    )
    (net (code "154") (name "-SAC01") (class "Default")
      (node (ref "E01") (pin "E2") (pinfunction "P$2_E2") (pintype "bidirectional"))
    )
    (net (code "155") (name "-SAC02") (class "Default")
      (node (ref "D01") (pin "U2") (pinfunction "P$2_U2") (pintype "bidirectional"))
    )
    (net (code "156") (name "-SAC03") (class "Default")
      (node (ref "D01") (pin "P2") (pinfunction "P$2_P2") (pintype "bidirectional"))
    )
    (net (code "157") (name "-SAC04") (class "Default")
      (node (ref "D01") (pin "J2") (pinfunction "P$2_J2") (pintype "bidirectional"))
    )
    (net (code "158") (name "-SAC05") (class "Default")
      (node (ref "D01") (pin "E2") (pinfunction "P$2_E2") (pintype "bidirectional"))
    )
    (net (code "159") (name "-SAC06") (class "Default")
      (node (ref "C01") (pin "U2") (pinfunction "P$2_U2") (pintype "bidirectional"))
    )
    (net (code "160") (name "-SAC07") (class "Default")
      (node (ref "C01") (pin "S2") (pinfunction "P$2_S2") (pintype "bidirectional"))
    )
    (net (code "161") (name "-SAC08") (class "Default")
      (node (ref "C01") (pin "N2") (pinfunction "P$2_N2") (pintype "bidirectional"))
    )
    (net (code "162") (name "-SAC09") (class "Default")
      (node (ref "C01") (pin "J2") (pinfunction "P$2_J2") (pintype "bidirectional"))
    )
    (net (code "163") (name "-SAC10") (class "Default")
      (node (ref "C01") (pin "E2") (pinfunction "P$2_E2") (pintype "bidirectional"))
    )
    (net (code "164") (name "-SAC11") (class "Default")
      (node (ref "B01") (pin "U2") (pinfunction "P$2_U2") (pintype "bidirectional"))
    )
    (net (code "165") (name "-SIK") (class "Default")
      (node (ref "A01") (pin "F2") (pinfunction "P$2_F2") (pintype "bidirectional"))
      (node (ref "B33") (pin "M2") (pinfunction "I$1_M2") (pintype "input"))
    )
    (net (code "166") (name "-SKP") (class "Default")
      (node (ref "F03") (pin "T2") (pinfunction "1_T2") (pintype "open_collector"))
    )
    (net (code "167") (name "-SL") (class "Default")
      (node (ref "A28") (pin "K2") (pinfunction "K_K2") (pintype "open_collector"))
    )
    (net (code "168") (name "-SP") (class "Default")
      (node (ref "B09") (pin "R2") (pinfunction "RESET_R2") (pintype "input"))
      (node (ref "B12") (pin "F2") (pinfunction "RESET_F2") (pintype "input"))
      (node (ref "B19") (pin "P2") (pinfunction "I$1_P2") (pintype "passive"))
      (node (ref "C37") (pin "J2") (pinfunction "I$1_J2") (pintype "passive"))
      (node (ref "E12") (pin "R2") (pinfunction "RESET_R2") (pintype "input"))
    )
    (net (code "169") (name "-SSK") (class "Default")
      (node (ref "A01") (pin "L2") (pinfunction "P$2_L2") (pintype "bidirectional"))
      (node (ref "B34") (pin "P2") (pinfunction "EN0_P2") (pintype "input"))
      (node (ref "B36") (pin "K2") (pinfunction "O$1_K2") (pintype "open_collector"))
      (node (ref "B36") (pin "N2") (pinfunction "O$1_N2") (pintype "open_collector"))
    )
    (net (code "170") (name "-STOS") (class "Default")
      (node (ref "A01") (pin "R2") (pinfunction "P$2_R2") (pintype "bidirectional"))
      (node (ref "A40") (pin "H2") (pinfunction "I$1_H2") (pintype "input"))
    )
    (net (code "171") (name "-STROBE") (class "Default")
      (node (ref "C23") (pin "V2") (pinfunction "P$1_V2") (pintype "input"))
      (node (ref "C26") (pin "V2") (pinfunction "P$1_V2") (pintype "input"))
    )
    (net (code "172") (name "-STS") (class "Default")
      (node (ref "A20") (pin "S2") (pinfunction "EN0_S2") (pintype "passive"))
      (node (ref "B01") (pin "R2") (pinfunction "P$2_R2") (pintype "bidirectional"))
      (node (ref "F16") (pin "J2") (pinfunction "D_J2") (pintype "input"))
    )
    (net (code "173") (name "-SX") (class "Default")
      (node (ref "A21") (pin "D2") (pinfunction "I$1_D2") (pintype "input"))
      (node (ref "A23") (pin "R2") (pinfunction "I$1_R2") (pintype "input"))
      (node (ref "A24") (pin "H2") (pinfunction "I$1_H2") (pintype "input"))
      (node (ref "B25") (pin "K2") (pinfunction "O$1_K2") (pintype "open_collector"))
      (node (ref "B25") (pin "N2") (pinfunction "O$1_N2") (pintype "open_collector"))
      (node (ref "B25") (pin "S2") (pinfunction "O$1_S2") (pintype "open_collector"))
    )
    (net (code "174") (name "-SY") (class "Default")
      (node (ref "A21") (pin "E2") (pinfunction "I$2_E2") (pintype "input"))
      (node (ref "A23") (pin "E2") (pinfunction "I$2_E2") (pintype "input"))
      (node (ref "A24") (pin "U2") (pinfunction "I$1_U2") (pintype "input"))
      (node (ref "A25") (pin "N2") (pinfunction "O$1_N2") (pintype "open_collector"))
      (node (ref "A25") (pin "U2") (pinfunction "O$1_U2") (pintype "open_collector"))
      (node (ref "A27") (pin "K2") (pinfunction "O$1_K2") (pintype "open_collector"))
      (node (ref "A27") (pin "N2") (pinfunction "O$1_N2") (pintype "open_collector"))
      (node (ref "A27") (pin "S2") (pinfunction "O$1_S2") (pintype "open_collector"))
      (node (ref "A34") (pin "H2") (pinfunction "O$1_H2") (pintype "open_collector"))
      (node (ref "B23") (pin "H2") (pinfunction "O$1_H2") (pintype "open_collector"))
      (node (ref "B23") (pin "J2") (pinfunction "P$1_J2") (pintype "passive"))
      (node (ref "B25") (pin "F2") (pinfunction "O$1_F2") (pintype "open_collector"))
    )
    (net (code "175") (name "-T0") (class "Default")
      (node (ref "A26") (pin "H2") (pinfunction "I$1_H2") (pintype "input"))
      (node (ref "A29") (pin "H2") (pinfunction "0_H2") (pintype "open_collector"))
      (node (ref "A30") (pin "V2") (pinfunction "EN1_V2") (pintype "input"))
    )
    (net (code "176") (name "-T1") (class "Default")
      (node (ref "A26") (pin "D2") (pinfunction "I$1_D2") (pintype "input"))
      (node (ref "A30") (pin "L2") (pinfunction "EN1_L2") (pintype "input"))
      (node (ref "A30") (pin "S2") (pinfunction "0_S2") (pintype "open_collector"))
    )
    (net (code "177") (name "-T2") (class "Default")
      (node (ref "A30") (pin "H2") (pinfunction "0_H2") (pintype "open_collector"))
      (node (ref "A31") (pin "V2") (pinfunction "EN1_V2") (pintype "input"))
    )
    (net (code "178") (name "-T3") (class "Default")
      (node (ref "A31") (pin "L2") (pinfunction "EN1_L2") (pintype "input"))
      (node (ref "A31") (pin "S2") (pinfunction "0_S2") (pintype "open_collector"))
    )
    (net (code "179") (name "-T4") (class "Default")
      (node (ref "A26") (pin "P2") (pinfunction "I$1_P2") (pintype "input"))
      (node (ref "A27") (pin "D2") (pinfunction "I$1_D2") (pintype "input"))
      (node (ref "A31") (pin "H2") (pinfunction "0_H2") (pintype "open_collector"))
      (node (ref "A32") (pin "V2") (pinfunction "EN1_V2") (pintype "input"))
    )
    (net (code "180") (name "-T5") (class "Default")
      (node (ref "A26") (pin "L2") (pinfunction "I$1_L2") (pintype "input"))
      (node (ref "A32") (pin "L2") (pinfunction "EN1_L2") (pintype "input"))
      (node (ref "A32") (pin "S2") (pinfunction "0_S2") (pintype "open_collector"))
    )
    (net (code "181") (name "-T6") (class "Default")
      (node (ref "A26") (pin "E2") (pinfunction "I$2_E2") (pintype "input"))
      (node (ref "A26") (pin "J2") (pinfunction "I$2_J2") (pintype "input"))
      (node (ref "A29") (pin "E2") (pinfunction "EN0_E2") (pintype "input"))
      (node (ref "A32") (pin "H2") (pinfunction "0_H2") (pintype "open_collector"))
    )
    (net (code "182") (name "-TAD") (class "Default")
      (node (ref "B13") (pin "L2") (pinfunction "I$2_L2") (pintype "input"))
      (node (ref "B20") (pin "L2") (pinfunction "I$2_L2") (pintype "input"))
      (node (ref "D17") (pin "N2") (pinfunction "N_N2") (pintype "output"))
      (node (ref "E10") (pin "P2") (pinfunction "I$1_P2") (pintype "input"))
      (node (ref "F15") (pin "S2") (pinfunction "I$2_S2") (pintype "input"))
      (node (ref "F16") (pin "L2") (pinfunction "D_L2") (pintype "input"))
      (node (ref "F20") (pin "H2") (pinfunction "I$1_H2") (pintype "input"))
    )
    (net (code "183") (name "-TP") (class "Default")
      (node (ref "A20") (pin "R2") (pinfunction "PU0_R2") (pintype "input"))
      (node (ref "B18") (pin "R2") (pinfunction "PU0_R2") (pintype "input"))
      (node (ref "B19") (pin "R2") (pinfunction "PU0_R2") (pintype "input"))
      (node (ref "C37") (pin "R2") (pinfunction "PU0_R2") (pintype "input"))
      (node (ref "C39") (pin "E2") (pinfunction "P$1_E2") (pintype "passive"))
      (node (ref "C39") (pin "F2") (pinfunction "F_F2") (pintype "output"))
    )
    (net (code "184") (name "-WTB") (class "Default")
      (node (ref "A13") (pin "M2") (pinfunction "E_M2") (pintype "input"))
      (node (ref "A13") (pin "R2") (pinfunction "E_R2") (pintype "input"))
      (node (ref "B13") (pin "S2") (pinfunction "I$2_S2") (pintype "input"))
      (node (ref "B14") (pin "J2") (pinfunction "E_J2") (pintype "input"))
      (node (ref "B14") (pin "P2") (pinfunction "D_P2") (pintype "input"))
      (node (ref "C13") (pin "R2") (pinfunction "O$1_R2") (pintype "open_collector"))
      (node (ref "C37") (pin "L2") (pinfunction "EN0_L2") (pintype "passive"))
    )
    (net (code "185") (name "-WTD") (class "Default")
      (node (ref "A12") (pin "D2") (pinfunction "D_D2") (pintype "input"))
      (node (ref "C10") (pin "R2") (pinfunction "I$1_R2") (pintype "input"))
      (node (ref "C13") (pin "F2") (pinfunction "O$1_F2") (pintype "open_collector"))
    )
    (net (code "186") (name "-WTE") (class "Default")
      (node (ref "B14") (pin "H2") (pinfunction "D_H2") (pintype "input"))
      (node (ref "B14") (pin "R2") (pinfunction "E_R2") (pintype "input"))
      (node (ref "B15") (pin "D2") (pinfunction "I$1_D2") (pintype "input"))
      (node (ref "C13") (pin "T2") (pinfunction "O$1_T2") (pintype "open_collector"))
      (node (ref "F03") (pin "V2") (pinfunction "EN1_V2") (pintype "input"))
    )
    (net (code "187") (name "-WTF") (class "Default")
      (node (ref "A14") (pin "D2") (pinfunction "I$1_D2") (pintype "input"))
      (node (ref "A14") (pin "K2") (pinfunction "I$1_K2") (pintype "input"))
      (node (ref "B13") (pin "D2") (pinfunction "I$1_D2") (pintype "input"))
      (node (ref "B13") (pin "R2") (pinfunction "I$1_R2") (pintype "input"))
      (node (ref "B22") (pin "L2") (pinfunction "EN0_L2") (pintype "passive"))
      (node (ref "B28") (pin "E2") (pinfunction "EN0_E2") (pintype "input"))
      (node (ref "C08") (pin "D2") (pinfunction "D_D2") (pintype "input"))
      (node (ref "C09") (pin "D2") (pinfunction "O$1_D2") (pintype "open_collector"))
      (node (ref "C12") (pin "D2") (pinfunction "I$1_D2") (pintype "input"))
    )
    (net (code "188") (name "-WTI") (class "Default")
      (node (ref "A14") (pin "E2") (pinfunction "I$2_E2") (pintype "input"))
      (node (ref "A14") (pin "L2") (pinfunction "I$2_L2") (pintype "input"))
      (node (ref "A14") (pin "S2") (pinfunction "I$2_S2") (pintype "input"))
      (node (ref "C09") (pin "T2") (pinfunction "O$1_T2") (pintype "open_collector"))
      (node (ref "C10") (pin "D2") (pinfunction "I$1_D2") (pintype "input"))
    )
    (net (code "189") (name "-WTMEM") (class "Default")
      (node (ref "C37") (pin "D2") (pinfunction "PU0_D2") (pintype "input"))
    )
    (net (code "190") (name "-WTMEM_C{slash}W") (class "Default")
      (node (ref "F39") (pin "U2") (pinfunction "K_U2") (pintype "open_collector"))
    )
    (net (code "191") (name "-WTMEM_R{slash}W") (class "Default")
      (node (ref "F38") (pin "U2") (pinfunction "K_U2") (pintype "open_collector"))
    )
    (net (code "192") (name "-WTRD") (class "Default")
      (node (ref "A08") (pin "F2") (pinfunction "O$1_F2") (pintype "open_collector"))
      (node (ref "A08") (pin "K2") (pinfunction "O$1_K2") (pintype "open_collector"))
      (node (ref "A08") (pin "N2") (pinfunction "O$1_N2") (pintype "open_collector"))
      (node (ref "A18") (pin "N2") (pinfunction "O$1_N2") (pintype "open_collector"))
      (node (ref "F37") (pin "T2") (pinfunction "J_T2") (pintype "input"))
      (node (ref "F38") (pin "T2") (pinfunction "J_T2") (pintype "input"))
    )
    (net (code "193") (name "-WTS") (class "Default")
      (node (ref "B16") (pin "D2") (pinfunction "O$1_D2") (pintype "open_collector"))
      (node (ref "B32") (pin "S2") (pinfunction "S_S2") (pintype "input"))
      (node (ref "B40") (pin "L2") (pinfunction "P$1_L2") (pintype "passive"))
      (node (ref "D06") (pin "D2") (pinfunction "I$1_D2") (pintype "input"))
      (node (ref "E12") (pin "S2") (pinfunction "0_S2") (pintype "open_collector"))
    )
    (net (code "194") (name "-WTWR") (class "Default")
      (node (ref "A18") (pin "F2") (pinfunction "O$1_F2") (pintype "open_collector"))
      (node (ref "B17") (pin "F2") (pinfunction "O$1_F2") (pintype "open_collector"))
      (node (ref "D10") (pin "E2") (pinfunction "EN0_E2") (pintype "passive"))
      (node (ref "F37") (pin "R2") (pinfunction "F_R2") (pintype "input"))
      (node (ref "F39") (pin "T2") (pinfunction "J_T2") (pintype "input"))
    )
    (net (code "195") (name "-Z1") (class "Default")
      (node (ref "B28") (pin "J2") (pinfunction "1_J2") (pintype "open_collector"))
    )
    (net (code "196") (name "-[(ISZ*Z1)+JMS+(OP+IOT)*SKP+JMP]") (class "Default")
      (node (ref "F19") (pin "F2") (pinfunction "O$1_F2") (pintype "open_collector"))
    )
    (net (code "197") (name "-[(ISZ*ZI)+JMS+(OP+IOT)*SKP+JMP]") (class "Default")
      (node (ref "A10") (pin "P2") (pinfunction "I$1_P2") (pintype "input"))
    )
    (net (code "198") (name "-[A12*(EX+DC+LD)]") (class "Default")
      (node (ref "A12") (pin "L2") (pinfunction "D_L2") (pintype "input"))
      (node (ref "B34") (pin "R2") (pinfunction "RESET_R2") (pintype "input"))
      (node (ref "C38") (pin "U2") (pinfunction "K_U2") (pintype "open_collector"))
    )
    (net (code "199") (name "-[WTD+WTE+WTF+EX+DC+(WTX*JMS)+WTB]") (class "Default")
      (node (ref "C09") (pin "L2") (pinfunction "O$1_L2") (pintype "open_collector"))
      (node (ref "D09") (pin "L2") (pinfunction "EN0_L2") (pintype "passive"))
    )
    (net (code "200") (name "-[WTE*[(ISZ*ZI)+JMS+(OP+IOT)*SKP]]") (class "Default")
      (node (ref "A13") (pin "H2") (pinfunction "D_H2") (pintype "input"))
      (node (ref "A15") (pin "S2") (pinfunction "O$1_S2") (pintype "open_collector"))
      (node (ref "A18") (pin "S2") (pinfunction "I$1_S2") (pintype "input"))
      (node (ref "C11") (pin "N2") (pinfunction "D_N2") (pintype "input"))
    )
    (net (code "201") (name "-[WTF*-(OP+IOT)]") (class "Default")
      (node (ref "B08") (pin "M2") (pinfunction "I$1_M2") (pintype "input"))
      (node (ref "B17") (pin "S2") (pinfunction "O$1_S2") (pintype "open_collector"))
    )
    (net (code "202") (name "-[WTF+WTX*(JMP+JMS)+WTE+WTB+EX+DC+LD]") (class "Default")
      (node (ref "B08") (pin "J2") (pinfunction "O$1_J2") (pintype "open_collector"))
    )
    (net (code "203") (name "-[WTX(TAD+IAC_CMA)]") (class "Default")
      (node (ref "B27") (pin "J2") (pinfunction "J_J2") (pintype "input"))
      (node (ref "E10") (pin "V2") (pinfunction "O$1_V2") (pintype "open_collector"))
    )
    (net (code "204") (name "-[WTX*(JMP+JMS)]") (class "Default")
      (node (ref "A09") (pin "N2") (pinfunction "O$1_N2") (pintype "open_collector"))
      (node (ref "B13") (pin "E2") (pinfunction "I$2_E2") (pintype "input"))
    )
    (net (code "205") (name "A1") (class "Default")
      (node (ref "B10") (pin "T2") (pinfunction "1_T2") (pintype "open_collector"))
      (node (ref "E09") (pin "P2") (pinfunction "I$1_P2") (pintype "input"))
    )
    (net (code "206") (name "AC00") (class "Default")
      (node (ref "F08") (pin "R2") (pinfunction "I$1_R2") (pintype "input"))
    )
    (net (code "207") (name "AC11B") (class "Default")
      (node (ref "A25") (pin "K2") (pinfunction "I$1_K2") (pintype "input"))
      (node (ref "A27") (pin "M2") (pinfunction "I$2_M2") (pintype "input"))
      (node (ref "A34") (pin "D2") (pinfunction "I$1_D2") (pintype "input"))
      (node (ref "B25") (pin "L2") (pinfunction "I$1_L2") (pintype "input"))
      (node (ref "D07") (pin "H2") (pinfunction "I$1_H2") (pintype "input"))
      (node (ref "D08") (pin "P2") (pinfunction "I$1_P2") (pintype "input"))
    )
    (net (code "208") (name "AND") (class "Default")
      (node (ref "A06") (pin "H2") (pinfunction "I$1_H2") (pintype "input"))
      (node (ref "F20") (pin "D2") (pinfunction "O$1_D2") (pintype "open_collector"))
    )
    (net (code "209") (name "AND+TAD+DCA+IAC+CMA+ROTL+OP2") (class "Default")
      (node (ref "B20") (pin "N2") (pinfunction "O$1_N2") (pintype "open_collector"))
      (node (ref "B20") (pin "P2") (pinfunction "P$1_P2") (pintype "passive"))
    )
    (net (code "210") (name "AND+TAD+ISZ") (class "Default")
      (node (ref "B13") (pin "N2") (pinfunction "O$1_N2") (pintype "open_collector"))
      (node (ref "B13") (pin "P2") (pinfunction "P$1_P2") (pintype "passive"))
      (node (ref "D06") (pin "J2") (pinfunction "I$2_J2") (pintype "input"))
    )
    (net (code "211") (name "AND+TAD+OP1+JMP") (class "Default")
      (node (ref "B17") (pin "H2") (pinfunction "I$1_H2") (pintype "input"))
      (node (ref "C11") (pin "J2") (pinfunction "D_J2") (pintype "input"))
      (node (ref "F15") (pin "U2") (pinfunction "O$1_U2") (pintype "open_collector"))
      (node (ref "F15") (pin "V2") (pinfunction "P$1_V2") (pintype "passive"))
    )
    (net (code "212") (name "AND_TAD+ISZ") (class "Default")
      (node (ref "A08") (pin "J2") (pinfunction "I$2_J2") (pintype "input"))
      (node (ref "A08") (pin "L2") (pinfunction "I$1_L2") (pintype "input"))
    )
    (net (code "213") (name "BPAR") (class "Default")
      (node (ref "F36") (pin "V2") (pinfunction "O$1_V2") (pintype "open_collector"))
    )
    (net (code "214") (name "BT(00-06)") (class "Default")
      (node (ref "A24") (pin "L2") (pinfunction "O$1_L2") (pintype "open_collector"))
      (node (ref "B15") (pin "M2") (pinfunction "I$2_M2") (pintype "input"))
    )
    (net (code "215") (name "BT(07-11)") (class "Default")
      (node (ref "C09") (pin "N2") (pinfunction "O$1_N2") (pintype "open_collector"))
      (node (ref "C10") (pin "K2") (pinfunction "I$1_K2") (pintype "input"))
    )
    (net (code "216") (name "BT00") (class "Default")
      (node (ref "A24") (pin "D2") (pinfunction "O$1_D2") (pintype "open_collector"))
      (node (ref "B25") (pin "H2") (pinfunction "I$1_H2") (pintype "input"))
      (node (ref "B25") (pin "P2") (pinfunction "I$1_P2") (pintype "input"))
      (node (ref "B29") (pin "L2") (pinfunction "EN0_L2") (pintype "passive"))
      (node (ref "E09") (pin "E2") (pinfunction "I$2_E2") (pintype "input"))
      (node (ref "E09") (pin "H2") (pinfunction "I$1_H2") (pintype "input"))
    )
    (net (code "217") (name "BT12") (class "Default")
      (node (ref "B21") (pin "E2") (pinfunction "E_E2") (pintype "input"))
    )
    (net (code "218") (name "C") (class "Default")
      (node (ref "A17") (pin "N2") (pinfunction "O$1_N2") (pintype "open_collector"))
      (node (ref "B28") (pin "P2") (pinfunction "EN0_P2") (pintype "input"))
    )
    (net (code "219") (name "CA") (class "Default")
      (node (ref "A22") (pin "F2") (pinfunction "D_F2") (pintype "input"))
      (node (ref "A22") (pin "L2") (pinfunction "D_L2") (pintype "input"))
      (node (ref "B24") (pin "E2") (pinfunction "I$2_E2") (pintype "input"))
      (node (ref "B24") (pin "J2") (pinfunction "I$2_J2") (pintype "input"))
      (node (ref "B28") (pin "T2") (pinfunction "1_T2") (pintype "open_collector"))
    )
    (net (code "220") (name "CLL") (class "Default")
      (node (ref "A21") (pin "K2") (pinfunction "I$1_K2") (pintype "input"))
      (node (ref "F08") (pin "L2") (pinfunction "I$2_L2") (pintype "input"))
      (node (ref "F19") (pin "N2") (pinfunction "O$1_N2") (pintype "open_collector"))
    )
    (net (code "221") (name "CML") (class "Default")
      (node (ref "B23") (pin "L2") (pinfunction "I$2_L2") (pintype "input"))
      (node (ref "F08") (pin "K2") (pinfunction "I$1_K2") (pintype "input"))
      (node (ref "F13") (pin "D2") (pinfunction "O$1_D2") (pintype "open_collector"))
    )
    (net (code "222") (name "DC") (class "Default")
      (node (ref "B16") (pin "M2") (pinfunction "I$1_M2") (pintype "input"))
      (node (ref "B35") (pin "T2") (pinfunction "1_T2") (pintype "open_collector"))
      (node (ref "D07") (pin "J2") (pinfunction "I$2_J2") (pintype "input"))
    )
    (net (code "223") (name "DCA") (class "Default")
      (node (ref "A06") (pin "P2") (pinfunction "I$1_P2") (pintype "input"))
      (node (ref "A10") (pin "J2") (pinfunction "I$2_J2") (pintype "input"))
      (node (ref "F20") (pin "L2") (pinfunction "O$1_L2") (pintype "open_collector"))
    )
    (net (code "224") (name "EX") (class "Default")
      (node (ref "A29") (pin "T2") (pinfunction "1_T2") (pintype "open_collector"))
    )
    (net (code "225") (name "EX+DC") (class "Default")
      (node (ref "B25") (pin "E2") (pinfunction "I$2_E2") (pintype "input"))
      (node (ref "B25") (pin "J2") (pinfunction "I$2_J2") (pintype "input"))
      (node (ref "B33") (pin "E2") (pinfunction "I$1_E2") (pintype "input"))
      (node (ref "B36") (pin "F2") (pinfunction "O$1_F2") (pintype "open_collector"))
      (node (ref "D17") (pin "D2") (pinfunction "D_D2") (pintype "input"))
      (node (ref "E13") (pin "J2") (pinfunction "I$2_J2") (pintype "input"))
    )
    (net (code "226") (name "GND") (class "Default")
      (node (ref "A16") (pin "N2") (pinfunction "C_N2") (pintype "input"))
      (node (ref "A20") (pin "H2") (pinfunction "G_H2") (pintype "input"))
      (node (ref "A20") (pin "L2") (pinfunction "EN0_L2") (pintype "passive"))
      (node (ref "A20") (pin "N2") (pinfunction "G_N2") (pintype "input"))
      (node (ref "A20") (pin "U2") (pinfunction "G_U2") (pintype "input"))
      (node (ref "A28") (pin "C2") (pinfunction "GND_C2") (pintype "power_in"))
      (node (ref "A28") (pin "N2") (pinfunction "C_N2") (pintype "input"))
      (node (ref "A28") (pin "R2") (pinfunction "F_R2") (pintype "input"))
      (node (ref "A28") (pin "T2") (pinfunction "J_T2") (pintype "input"))
      (node (ref "A29") (pin "P2") (pinfunction "EN0_P2") (pintype "input"))
      (node (ref "A29") (pin "V2") (pinfunction "EN1_V2") (pintype "input"))
      (node (ref "A36") (pin "F2") (pinfunction "F_F2") (pintype "input"))
      (node (ref "A36") (pin "P2") (pinfunction "F_P2") (pintype "input"))
      (node (ref "B03") (pin "E2") (pinfunction "EN0_E2") (pintype "passive"))
      (node (ref "B03") (pin "H2") (pinfunction "G_H2") (pintype "input"))
      (node (ref "B03") (pin "N2") (pinfunction "G_N2") (pintype "input"))
      (node (ref "B03") (pin "U2") (pinfunction "G_U2") (pintype "input"))
      (node (ref "B09") (pin "E2") (pinfunction "EN0_E2") (pintype "input"))
      (node (ref "B09") (pin "L2") (pinfunction "EN1_L2") (pintype "input"))
      (node (ref "B09") (pin "V2") (pinfunction "EN1_V2") (pintype "input"))
      (node (ref "B10") (pin "E2") (pinfunction "EN0_E2") (pintype "input"))
      (node (ref "B10") (pin "P2") (pinfunction "EN0_P2") (pintype "input"))
      (node (ref "B11") (pin "E2") (pinfunction "EN0_E2") (pintype "input"))
      (node (ref "B11") (pin "P2") (pinfunction "EN0_P2") (pintype "input"))
      (node (ref "B12") (pin "E2") (pinfunction "EN0_E2") (pintype "input"))
      (node (ref "B12") (pin "P2") (pinfunction "EN0_P2") (pintype "input"))
      (node (ref "B18") (pin "U2") (pinfunction "G_U2") (pintype "input"))
      (node (ref "B19") (pin "N2") (pinfunction "G_N2") (pintype "input"))
      (node (ref "B19") (pin "U2") (pinfunction "G_U2") (pintype "input"))
      (node (ref "B22") (pin "N2") (pinfunction "G_N2") (pintype "input"))
      (node (ref "B22") (pin "S2") (pinfunction "EN0_S2") (pintype "passive"))
      (node (ref "B22") (pin "U2") (pinfunction "G_U2") (pintype "input"))
      (node (ref "B27") (pin "C2") (pinfunction "GND_C2") (pintype "power_in"))
      (node (ref "B27") (pin "N2") (pinfunction "C_N2") (pintype "input"))
      (node (ref "B29") (pin "H2") (pinfunction "G_H2") (pintype "input"))
      (node (ref "B29") (pin "N2") (pinfunction "G_N2") (pintype "input"))
      (node (ref "B29") (pin "S2") (pinfunction "EN0_S2") (pintype "passive"))
      (node (ref "B29") (pin "U2") (pinfunction "G_U2") (pintype "input"))
      (node (ref "B30") (pin "H2") (pinfunction "G_H2") (pintype "input"))
      (node (ref "B30") (pin "N2") (pinfunction "G_N2") (pintype "input"))
      (node (ref "B30") (pin "U2") (pinfunction "G_U2") (pintype "input"))
      (node (ref "B31") (pin "H2") (pinfunction "G_H2") (pintype "input"))
      (node (ref "B31") (pin "N2") (pinfunction "G_N2") (pintype "input"))
      (node (ref "B31") (pin "U2") (pinfunction "G_U2") (pintype "input"))
      (node (ref "B34") (pin "V2") (pinfunction "EN1_V2") (pintype "input"))
      (node (ref "B35") (pin "E2") (pinfunction "EN0_E2") (pintype "input"))
      (node (ref "B35") (pin "L2") (pinfunction "EN1_L2") (pintype "input"))
      (node (ref "B35") (pin "P2") (pinfunction "EN0_P2") (pintype "input"))
      (node (ref "B35") (pin "V2") (pinfunction "EN1_V2") (pintype "input"))
      (node (ref "C04") (pin "C2") (pinfunction "GND_C2") (pintype "power_in"))
      (node (ref "C28") (pin "C2") (pinfunction "P$2_C2") (pintype "bidirectional"))
      (node (ref "C37") (pin "E2") (pinfunction "EN0_E2") (pintype "passive"))
      (node (ref "C37") (pin "H2") (pinfunction "G_H2") (pintype "input"))
      (node (ref "C37") (pin "N2") (pinfunction "G_N2") (pintype "input"))
      (node (ref "C37") (pin "U2") (pinfunction "G_U2") (pintype "input"))
      (node (ref "C38") (pin "N2") (pinfunction "C_N2") (pintype "input"))
      (node (ref "D06") (pin "T2") (pinfunction "I$1_T2") (pintype "input"))
      (node (ref "D09") (pin "H2") (pinfunction "G_H2") (pintype "input"))
      (node (ref "D09") (pin "N2") (pinfunction "G_N2") (pintype "input"))
      (node (ref "D09") (pin "U2") (pinfunction "G_U2") (pintype "input"))
      (node (ref "D10") (pin "H2") (pinfunction "G_H2") (pintype "input"))
      (node (ref "D10") (pin "N2") (pinfunction "G_N2") (pintype "input"))
      (node (ref "D10") (pin "S2") (pinfunction "EN0_S2") (pintype "passive"))
      (node (ref "D10") (pin "U2") (pinfunction "G_U2") (pintype "input"))
      (node (ref "D28") (pin "C2") (pinfunction "P$2_C2") (pintype "bidirectional"))
      (node (ref "E12") (pin "E2") (pinfunction "EN0_E2") (pintype "input"))
      (node (ref "E12") (pin "P2") (pinfunction "EN0_P2") (pintype "input"))
      (node (ref "E12") (pin "V2") (pinfunction "EN1_V2") (pintype "input"))
      (node (ref "F01") (pin "J2") (pinfunction "P$2_J2") (pintype "bidirectional"))
      (node (ref "F15") (pin "E2") (pinfunction "I$2_E2") (pintype "input"))
      (node (ref "F37") (pin "N2") (pinfunction "C_N2") (pintype "input"))
      (node (ref "F38") (pin "N2") (pinfunction "C_N2") (pintype "input"))
      (node (ref "F39") (pin "N2") (pinfunction "C_N2") (pintype "input"))
    )
    (net (code "227") (name "IAC+CMA") (class "Default")
      (node (ref "B23") (pin "E2") (pinfunction "I$2_E2") (pintype "input"))
      (node (ref "F14") (pin "N2") (pinfunction "O$1_N2") (pintype "open_collector"))
      (node (ref "F19") (pin "U2") (pinfunction "I$1_U2") (pintype "input"))
    )
    (net (code "228") (name "INH1") (class "Default")
      (node (ref "C21") (pin "U2") (pinfunction "I$1_U2") (pintype "input"))
    )
    (net (code "229") (name "IOT") (class "Default")
      (node (ref "A07") (pin "E2") (pinfunction "I$1_E2") (pintype "input"))
      (node (ref "F20") (pin "T2") (pinfunction "O$1_T2") (pintype "open_collector"))
    )
    (net (code "230") (name "IR00") (class "Default")
      (node (ref "D17") (pin "H2") (pinfunction "H_H2") (pintype "input"))
      (node (ref "D20") (pin "J2") (pinfunction "1_J2") (pintype "open_collector"))
      (node (ref "D20") (pin "P2") (pinfunction "EN0_P2") (pintype "input"))
    )
    (net (code "231") (name "IR01") (class "Default")
      (node (ref "D17") (pin "F2") (pinfunction "F_F2") (pintype "input"))
      (node (ref "D19") (pin "E2") (pinfunction "EN0_E2") (pintype "input"))
      (node (ref "D20") (pin "T2") (pinfunction "1_T2") (pintype "open_collector"))
    )
    (net (code "232") (name "IR02") (class "Default")
      (node (ref "D17") (pin "L2") (pinfunction "L_L2") (pintype "input"))
      (node (ref "D19") (pin "J2") (pinfunction "1_J2") (pintype "open_collector"))
      (node (ref "D19") (pin "P2") (pinfunction "EN0_P2") (pintype "input"))
    )
    (net (code "233") (name "IR03") (class "Default")
      (node (ref "A08") (pin "E2") (pinfunction "I$2_E2") (pintype "input"))
      (node (ref "A15") (pin "D2") (pinfunction "I$1_D2") (pintype "input"))
      (node (ref "D19") (pin "T2") (pinfunction "1_T2") (pintype "open_collector"))
      (node (ref "E11") (pin "D2") (pinfunction "I$1_D2") (pintype "input"))
    )
    (net (code "234") (name "IR03*-A1") (class "Default")
      (node (ref "B17") (pin "U2") (pinfunction "I$2_U2") (pintype "input"))
      (node (ref "F13") (pin "J2") (pinfunction "O$1_J2") (pintype "open_collector"))
    )
    (net (code "235") (name "IR03*A1") (class "Default")
      (node (ref "B17") (pin "L2") (pinfunction "I$1_L2") (pintype "input"))
      (node (ref "F13") (pin "N2") (pinfunction "O$1_N2") (pintype "open_collector"))
    )
    (net (code "236") (name "IR03B") (class "Default")
      (node (ref "A18") (pin "T2") (pinfunction "O$1_T2") (pintype "open_collector"))
      (node (ref "E09") (pin "R2") (pinfunction "I$2_R2") (pintype "input"))
      (node (ref "E09") (pin "U2") (pinfunction "I$2_U2") (pintype "input"))
    )
    (net (code "237") (name "ISZ") (class "Default")
      (node (ref "A06") (pin "M2") (pinfunction "I$1_M2") (pintype "input"))
      (node (ref "E11") (pin "T2") (pinfunction "I$1_T2") (pintype "input"))
      (node (ref "F20") (pin "J2") (pinfunction "O$1_J2") (pintype "open_collector"))
    )
    (net (code "238") (name "ISZ+DCA+JMS") (class "Default")
      (node (ref "F18") (pin "T2") (pinfunction "O$1_T2") (pintype "open_collector"))
    )
    (net (code "239") (name "ISZ+SCA+JMS") (class "Default")
      (node (ref "B17") (pin "E2") (pinfunction "I$2_E2") (pintype "input"))
    )
    (net (code "240") (name "JMP") (class "Default")
      (node (ref "A06") (pin "U2") (pinfunction "I$1_U2") (pintype "input"))
      (node (ref "B15") (pin "J2") (pinfunction "I$2_J2") (pintype "input"))
      (node (ref "F20") (pin "R2") (pinfunction "O$1_R2") (pintype "open_collector"))
    )
    (net (code "241") (name "JMS") (class "Default")
      (node (ref "A06") (pin "S2") (pinfunction "I$1_S2") (pintype "input"))
      (node (ref "A10") (pin "E2") (pinfunction "I$2_E2") (pintype "input"))
      (node (ref "A10") (pin "M2") (pinfunction "I$2_M2") (pintype "input"))
      (node (ref "F20") (pin "N2") (pinfunction "O$1_N2") (pintype "open_collector"))
    )
    (net (code "242") (name "JMS+DCA+ISZ+OP2") (class "Default")
      (node (ref "B20") (pin "U2") (pinfunction "O$1_U2") (pintype "open_collector"))
      (node (ref "B20") (pin "V2") (pinfunction "P$1_V2") (pintype "passive"))
      (node (ref "E09") (pin "L2") (pinfunction "I$1_L2") (pintype "input"))
    )
    (net (code "243") (name "L") (class "Default")
      (node (ref "B23") (pin "D2") (pinfunction "I$1_D2") (pintype "input"))
      (node (ref "B23") (pin "K2") (pinfunction "I$1_K2") (pintype "input"))
      (node (ref "C07") (pin "K2") (pinfunction "I$1_K2") (pintype "input"))
    )
    (net (code "244") (name "LD") (class "Default")
      (node (ref "A27") (pin "L2") (pinfunction "I$1_L2") (pintype "input"))
      (node (ref "B35") (pin "J2") (pinfunction "1_J2") (pintype "open_collector"))
    )
    (net (code "245") (name "MA11") (class "Default")
      (node (ref "E20") (pin "S2") (pinfunction "0_S2") (pintype "open_collector"))
      (node (ref "F10") (pin "U2") (pinfunction "I$1_U2") (pintype "input"))
    )
    (net (code "246") (name "MA11B") (class "Default")
      (node (ref "B06") (pin "K2") (pinfunction "I$1_K2") (pintype "input"))
      (node (ref "E13") (pin "E2") (pinfunction "I$2_E2") (pintype "input"))
      (node (ref "E14") (pin "T2") (pinfunction "I$1_T2") (pintype "input"))
      (node (ref "F13") (pin "T2") (pinfunction "O$1_T2") (pintype "open_collector"))
      (node (ref "F15") (pin "D2") (pinfunction "I$1_D2") (pintype "input"))
    )
    (net (code "247") (name "MB00") (class "Default")
      (node (ref "C06") (pin "M2") (pinfunction "I$1_M2") (pintype "input"))
      (node (ref "C36") (pin "E2") (pinfunction "I$1_E2") (pintype "input"))
      (node (ref "F12") (pin "D2") (pinfunction "O$1_D2") (pintype "open_collector"))
    )
    (net (code "248") (name "MB01") (class "Default")
      (node (ref "C06") (pin "H2") (pinfunction "I$1_H2") (pintype "input"))
      (node (ref "C36") (pin "H2") (pinfunction "I$1_H2") (pintype "input"))
      (node (ref "F12") (pin "F2") (pinfunction "O$1_F2") (pintype "open_collector"))
    )
    (net (code "249") (name "MB02") (class "Default")
      (node (ref "C03") (pin "U2") (pinfunction "I$1_U2") (pintype "input"))
      (node (ref "C36") (pin "K2") (pinfunction "I$1_K2") (pintype "input"))
      (node (ref "F12") (pin "J2") (pinfunction "O$1_J2") (pintype "open_collector"))
    )
    (net (code "250") (name "MB03") (class "Default")
      (node (ref "B37") (pin "K2") (pinfunction "I$1_K2") (pintype "input"))
      (node (ref "C03") (pin "P2") (pinfunction "I$1_P2") (pintype "input"))
      (node (ref "D18") (pin "N2") (pinfunction "O$1_N2") (pintype "open_collector"))
    )
    (net (code "251") (name "MB04") (class "Default")
      (node (ref "B37") (pin "P2") (pinfunction "I$1_P2") (pintype "input"))
      (node (ref "C03") (pin "K2") (pinfunction "I$1_K2") (pintype "input"))
      (node (ref "D18") (pin "J2") (pinfunction "O$1_J2") (pintype "open_collector"))
    )
    (net (code "252") (name "MB05") (class "Default")
      (node (ref "B37") (pin "U2") (pinfunction "I$1_U2") (pintype "input"))
      (node (ref "C03") (pin "E2") (pinfunction "I$1_E2") (pintype "input"))
      (node (ref "D18") (pin "R2") (pinfunction "O$1_R2") (pintype "open_collector"))
      (node (ref "E13") (pin "P2") (pinfunction "I$1_P2") (pintype "input"))
      (node (ref "F08") (pin "S2") (pinfunction "I$2_S2") (pintype "input"))
    )
    (net (code "253") (name "MB06") (class "Default")
      (node (ref "A17") (pin "H2") (pinfunction "I$1_H2") (pintype "input"))
      (node (ref "B07") (pin "U2") (pinfunction "I$1_U2") (pintype "input"))
      (node (ref "B26") (pin "D2") (pinfunction "D_D2") (pintype "input"))
      (node (ref "D18") (pin "D2") (pinfunction "O$1_D2") (pintype "open_collector"))
      (node (ref "F09") (pin "E2") (pinfunction "I$2_E2") (pintype "input"))
      (node (ref "F14") (pin "J2") (pinfunction "I$2_J2") (pintype "input"))
    )
    (net (code "254") (name "MB07") (class "Default")
      (node (ref "B07") (pin "P2") (pinfunction "I$1_P2") (pintype "input"))
      (node (ref "C05") (pin "U2") (pinfunction "I$1_U2") (pintype "input"))
      (node (ref "C07") (pin "L2") (pinfunction "I$2_L2") (pintype "input"))
      (node (ref "D18") (pin "L2") (pinfunction "O$1_L2") (pintype "open_collector"))
      (node (ref "E13") (pin "T2") (pinfunction "I$1_T2") (pintype "input"))
    )
    (net (code "255") (name "MB08") (class "Default")
      (node (ref "A38") (pin "R2") (pinfunction "I$1_R2") (pintype "input"))
      (node (ref "B07") (pin "K2") (pinfunction "I$1_K2") (pintype "input"))
      (node (ref "C07") (pin "S2") (pinfunction "I$2_S2") (pintype "input"))
      (node (ref "C13") (pin "M2") (pinfunction "I$1_M2") (pintype "input"))
      (node (ref "D18") (pin "T2") (pinfunction "O$1_T2") (pintype "open_collector"))
      (node (ref "F17") (pin "E2") (pinfunction "I$2_E2") (pintype "input"))
    )
    (net (code "256") (name "MB09") (class "Default")
      (node (ref "B07") (pin "E2") (pinfunction "I$1_E2") (pintype "input"))
      (node (ref "B23") (pin "R2") (pinfunction "I$1_R2") (pintype "input"))
      (node (ref "C36") (pin "M2") (pinfunction "I$1_M2") (pintype "input"))
      (node (ref "F12") (pin "L2") (pinfunction "O$1_L2") (pintype "open_collector"))
      (node (ref "F17") (pin "L2") (pinfunction "I$2_L2") (pintype "input"))
    )
    (net (code "257") (name "MB10") (class "Default")
      (node (ref "A34") (pin "K2") (pinfunction "I$1_K2") (pintype "input"))
      (node (ref "B06") (pin "S2") (pinfunction "I$1_S2") (pintype "input"))
      (node (ref "C36") (pin "P2") (pinfunction "I$1_P2") (pintype "input"))
      (node (ref "F12") (pin "N2") (pinfunction "O$1_N2") (pintype "open_collector"))
    )
    (net (code "258") (name "MB11") (class "Default")
      (node (ref "A27") (pin "P2") (pinfunction "I$1_P2") (pintype "input"))
      (node (ref "B06") (pin "M2") (pinfunction "I$1_M2") (pintype "input"))
      (node (ref "B16") (pin "F2") (pinfunction "O$1_F2") (pintype "open_collector"))
      (node (ref "B26") (pin "M2") (pinfunction "E_M2") (pintype "input"))
      (node (ref "C12") (pin "S2") (pinfunction "I$2_S2") (pintype "input"))
      (node (ref "C36") (pin "S2") (pinfunction "I$1_S2") (pintype "input"))
      (node (ref "D08") (pin "L2") (pinfunction "I$1_L2") (pintype "input"))
      (node (ref "D20") (pin "E2") (pinfunction "EN0_E2") (pintype "input"))
      (node (ref "F14") (pin "E2") (pinfunction "I$2_E2") (pintype "input"))
    )
    (net (code "259") (name "MB11B") (class "Default")
      (node (ref "E14") (pin "D2") (pinfunction "I$1_D2") (pintype "input"))
      (node (ref "E14") (pin "J2") (pinfunction "I$2_J2") (pintype "input"))
    )
    (net (code "260") (name "MEMGO") (class "Default")
      (node (ref "E12") (pin "N2") (pinfunction "PU0_N2") (pintype "input"))
    )
    (net (code "261") (name "N$43") (class "Default")
      (node (ref "F36") (pin "T2") (pinfunction "I$1_T2") (pintype "input"))
    )
    (net (code "262") (name "N$45") (class "Default")
      (node (ref "F06") (pin "N2") (pinfunction "D_N2") (pintype "input"))
    )
    (net (code "263") (name "N$119") (class "Default")
      (node (ref "C12") (pin "E2") (pinfunction "I$2_E2") (pintype "input"))
    )
    (net (code "264") (name "Net-(A02D-P$2)") (class "Default")
      (node (ref "A02") (pin "D2") (pinfunction "P$2_D2") (pintype "bidirectional"))
      (node (ref "A05") (pin "F2") (pinfunction "O$1_F2") (pintype "output"))
    )
    (net (code "265") (name "Net-(A02E-P$2)") (class "Default")
      (node (ref "A02") (pin "E2") (pinfunction "P$2_E2") (pintype "bidirectional"))
      (node (ref "A05") (pin "J2") (pinfunction "O$1_J2") (pintype "output"))
    )
    (net (code "266") (name "Net-(A02F-P$2)") (class "Default")
      (node (ref "A02") (pin "F2") (pinfunction "P$2_F2") (pintype "bidirectional"))
      (node (ref "A05") (pin "L2") (pinfunction "O$1_L2") (pintype "output"))
    )
    (net (code "267") (name "Net-(A02G-P$2)") (class "Default")
      (node (ref "A02") (pin "H2") (pinfunction "P$2_H2") (pintype "bidirectional"))
      (node (ref "A05") (pin "N2") (pinfunction "O$1_N2") (pintype "output"))
    )
    (net (code "268") (name "Net-(A02H-P$2)") (class "Default")
      (node (ref "A02") (pin "J2") (pinfunction "P$2_J2") (pintype "bidirectional"))
      (node (ref "A05") (pin "R2") (pinfunction "O$1_R2") (pintype "output"))
    )
    (net (code "269") (name "Net-(A02I-P$2)") (class "Default")
      (node (ref "A02") (pin "K2") (pinfunction "P$2_K2") (pintype "bidirectional"))
      (node (ref "A05") (pin "T2") (pinfunction "O$1_T2") (pintype "output"))
    )
    (net (code "270") (name "Net-(A02J-P$2)") (class "Default")
      (node (ref "A02") (pin "L2") (pinfunction "P$2_L2") (pintype "bidirectional"))
      (node (ref "A05") (pin "V2") (pinfunction "O$1_V2") (pintype "output"))
    )
    (net (code "271") (name "Net-(A02K-P$2)") (class "Default")
      (node (ref "A02") (pin "M2") (pinfunction "P$2_M2") (pintype "bidirectional"))
      (node (ref "A06") (pin "F2") (pinfunction "O$1_F2") (pintype "output"))
    )
    (net (code "272") (name "Net-(A02L-P$2)") (class "Default")
      (node (ref "A02") (pin "N2") (pinfunction "P$2_N2") (pintype "bidirectional"))
      (node (ref "A06") (pin "J2") (pinfunction "O$1_J2") (pintype "output"))
    )
    (net (code "273") (name "Net-(A02M-P$2)") (class "Default")
      (node (ref "A02") (pin "P2") (pinfunction "P$2_P2") (pintype "bidirectional"))
      (node (ref "A06") (pin "L2") (pinfunction "O$1_L2") (pintype "output"))
    )
    (net (code "274") (name "Net-(A02N-P$2)") (class "Default")
      (node (ref "A02") (pin "R2") (pinfunction "P$2_R2") (pintype "bidirectional"))
      (node (ref "A06") (pin "N2") (pinfunction "O$1_N2") (pintype "output"))
    )
    (net (code "275") (name "Net-(A02O-P$2)") (class "Default")
      (node (ref "A02") (pin "S2") (pinfunction "P$2_S2") (pintype "bidirectional"))
      (node (ref "A06") (pin "R2") (pinfunction "O$1_R2") (pintype "output"))
    )
    (net (code "276") (name "Net-(A02P-P$2)") (class "Default")
      (node (ref "A02") (pin "T2") (pinfunction "P$2_T2") (pintype "bidirectional"))
      (node (ref "A06") (pin "T2") (pinfunction "O$1_T2") (pintype "output"))
    )
    (net (code "277") (name "Net-(A02Q-P$2)") (class "Default")
      (node (ref "A02") (pin "U2") (pinfunction "P$2_U2") (pintype "bidirectional"))
      (node (ref "A06") (pin "V2") (pinfunction "O$1_V2") (pintype "output"))
    )
    (net (code "278") (name "Net-(A02R-P$2)") (class "Default")
      (node (ref "A02") (pin "V2") (pinfunction "P$2_V2") (pintype "bidirectional"))
      (node (ref "A07") (pin "F2") (pinfunction "O$1_F2") (pintype "output"))
    )
    (net (code "279") (name "Net-(A07D-O$1)") (class "Default")
      (node (ref "A07") (pin "J2") (pinfunction "O$1_J2") (pintype "output"))
      (node (ref "B02") (pin "D2") (pinfunction "P$2_D2") (pintype "bidirectional"))
    )
    (net (code "280") (name "Net-(A09B-O$1)") (class "Default")
      (node (ref "A09") (pin "F2") (pinfunction "O$1_F2") (pintype "open_collector"))
      (node (ref "B11") (pin "V2") (pinfunction "EN1_V2") (pintype "input"))
    )
    (net (code "281") (name "Net-(A09F-I$1)") (class "Default")
      (node (ref "A09") (pin "M2") (pinfunction "I$1_M2") (pintype "input"))
      (node (ref "B15") (pin "N2") (pinfunction "O$1_N2") (pintype "open_collector"))
    )
    (net (code "282") (name "Net-(A09I-O$1)") (class "Default")
      (node (ref "A09") (pin "T2") (pinfunction "O$1_T2") (pintype "open_collector"))
      (node (ref "B09") (pin "P2") (pinfunction "EN0_P2") (pintype "input"))
      (node (ref "B17") (pin "K2") (pinfunction "O$1_K2") (pintype "open_collector"))
      (node (ref "C12") (pin "N2") (pinfunction "O$1_N2") (pintype "open_collector"))
      (node (ref "F18") (pin "L2") (pinfunction "O$1_L2") (pintype "open_collector"))
    )
    (net (code "283") (name "Net-(A10D-O$1)") (class "Default")
      (node (ref "A10") (pin "K2") (pinfunction "O$1_K2") (pintype "open_collector"))
      (node (ref "B08") (pin "S2") (pinfunction "I$1_S2") (pintype "input"))
    )
    (net (code "284") (name "Net-(A10F-O$1)") (class "Default")
      (node (ref "A10") (pin "S2") (pinfunction "O$1_S2") (pintype "open_collector"))
      (node (ref "B08") (pin "U2") (pinfunction "I$1_U2") (pintype "input"))
    )
    (net (code "285") (name "Net-(A10G-O$1)") (class "Default")
      (node (ref "A10") (pin "V2") (pinfunction "O$1_V2") (pintype "open_collector"))
      (node (ref "B10") (pin "L2") (pinfunction "EN1_L2") (pintype "input"))
    )
    (net (code "286") (name "Net-(A12A-F)") (class "Default")
      (node (ref "A12") (pin "F2") (pinfunction "F_F2") (pintype "open_collector"))
      (node (ref "A14") (pin "M2") (pinfunction "I$3_M2") (pintype "passive"))
    )
    (net (code "287") (name "Net-(A12E-F)") (class "Default")
      (node (ref "A12") (pin "N2") (pinfunction "F_N2") (pintype "open_collector"))
      (node (ref "B12") (pin "H2") (pinfunction "0_H2") (pintype "open_collector"))
      (node (ref "C09") (pin "S2") (pinfunction "I$1_S2") (pintype "input"))
    )
    (net (code "288") (name "Net-(A12G-F)") (class "Default")
      (node (ref "A12") (pin "V2") (pinfunction "F_V2") (pintype "open_collector"))
      (node (ref "B20") (pin "F2") (pinfunction "I$3_F2") (pintype "passive"))
    )
    (net (code "289") (name "Net-(A13A-F)") (class "Default")
      (node (ref "A13") (pin "F2") (pinfunction "F_F2") (pintype "open_collector"))
      (node (ref "B13") (pin "T2") (pinfunction "I$3_T2") (pintype "passive"))
    )
    (net (code "290") (name "Net-(A13D-F)") (class "Default")
      (node (ref "A13") (pin "K2") (pinfunction "F_K2") (pintype "open_collector"))
      (node (ref "A13") (pin "N2") (pinfunction "F_N2") (pintype "open_collector"))
      (node (ref "A14") (pin "F2") (pinfunction "I$3_F2") (pintype "passive"))
    )
    (net (code "291") (name "Net-(A13F-F)") (class "Default")
      (node (ref "A13") (pin "S2") (pinfunction "F_S2") (pintype "open_collector"))
      (node (ref "A14") (pin "T2") (pinfunction "I$3_T2") (pintype "passive"))
    )
    (net (code "292") (name "Net-(A13G-F)") (class "Default")
      (node (ref "A13") (pin "V2") (pinfunction "F_V2") (pintype "open_collector"))
      (node (ref "B09") (pin "S2") (pinfunction "0_S2") (pintype "open_collector"))
      (node (ref "C08") (pin "S2") (pinfunction "F_S2") (pintype "open_collector"))
      (node (ref "C13") (pin "U2") (pinfunction "I$1_U2") (pintype "input"))
    )
    (net (code "293") (name "Net-(A14G-O$1)") (class "Default")
      (node (ref "A14") (pin "U2") (pinfunction "O$1_U2") (pintype "open_collector"))
      (node (ref "A14") (pin "V2") (pinfunction "P$1_V2") (pintype "passive"))
      (node (ref "A18") (pin "H2") (pinfunction "I$1_H2") (pintype "input"))
    )
    (net (code "294") (name "Net-(A15A-O$1)") (class "Default")
      (node (ref "A15") (pin "F2") (pinfunction "O$1_F2") (pintype "open_collector"))
      (node (ref "A15") (pin "H2") (pinfunction "I$1_H2") (pintype "input"))
    )
    (net (code "295") (name "Net-(A15E-I$2)") (class "Default")
      (node (ref "A15") (pin "M2") (pinfunction "I$2_M2") (pintype "input"))
      (node (ref "B15") (pin "K2") (pinfunction "O$1_K2") (pintype "open_collector"))
    )
    (net (code "296") (name "Net-(A16D-K)") (class "Default")
      (node (ref "A16") (pin "U2") (pinfunction "K_U2") (pintype "open_collector"))
      (node (ref "B28") (pin "K2") (pinfunction "PU1_K2") (pintype "input"))
    )
    (net (code "297") (name "Net-(A18E-I$1)") (class "Default")
      (node (ref "A18") (pin "K2") (pinfunction "I$1_K2") (pintype "input"))
      (node (ref "B15") (pin "V2") (pinfunction "O$1_V2") (pintype "open_collector"))
    )
    (net (code "298") (name "Net-(A18G-I$1)") (class "Default")
      (node (ref "A18") (pin "P2") (pinfunction "I$1_P2") (pintype "input"))
      (node (ref "B15") (pin "F2") (pinfunction "O$1_F2") (pintype "open_collector"))
    )
    (net (code "299") (name "Net-(A20A-EN0)") (class "Default")
      (node (ref "A20") (pin "E2") (pinfunction "EN0_E2") (pintype "passive"))
      (node (ref "B23") (pin "U2") (pinfunction "O$1_U2") (pintype "open_collector"))
      (node (ref "B23") (pin "V2") (pinfunction "P$1_V2") (pintype "passive"))
    )
    (net (code "300") (name "Net-(A20E-O)") (class "Default")
      (node (ref "A20") (pin "T2") (pinfunction "O_T2") (pintype "open_collector"))
      (node (ref "C04") (pin "H2") (pinfunction "H_H2") (pintype "input"))
    )
    (net (code "301") (name "Net-(A21C-I$3)") (class "Default")
      (node (ref "A21") (pin "F2") (pinfunction "I$3_F2") (pintype "passive"))
      (node (ref "A22") (pin "M2") (pinfunction "E_M2") (pintype "open_collector"))
    )
    (net (code "302") (name "Net-(A21E-I$3)") (class "Default")
      (node (ref "A21") (pin "M2") (pinfunction "I$3_M2") (pintype "passive"))
      (node (ref "A22") (pin "U2") (pinfunction "E_U2") (pintype "open_collector"))
    )
    (net (code "303") (name "Net-(A21E-O$1)") (class "Default")
      (node (ref "A21") (pin "N2") (pinfunction "O$1_N2") (pintype "open_collector"))
      (node (ref "A21") (pin "P2") (pinfunction "P$1_P2") (pintype "passive"))
      (node (ref "B27") (pin "T2") (pinfunction "J_T2") (pintype "input"))
    )
    (net (code "304") (name "Net-(A21G-I$3)") (class "Default")
      (node (ref "A21") (pin "T2") (pinfunction "I$3_T2") (pintype "passive"))
      (node (ref "A22") (pin "P2") (pinfunction "E_P2") (pintype "open_collector"))
    )
    (net (code "305") (name "Net-(A21G-O$1)") (class "Default")
      (node (ref "A21") (pin "U2") (pinfunction "O$1_U2") (pintype "open_collector"))
      (node (ref "A21") (pin "V2") (pinfunction "P$1_V2") (pintype "passive"))
      (node (ref "B30") (pin "L2") (pinfunction "EN0_L2") (pintype "passive"))
    )
    (net (code "306") (name "Net-(A22A-E)") (class "Default")
      (node (ref "A22") (pin "E2") (pinfunction "E_E2") (pintype "open_collector"))
      (node (ref "A23") (pin "F2") (pinfunction "I$3_F2") (pintype "passive"))
    )
    (net (code "307") (name "Net-(A22D-E)") (class "Default")
      (node (ref "A22") (pin "H2") (pinfunction "E_H2") (pintype "open_collector"))
      (node (ref "A23") (pin "M2") (pinfunction "I$3_M2") (pintype "passive"))
    )
    (net (code "308") (name "Net-(A22E-E)") (class "Default")
      (node (ref "A22") (pin "K2") (pinfunction "E_K2") (pintype "open_collector"))
      (node (ref "A23") (pin "T2") (pinfunction "I$3_T2") (pintype "passive"))
    )
    (net (code "309") (name "Net-(A22H-E)") (class "Default")
      (node (ref "A22") (pin "S2") (pinfunction "E_S2") (pintype "open_collector"))
      (node (ref "A25") (pin "T2") (pinfunction "I$3_T2") (pintype "passive"))
      (node (ref "B26") (pin "F2") (pinfunction "F_F2") (pintype "open_collector"))
    )
    (net (code "310") (name "Net-(A24E-I$1)") (class "Default")
      (node (ref "A24") (pin "K2") (pinfunction "I$1_K2") (pintype "input"))
      (node (ref "A27") (pin "F2") (pinfunction "O$1_F2") (pintype "open_collector"))
    )
    (net (code "311") (name "Net-(A25E-I$3)") (class "Default")
      (node (ref "A25") (pin "M2") (pinfunction "I$3_M2") (pintype "passive"))
      (node (ref "B26") (pin "N2") (pinfunction "F_N2") (pintype "open_collector"))
      (node (ref "B26") (pin "S2") (pinfunction "F_S2") (pintype "open_collector"))
    )
    (net (code "312") (name "Net-(A28C-F)") (class "Default")
      (node (ref "A28") (pin "F2") (pinfunction "F_F2") (pintype "input"))
      (node (ref "C07") (pin "H2") (pinfunction "O$1_H2") (pintype "open_collector"))
      (node (ref "C07") (pin "J2") (pinfunction "P$1_J2") (pintype "passive"))
    )
    (net (code "313") (name "Net-(A28C-J)") (class "Default")
      (node (ref "A28") (pin "J2") (pinfunction "J_J2") (pintype "input"))
      (node (ref "F08") (pin "N2") (pinfunction "O$1_N2") (pintype "open_collector"))
      (node (ref "F08") (pin "P2") (pinfunction "P$1_P2") (pintype "passive"))
    )
    (net (code "314") (name "Net-(A28D-K)") (class "Default")
      (node (ref "A28") (pin "U2") (pinfunction "K_U2") (pintype "open_collector"))
      (node (ref "A29") (pin "F2") (pinfunction "RESET_F2") (pintype "input"))
      (node (ref "A30") (pin "F2") (pinfunction "RESET_F2") (pintype "input"))
      (node (ref "A30") (pin "R2") (pinfunction "RESET_R2") (pintype "input"))
      (node (ref "A31") (pin "F2") (pinfunction "RESET_F2") (pintype "input"))
      (node (ref "A31") (pin "R2") (pinfunction "RESET_R2") (pintype "input"))
      (node (ref "A32") (pin "F2") (pinfunction "RESET_F2") (pintype "input"))
      (node (ref "A32") (pin "R2") (pinfunction "RESET_R2") (pintype "input"))
    )
    (net (code "315") (name "Net-(A29C-PU0)") (class "Default")
      (node (ref "A29") (pin "D2") (pinfunction "PU0_D2") (pintype "input"))
      (node (ref "A29") (pin "K2") (pinfunction "PU1_K2") (pintype "input"))
      (node (ref "A30") (pin "D2") (pinfunction "PU0_D2") (pintype "input"))
      (node (ref "A30") (pin "K2") (pinfunction "PU1_K2") (pintype "input"))
      (node (ref "A30") (pin "N2") (pinfunction "PU0_N2") (pintype "input"))
      (node (ref "A30") (pin "U2") (pinfunction "PU1_U2") (pintype "input"))
      (node (ref "A31") (pin "D2") (pinfunction "PU0_D2") (pintype "input"))
      (node (ref "A31") (pin "K2") (pinfunction "PU1_K2") (pintype "input"))
      (node (ref "A31") (pin "N2") (pinfunction "PU0_N2") (pintype "input"))
      (node (ref "A31") (pin "U2") (pinfunction "PU1_U2") (pintype "input"))
      (node (ref "A32") (pin "D2") (pinfunction "PU0_D2") (pintype "input"))
      (node (ref "A32") (pin "K2") (pinfunction "PU1_K2") (pintype "input"))
      (node (ref "A32") (pin "N2") (pinfunction "PU0_N2") (pintype "input"))
      (node (ref "A32") (pin "U2") (pinfunction "PU1_U2") (pintype "input"))
      (node (ref "B31") (pin "T2") (pinfunction "O_T2") (pintype "open_collector"))
    )
    (net (code "316") (name "Net-(A34E-I$3)") (class "Default")
      (node (ref "A34") (pin "M2") (pinfunction "I$3_M2") (pintype "passive"))
      (node (ref "A35") (pin "H2") (pinfunction "E_H2") (pintype "open_collector"))
    )
    (net (code "317") (name "Net-(A34E-O$1)") (class "Default")
      (node (ref "A34") (pin "N2") (pinfunction "O$1_N2") (pintype "open_collector"))
      (node (ref "A34") (pin "P2") (pinfunction "P$1_P2") (pintype "passive"))
      (node (ref "B31") (pin "L2") (pinfunction "EN0_L2") (pintype "passive"))
    )
    (net (code "318") (name "Net-(A35I-E)") (class "Default")
      (node (ref "A35") (pin "U2") (pinfunction "E_U2") (pintype "open_collector"))
      (node (ref "A38") (pin "T2") (pinfunction "I$3_T2") (pintype "passive"))
      (node (ref "A39") (pin "N2") (pinfunction "F_N2") (pintype "open_collector"))
      (node (ref "A39") (pin "S2") (pinfunction "F_S2") (pintype "open_collector"))
      (node (ref "A39") (pin "V2") (pinfunction "F_V2") (pintype "open_collector"))
    )
    (net (code "319") (name "Net-(A36C-J)") (class "Default")
      (node (ref "A36") (pin "J2") (pinfunction "J_J2") (pintype "passive"))
      (node (ref "A36") (pin "K2") (pinfunction "K_K2") (pintype "passive"))
    )
    (net (code "320") (name "Net-(A36C-M)") (class "Default")
      (node (ref "A36") (pin "M2") (pinfunction "M_M2") (pintype "output"))
      (node (ref "B03") (pin "D2") (pinfunction "PU0_D2") (pintype "input"))
    )
    (net (code "321") (name "Net-(A36D-J)") (class "Default")
      (node (ref "A36") (pin "S2") (pinfunction "J_S2") (pintype "passive"))
      (node (ref "A36") (pin "T2") (pinfunction "K_T2") (pintype "passive"))
    )
    (net (code "322") (name "Net-(A36D-M)") (class "Default")
      (node (ref "A36") (pin "V2") (pinfunction "M_V2") (pintype "output"))
      (node (ref "B03") (pin "K2") (pinfunction "PU0_K2") (pintype "input"))
      (node (ref "B03") (pin "R2") (pinfunction "PU0_R2") (pintype "input"))
    )
    (net (code "323") (name "Net-(A40B-O$1)") (class "Default")
      (node (ref "A40") (pin "F2") (pinfunction "O$1_F2") (pintype "open_collector"))
      (node (ref "B36") (pin "H2") (pinfunction "I$1_H2") (pintype "input"))
    )
    (net (code "324") (name "Net-(B02L-P$2)") (class "Default")
      (node (ref "B02") (pin "N2") (pinfunction "P$2_N2") (pintype "bidirectional"))
      (node (ref "B06") (pin "L2") (pinfunction "O$1_L2") (pintype "output"))
    )
    (net (code "325") (name "Net-(B02M-P$2)") (class "Default")
      (node (ref "B02") (pin "P2") (pinfunction "P$2_P2") (pintype "bidirectional"))
      (node (ref "B06") (pin "N2") (pinfunction "O$1_N2") (pintype "output"))
    )
    (net (code "326") (name "Net-(B02P-P$2)") (class "Default")
      (node (ref "B02") (pin "T2") (pinfunction "P$2_T2") (pintype "bidirectional"))
      (node (ref "B06") (pin "R2") (pinfunction "O$1_R2") (pintype "output"))
    )
    (net (code "327") (name "Net-(B02Q-P$2)") (class "Default")
      (node (ref "B02") (pin "U2") (pinfunction "P$2_U2") (pintype "bidirectional"))
      (node (ref "B06") (pin "T2") (pinfunction "O$1_T2") (pintype "output"))
    )
    (net (code "328") (name "Net-(B05A-P$1)") (class "Default")
      (node (ref "B05") (pin "D2") (pinfunction "P$1_D2") (pintype "passive"))
      (node (ref "C03") (pin "S2") (pinfunction "I$1_S2") (pintype "input"))
      (node (ref "E16") (pin "S2") (pinfunction "0_S2") (pintype "open_collector"))
      (node (ref "E17") (pin "L2") (pinfunction "EN1_L2") (pintype "input"))
      (node (ref "F10") (pin "M2") (pinfunction "I$1_M2") (pintype "input"))
    )
    (net (code "329") (name "Net-(B06G-I$1)") (class "Default")
      (node (ref "B06") (pin "P2") (pinfunction "I$1_P2") (pintype "input"))
      (node (ref "E20") (pin "H2") (pinfunction "0_H2") (pintype "open_collector"))
      (node (ref "E20") (pin "V2") (pinfunction "EN1_V2") (pintype "input"))
    )
    (net (code "330") (name "Net-(B06I-I$1)") (class "Default")
      (node (ref "B06") (pin "U2") (pinfunction "I$1_U2") (pintype "input"))
      (node (ref "E19") (pin "S2") (pinfunction "0_S2") (pintype "open_collector"))
      (node (ref "E20") (pin "L2") (pinfunction "EN1_L2") (pintype "input"))
    )
    (net (code "331") (name "Net-(B06I-O$1)") (class "Default")
      (node (ref "B06") (pin "V2") (pinfunction "O$1_V2") (pintype "output"))
      (node (ref "C02") (pin "E2") (pinfunction "P$2_E2") (pintype "bidirectional"))
    )
    (net (code "332") (name "Net-(B07A-O$1)") (class "Default")
      (node (ref "B07") (pin "F2") (pinfunction "O$1_F2") (pintype "output"))
      (node (ref "C02") (pin "F2") (pinfunction "P$2_F2") (pintype "bidirectional"))
    )
    (net (code "333") (name "Net-(B07D-I$1)") (class "Default")
      (node (ref "B07") (pin "H2") (pinfunction "I$1_H2") (pintype "input"))
      (node (ref "E19") (pin "H2") (pinfunction "0_H2") (pintype "open_collector"))
      (node (ref "E19") (pin "V2") (pinfunction "EN1_V2") (pintype "input"))
    )
    (net (code "334") (name "Net-(B07D-O$1)") (class "Default")
      (node (ref "B07") (pin "J2") (pinfunction "O$1_J2") (pintype "output"))
      (node (ref "C02") (pin "K2") (pinfunction "P$2_K2") (pintype "bidirectional"))
    )
    (net (code "335") (name "Net-(B07E-O$1)") (class "Default")
      (node (ref "B07") (pin "L2") (pinfunction "O$1_L2") (pintype "output"))
      (node (ref "C02") (pin "L2") (pinfunction "P$2_L2") (pintype "bidirectional"))
    )
    (net (code "336") (name "Net-(B07F-I$1)") (class "Default")
      (node (ref "B07") (pin "M2") (pinfunction "I$1_M2") (pintype "input"))
      (node (ref "E18") (pin "S2") (pinfunction "0_S2") (pintype "open_collector"))
      (node (ref "E19") (pin "L2") (pinfunction "EN1_L2") (pintype "input"))
    )
    (net (code "337") (name "Net-(B07F-O$1)") (class "Default")
      (node (ref "B07") (pin "N2") (pinfunction "O$1_N2") (pintype "output"))
      (node (ref "C02") (pin "P2") (pinfunction "P$2_P2") (pintype "bidirectional"))
    )
    (net (code "338") (name "Net-(B07G-O$1)") (class "Default")
      (node (ref "B07") (pin "R2") (pinfunction "O$1_R2") (pintype "output"))
      (node (ref "C02") (pin "R2") (pinfunction "P$2_R2") (pintype "bidirectional"))
    )
    (net (code "339") (name "Net-(B07H-I$1)") (class "Default")
      (node (ref "B07") (pin "S2") (pinfunction "I$1_S2") (pintype "input"))
      (node (ref "E18") (pin "H2") (pinfunction "0_H2") (pintype "open_collector"))
      (node (ref "E18") (pin "V2") (pinfunction "EN1_V2") (pintype "input"))
    )
    (net (code "340") (name "Net-(B07H-O$1)") (class "Default")
      (node (ref "B07") (pin "T2") (pinfunction "O$1_T2") (pintype "output"))
      (node (ref "C02") (pin "U2") (pinfunction "P$2_U2") (pintype "bidirectional"))
    )
    (net (code "341") (name "Net-(B07I-O$1)") (class "Default")
      (node (ref "B07") (pin "V2") (pinfunction "O$1_V2") (pintype "output"))
      (node (ref "C02") (pin "V2") (pinfunction "P$2_V2") (pintype "bidirectional"))
    )
    (net (code "342") (name "Net-(B08A-I$1)") (class "Default")
      (node (ref "B08") (pin "E2") (pinfunction "I$1_E2") (pintype "input"))
      (node (ref "B09") (pin "T2") (pinfunction "1_T2") (pintype "open_collector"))
    )
    (net (code "343") (name "Net-(B08B-O$1)") (class "Default")
      (node (ref "B08") (pin "F2") (pinfunction "O$1_F2") (pintype "open_collector"))
      (node (ref "B11") (pin "L2") (pinfunction "EN1_L2") (pintype "input"))
      (node (ref "B17") (pin "V2") (pinfunction "O$1_V2") (pintype "open_collector"))
    )
    (net (code "344") (name "Net-(B08E-I$1)") (class "Default")
      (node (ref "B08") (pin "K2") (pinfunction "I$1_K2") (pintype "input"))
      (node (ref "B13") (pin "H2") (pinfunction "O$1_H2") (pintype "open_collector"))
    )
    (net (code "345") (name "Net-(B09C-1)") (class "Default")
      (node (ref "B09") (pin "J2") (pinfunction "1_J2") (pintype "open_collector"))
      (node (ref "B19") (pin "K2") (pinfunction "PU0_K2") (pintype "input"))
    )
    (net (code "346") (name "Net-(B10C-0)") (class "Default")
      (node (ref "B10") (pin "H2") (pinfunction "0_H2") (pintype "open_collector"))
      (node (ref "C13") (pin "P2") (pinfunction "I$1_P2") (pintype "input"))
    )
    (net (code "347") (name "Net-(B10C-1)") (class "Default")
      (node (ref "B10") (pin "J2") (pinfunction "1_J2") (pintype "open_collector"))
      (node (ref "C13") (pin "S2") (pinfunction "I$1_S2") (pintype "input"))
    )
    (net (code "348") (name "Net-(B11C-0)") (class "Default")
      (node (ref "B11") (pin "H2") (pinfunction "0_H2") (pintype "open_collector"))
      (node (ref "C13") (pin "E2") (pinfunction "I$1_E2") (pintype "input"))
    )
    (net (code "349") (name "Net-(B11C-1)") (class "Default")
      (node (ref "B11") (pin "J2") (pinfunction "1_J2") (pintype "open_collector"))
      (node (ref "C13") (pin "H2") (pinfunction "I$1_H2") (pintype "input"))
    )
    (net (code "350") (name "Net-(B11D-0)") (class "Default")
      (node (ref "B11") (pin "S2") (pinfunction "0_S2") (pintype "open_collector"))
      (node (ref "C13") (pin "K2") (pinfunction "I$1_K2") (pintype "input"))
    )
    (net (code "351") (name "Net-(B12C-1)") (class "Default")
      (node (ref "B12") (pin "J2") (pinfunction "1_J2") (pintype "open_collector"))
      (node (ref "B14") (pin "V2") (pinfunction "F_V2") (pintype "open_collector"))
      (node (ref "C09") (pin "E2") (pinfunction "I$1_E2") (pintype "input"))
    )
    (net (code "352") (name "Net-(B12C-EN1)") (class "Default")
      (node (ref "B12") (pin "L2") (pinfunction "EN1_L2") (pintype "input"))
      (node (ref "B15") (pin "S2") (pinfunction "O$1_S2") (pintype "open_collector"))
    )
    (net (code "353") (name "Net-(B12D-0)") (class "Default")
      (node (ref "B12") (pin "S2") (pinfunction "0_S2") (pintype "open_collector"))
      (node (ref "C09") (pin "H2") (pinfunction "I$1_H2") (pintype "input"))
    )
    (net (code "354") (name "Net-(B12D-1)") (class "Default")
      (node (ref "B12") (pin "T2") (pinfunction "1_T2") (pintype "open_collector"))
      (node (ref "C09") (pin "U2") (pinfunction "I$1_U2") (pintype "input"))
    )
    (net (code "355") (name "Net-(B12D-EN1)") (class "Default")
      (node (ref "B12") (pin "V2") (pinfunction "EN1_V2") (pintype "input"))
      (node (ref "B17") (pin "N2") (pinfunction "O$1_N2") (pintype "open_collector"))
    )
    (net (code "356") (name "Net-(B13C-I$3)") (class "Default")
      (node (ref "B13") (pin "F2") (pinfunction "I$3_F2") (pintype "passive"))
      (node (ref "B14") (pin "F2") (pinfunction "F_F2") (pintype "open_collector"))
      (node (ref "B14") (pin "K2") (pinfunction "F_K2") (pintype "open_collector"))
    )
    (net (code "357") (name "Net-(B13E-I$3)") (class "Default")
      (node (ref "B13") (pin "M2") (pinfunction "I$3_M2") (pintype "passive"))
      (node (ref "C11") (pin "U2") (pinfunction "E_U2") (pintype "open_collector"))
    )
    (net (code "358") (name "Net-(B14E-E)") (class "Default")
      (node (ref "B14") (pin "M2") (pinfunction "E_M2") (pintype "input"))
      (node (ref "B31") (pin "M2") (pinfunction "O_M2") (pintype "open_collector"))
    )
    (net (code "359") (name "Net-(B14F-F)") (class "Default")
      (node (ref "B14") (pin "S2") (pinfunction "F_S2") (pintype "open_collector"))
      (node (ref "C08") (pin "F2") (pinfunction "F_F2") (pintype "open_collector"))
      (node (ref "C10") (pin "T2") (pinfunction "I$3_T2") (pintype "passive"))
    )
    (net (code "360") (name "Net-(B16A-I$1)") (class "Default")
      (node (ref "B16") (pin "E2") (pinfunction "I$1_E2") (pintype "input"))
      (node (ref "D06") (pin "V2") (pinfunction "O$1_V2") (pintype "open_collector"))
      (node (ref "D07") (pin "F2") (pinfunction "O$1_F2") (pintype "open_collector"))
      (node (ref "D07") (pin "K2") (pinfunction "O$1_K2") (pintype "open_collector"))
      (node (ref "D08") (pin "F2") (pinfunction "O$1_F2") (pintype "open_collector"))
      (node (ref "D08") (pin "K2") (pinfunction "O$1_K2") (pintype "open_collector"))
      (node (ref "D08") (pin "N2") (pinfunction "O$1_N2") (pintype "open_collector"))
      (node (ref "D08") (pin "S2") (pinfunction "O$1_S2") (pintype "open_collector"))
      (node (ref "D08") (pin "V2") (pinfunction "O$1_V2") (pintype "open_collector"))
    )
    (net (code "361") (name "Net-(B16B-I$1)") (class "Default")
      (node (ref "B16") (pin "H2") (pinfunction "I$1_H2") (pintype "input"))
      (node (ref "D16") (pin "T2") (pinfunction "1_T2") (pintype "open_collector"))
    )
    (net (code "362") (name "Net-(B16E-O$1)") (class "Default")
      (node (ref "B16") (pin "J2") (pinfunction "O$1_J2") (pintype "open_collector"))
      (node (ref "D06") (pin "K2") (pinfunction "O$1_K2") (pintype "open_collector"))
      (node (ref "D09") (pin "S2") (pinfunction "EN0_S2") (pintype "passive"))
    )
    (net (code "363") (name "Net-(B16F-O$1)") (class "Default")
      (node (ref "B16") (pin "L2") (pinfunction "O$1_L2") (pintype "open_collector"))
      (node (ref "B16") (pin "T2") (pinfunction "O$1_T2") (pintype "open_collector"))
      (node (ref "D07") (pin "N2") (pinfunction "O$1_N2") (pintype "open_collector"))
      (node (ref "D07") (pin "S2") (pinfunction "O$1_S2") (pintype "open_collector"))
      (node (ref "D10") (pin "L2") (pinfunction "EN0_L2") (pintype "passive"))
    )
    (net (code "364") (name "Net-(B16G-O$1)") (class "Default")
      (node (ref "B16") (pin "N2") (pinfunction "O$1_N2") (pintype "open_collector"))
      (node (ref "D11") (pin "E2") (pinfunction "EN0_E2") (pintype "input"))
    )
    (net (code "365") (name "Net-(B18E-EN0)") (class "Default")
      (node (ref "B18") (pin "S2") (pinfunction "EN0_S2") (pintype "passive"))
      (node (ref "B33") (pin "R2") (pinfunction "O$1_R2") (pintype "open_collector"))
    )
    (net (code "366") (name "Net-(B20E-I$3)") (class "Default")
      (node (ref "B20") (pin "M2") (pinfunction "I$3_M2") (pintype "passive"))
      (node (ref "B21") (pin "K2") (pinfunction "F_K2") (pintype "open_collector"))
      (node (ref "B21") (pin "N2") (pinfunction "F_N2") (pintype "open_collector"))
    )
    (net (code "367") (name "Net-(B20G-I$3)") (class "Default")
      (node (ref "B20") (pin "T2") (pinfunction "I$3_T2") (pintype "passive"))
      (node (ref "B21") (pin "V2") (pinfunction "F_V2") (pintype "open_collector"))
    )
    (net (code "368") (name "Net-(B21A-F)") (class "Default")
      (node (ref "B21") (pin "F2") (pinfunction "F_F2") (pintype "open_collector"))
      (node (ref "B23") (pin "F2") (pinfunction "I$3_F2") (pintype "passive"))
    )
    (net (code "369") (name "Net-(B23E-I$3)") (class "Default")
      (node (ref "B23") (pin "M2") (pinfunction "I$3_M2") (pintype "passive"))
      (node (ref "B26") (pin "K2") (pinfunction "F_K2") (pintype "open_collector"))
    )
    (net (code "370") (name "Net-(B23E-O$1)") (class "Default")
      (node (ref "B23") (pin "N2") (pinfunction "O$1_N2") (pintype "open_collector"))
      (node (ref "B23") (pin "P2") (pinfunction "P$1_P2") (pintype "passive"))
      (node (ref "B27") (pin "R2") (pinfunction "F_R2") (pintype "input"))
      (node (ref "C07") (pin "E2") (pinfunction "I$2_E2") (pintype "input"))
    )
    (net (code "371") (name "Net-(B23G-I$3)") (class "Default")
      (node (ref "B23") (pin "T2") (pinfunction "I$3_T2") (pintype "passive"))
      (node (ref "B26") (pin "V2") (pinfunction "F_V2") (pintype "open_collector"))
    )
    (net (code "372") (name "Net-(B24G-O$1)") (class "Default")
      (node (ref "B24") (pin "V2") (pinfunction "O$1_V2") (pintype "open_collector"))
      (node (ref "B33") (pin "S2") (pinfunction "I$1_S2") (pintype "input"))
    )
    (net (code "373") (name "Net-(B31E-PU0)") (class "Default")
      (node (ref "B31") (pin "R2") (pinfunction "PU0_R2") (pintype "input"))
      (node (ref "B32") (pin "D2") (pinfunction "D_D2") (pintype "output"))
    )
    (net (code "374") (name "Net-(B32A-R)") (class "Default")
      (node (ref "B32") (pin "R2") (pinfunction "R_R2") (pintype "passive"))
      (node (ref "B32") (pin "U2") (pinfunction "U_U2") (pintype "passive"))
    )
    (net (code "375") (name "Net-(B33F-O$1)") (class "Default")
      (node (ref "B33") (pin "L2") (pinfunction "O$1_L2") (pintype "open_collector"))
      (node (ref "B36") (pin "L2") (pinfunction "I$1_L2") (pintype "input"))
    )
    (net (code "376") (name "Net-(B34D-PU1)") (class "Default")
      (node (ref "B34") (pin "U2") (pinfunction "PU1_U2") (pintype "input"))
      (node (ref "E11") (pin "S2") (pinfunction "O$1_S2") (pintype "open_collector"))
    )
    (net (code "377") (name "Net-(B36F-O$1)") (class "Default")
      (node (ref "B36") (pin "S2") (pinfunction "O$1_S2") (pintype "open_collector"))
      (node (ref "F07") (pin "D2") (pinfunction "I$1_D2") (pintype "input"))
    )
    (net (code "378") (name "Net-(C03A-O$1)") (class "Default")
      (node (ref "C03") (pin "F2") (pinfunction "O$1_F2") (pintype "output"))
      (node (ref "D02") (pin "J2") (pinfunction "P$2_J2") (pintype "bidirectional"))
    )
    (net (code "379") (name "Net-(C03D-I$1)") (class "Default")
      (node (ref "C03") (pin "H2") (pinfunction "I$1_H2") (pintype "input"))
      (node (ref "E17") (pin "S2") (pinfunction "0_S2") (pintype "open_collector"))
      (node (ref "E18") (pin "L2") (pinfunction "EN1_L2") (pintype "input"))
    )
    (net (code "380") (name "Net-(C03D-O$1)") (class "Default")
      (node (ref "C03") (pin "J2") (pinfunction "O$1_J2") (pintype "output"))
      (node (ref "D02") (pin "K2") (pinfunction "P$2_K2") (pintype "bidirectional"))
    )
    (net (code "381") (name "Net-(C03E-O$1)") (class "Default")
      (node (ref "C03") (pin "L2") (pinfunction "O$1_L2") (pintype "output"))
      (node (ref "D02") (pin "N2") (pinfunction "P$2_N2") (pintype "bidirectional"))
    )
    (net (code "382") (name "Net-(C03F-I$1)") (class "Default")
      (node (ref "C03") (pin "M2") (pinfunction "I$1_M2") (pintype "input"))
      (node (ref "E17") (pin "H2") (pinfunction "0_H2") (pintype "open_collector"))
      (node (ref "E17") (pin "V2") (pinfunction "EN1_V2") (pintype "input"))
    )
    (net (code "383") (name "Net-(C03F-O$1)") (class "Default")
      (node (ref "C03") (pin "N2") (pinfunction "O$1_N2") (pintype "output"))
      (node (ref "D02") (pin "P2") (pinfunction "P$2_P2") (pintype "bidirectional"))
    )
    (net (code "384") (name "Net-(C03G-O$1)") (class "Default")
      (node (ref "C03") (pin "R2") (pinfunction "O$1_R2") (pintype "output"))
      (node (ref "D02") (pin "T2") (pinfunction "P$2_T2") (pintype "bidirectional"))
    )
    (net (code "385") (name "Net-(C03H-O$1)") (class "Default")
      (node (ref "C03") (pin "T2") (pinfunction "O$1_T2") (pintype "output"))
      (node (ref "D02") (pin "U2") (pinfunction "P$2_U2") (pintype "bidirectional"))
    )
    (net (code "386") (name "Net-(C03I-O$1)") (class "Default")
      (node (ref "C03") (pin "V2") (pinfunction "O$1_V2") (pintype "output"))
      (node (ref "E02") (pin "E2") (pinfunction "P$2_E2") (pintype "bidirectional"))
    )
    (net (code "387") (name "Net-(C04C-D)") (class "Default")
      (node (ref "C04") (pin "D2") (pinfunction "D_D2") (pintype "passive"))
      (node (ref "C04") (pin "M2") (pinfunction "M_M2") (pintype "passive"))
    )
    (net (code "388") (name "Net-(C04C-K)") (class "Default")
      (node (ref "C04") (pin "K2") (pinfunction "K_K2") (pintype "open_collector"))
      (node (ref "E11") (pin "R2") (pinfunction "I$2_R2") (pintype "input"))
    )
    (net (code "389") (name "Net-(C06A-I$1)") (class "Default")
      (node (ref "C06") (pin "E2") (pinfunction "I$1_E2") (pintype "input"))
      (node (ref "E16") (pin "H2") (pinfunction "0_H2") (pintype "open_collector"))
      (node (ref "E16") (pin "V2") (pinfunction "EN1_V2") (pintype "input"))
      (node (ref "F10") (pin "S2") (pinfunction "I$1_S2") (pintype "input"))
    )
    (net (code "390") (name "Net-(C06A-O$1)") (class "Default")
      (node (ref "C06") (pin "F2") (pinfunction "O$1_F2") (pintype "output"))
      (node (ref "E02") (pin "F2") (pinfunction "P$2_F2") (pintype "bidirectional"))
    )
    (net (code "391") (name "Net-(C06D-O$1)") (class "Default")
      (node (ref "C06") (pin "J2") (pinfunction "O$1_J2") (pintype "output"))
      (node (ref "E02") (pin "K2") (pinfunction "P$2_K2") (pintype "bidirectional"))
    )
    (net (code "392") (name "Net-(C06E-I$1)") (class "Default")
      (node (ref "C06") (pin "K2") (pinfunction "I$1_K2") (pintype "input"))
      (node (ref "E15") (pin "S2") (pinfunction "0_S2") (pintype "open_collector"))
      (node (ref "E16") (pin "L2") (pinfunction "EN1_L2") (pintype "input"))
      (node (ref "F10") (pin "K2") (pinfunction "I$1_K2") (pintype "input"))
    )
    (net (code "393") (name "Net-(C06E-O$1)") (class "Default")
      (node (ref "C06") (pin "L2") (pinfunction "O$1_L2") (pintype "output"))
      (node (ref "E02") (pin "L2") (pinfunction "P$2_L2") (pintype "bidirectional"))
    )
    (net (code "394") (name "Net-(C06F-O$1)") (class "Default")
      (node (ref "C06") (pin "N2") (pinfunction "O$1_N2") (pintype "output"))
      (node (ref "E02") (pin "P2") (pinfunction "P$2_P2") (pintype "bidirectional"))
    )
    (net (code "395") (name "Net-(C06G-I$1)") (class "Default")
      (node (ref "C06") (pin "P2") (pinfunction "I$1_P2") (pintype "input"))
      (node (ref "E15") (pin "H2") (pinfunction "0_H2") (pintype "open_collector"))
      (node (ref "E15") (pin "V2") (pinfunction "EN1_V2") (pintype "input"))
      (node (ref "F10") (pin "P2") (pinfunction "I$1_P2") (pintype "input"))
    )
    (net (code "396") (name "Net-(C06G-O$1)") (class "Default")
      (node (ref "C06") (pin "R2") (pinfunction "O$1_R2") (pintype "output"))
      (node (ref "E02") (pin "R2") (pinfunction "P$2_R2") (pintype "bidirectional"))
    )
    (net (code "397") (name "Net-(C07C-I$3)") (class "Default")
      (node (ref "C07") (pin "F2") (pinfunction "I$3_F2") (pintype "passive"))
      (node (ref "C08") (pin "K2") (pinfunction "F_K2") (pintype "open_collector"))
    )
    (net (code "398") (name "Net-(C07E-O$1)") (class "Default")
      (node (ref "C07") (pin "N2") (pinfunction "O$1_N2") (pintype "open_collector"))
      (node (ref "C07") (pin "P2") (pinfunction "P$1_P2") (pintype "passive"))
      (node (ref "C07") (pin "R2") (pinfunction "I$1_R2") (pintype "input"))
      (node (ref "F08") (pin "U2") (pinfunction "O$1_U2") (pintype "open_collector"))
      (node (ref "F09") (pin "H2") (pinfunction "O$1_H2") (pintype "open_collector"))
      (node (ref "F18") (pin "H2") (pinfunction "I$1_H2") (pintype "input"))
    )
    (net (code "399") (name "Net-(C07G-O$1)") (class "Default")
      (node (ref "C07") (pin "U2") (pinfunction "O$1_U2") (pintype "open_collector"))
      (node (ref "C07") (pin "V2") (pinfunction "P$1_V2") (pintype "passive"))
      (node (ref "F03") (pin "P2") (pinfunction "EN0_P2") (pintype "input"))
      (node (ref "F07") (pin "U2") (pinfunction "O$1_U2") (pintype "open_collector"))
    )
    (net (code "400") (name "Net-(C09E-I$1)") (class "Default")
      (node (ref "C09") (pin "K2") (pinfunction "I$1_K2") (pintype "input"))
      (node (ref "C10") (pin "N2") (pinfunction "O$1_N2") (pintype "open_collector"))
      (node (ref "C10") (pin "P2") (pinfunction "P$1_P2") (pintype "passive"))
    )
    (net (code "401") (name "Net-(C09F-I$1)") (class "Default")
      (node (ref "C09") (pin "M2") (pinfunction "I$1_M2") (pintype "input"))
      (node (ref "C10") (pin "U2") (pinfunction "O$1_U2") (pintype "open_collector"))
      (node (ref "C10") (pin "V2") (pinfunction "P$1_V2") (pintype "passive"))
    )
    (net (code "402") (name "Net-(C09G-I$1)") (class "Default")
      (node (ref "C09") (pin "P2") (pinfunction "I$1_P2") (pintype "input"))
      (node (ref "C14") (pin "V2") (pinfunction "O$1_V2") (pintype "open_collector"))
    )
    (net (code "403") (name "Net-(C10C-I$3)") (class "Default")
      (node (ref "C10") (pin "F2") (pinfunction "I$3_F2") (pintype "passive"))
      (node (ref "C11") (pin "S2") (pinfunction "E_S2") (pintype "open_collector"))
    )
    (net (code "404") (name "Net-(C10E-I$3)") (class "Default")
      (node (ref "C10") (pin "M2") (pinfunction "I$3_M2") (pintype "passive"))
      (node (ref "C11") (pin "M2") (pinfunction "E_M2") (pintype "open_collector"))
    )
    (net (code "405") (name "Net-(C11A-E)") (class "Default")
      (node (ref "C11") (pin "E2") (pinfunction "E_E2") (pintype "open_collector"))
      (node (ref "C12") (pin "T2") (pinfunction "I$3_T2") (pintype "passive"))
    )
    (net (code "406") (name "Net-(C11E-E)") (class "Default")
      (node (ref "C11") (pin "K2") (pinfunction "E_K2") (pintype "open_collector"))
      (node (ref "C12") (pin "M2") (pinfunction "I$3_M2") (pintype "passive"))
    )
    (net (code "407") (name "Net-(C11G-E)") (class "Default")
      (node (ref "C11") (pin "P2") (pinfunction "E_P2") (pintype "open_collector"))
      (node (ref "C12") (pin "F2") (pinfunction "I$3_F2") (pintype "passive"))
    )
    (net (code "408") (name "Net-(C21A-O$1)") (class "Default")
      (node (ref "C21") (pin "D2") (pinfunction "O$1_D2") (pintype "open_collector"))
      (node (ref "C22") (pin "E2") (pinfunction "IN_E2") (pintype "input"))
    )
    (net (code "409") (name "Net-(C21B-O$1)") (class "Default")
      (node (ref "C21") (pin "F2") (pinfunction "O$1_F2") (pintype "open_collector"))
      (node (ref "C22") (pin "H2") (pinfunction "IN_H2") (pintype "input"))
    )
    (net (code "410") (name "Net-(C21E-O$1)") (class "Default")
      (node (ref "C21") (pin "J2") (pinfunction "O$1_J2") (pintype "open_collector"))
      (node (ref "C22") (pin "K2") (pinfunction "IN_K2") (pintype "input"))
    )
    (net (code "411") (name "Net-(C21F-O$1)") (class "Default")
      (node (ref "C21") (pin "L2") (pinfunction "O$1_L2") (pintype "open_collector"))
      (node (ref "C22") (pin "M2") (pinfunction "IN_M2") (pintype "input"))
    )
    (net (code "412") (name "Net-(C21G-O$1)") (class "Default")
      (node (ref "C21") (pin "N2") (pinfunction "O$1_N2") (pintype "open_collector"))
      (node (ref "C22") (pin "P2") (pinfunction "IN_P2") (pintype "input"))
    )
    (net (code "413") (name "Net-(C21H-O$1)") (class "Default")
      (node (ref "C21") (pin "R2") (pinfunction "O$1_R2") (pintype "open_collector"))
      (node (ref "C22") (pin "S2") (pinfunction "IN_S2") (pintype "input"))
    )
    (net (code "414") (name "Net-(C24A-O$1)") (class "Default")
      (node (ref "C24") (pin "D2") (pinfunction "O$1_D2") (pintype "open_collector"))
      (node (ref "C25") (pin "E2") (pinfunction "IN_E2") (pintype "input"))
    )
    (net (code "415") (name "Net-(C24B-O$1)") (class "Default")
      (node (ref "C24") (pin "F2") (pinfunction "O$1_F2") (pintype "open_collector"))
      (node (ref "C25") (pin "H2") (pinfunction "IN_H2") (pintype "input"))
    )
    (net (code "416") (name "Net-(C24E-O$1)") (class "Default")
      (node (ref "C24") (pin "J2") (pinfunction "O$1_J2") (pintype "open_collector"))
      (node (ref "C25") (pin "K2") (pinfunction "IN_K2") (pintype "input"))
    )
    (net (code "417") (name "Net-(C24F-O$1)") (class "Default")
      (node (ref "C24") (pin "L2") (pinfunction "O$1_L2") (pintype "open_collector"))
      (node (ref "C25") (pin "M2") (pinfunction "IN_M2") (pintype "input"))
    )
    (net (code "418") (name "Net-(C24G-O$1)") (class "Default")
      (node (ref "C24") (pin "N2") (pinfunction "O$1_N2") (pintype "open_collector"))
      (node (ref "C25") (pin "P2") (pinfunction "IN_P2") (pintype "input"))
    )
    (net (code "419") (name "Net-(C24H-O$1)") (class "Default")
      (node (ref "C24") (pin "R2") (pinfunction "O$1_R2") (pintype "open_collector"))
      (node (ref "C25") (pin "S2") (pinfunction "IN_S2") (pintype "input"))
    )
    (net (code "420") (name "Net-(C24I-O$1)") (class "Default")
      (node (ref "C24") (pin "T2") (pinfunction "O$1_T2") (pintype "open_collector"))
      (node (ref "C27") (pin "E2") (pinfunction "IN_E2") (pintype "input"))
    )
    (net (code "421") (name "Net-(C39C-L)") (class "Default")
      (node (ref "C39") (pin "K2") (pinfunction "K_K2") (pintype "output"))
      (node (ref "C39") (pin "L2") (pinfunction "L_L2") (pintype "input"))
    )
    (net (code "422") (name "Net-(C39C-M)") (class "Default")
      (node (ref "C39") (pin "M2") (pinfunction "M_M2") (pintype "input"))
      (node (ref "C39") (pin "N2") (pinfunction "N_N2") (pintype "output"))
    )
    (net (code "423") (name "Net-(C39C-P)") (class "Default")
      (node (ref "C39") (pin "P2") (pinfunction "P_P2") (pintype "input"))
      (node (ref "C39") (pin "T2") (pinfunction "T_T2") (pintype "passive"))
    )
    (net (code "424") (name "Net-(C39C-R)") (class "Default")
      (node (ref "C39") (pin "R2") (pinfunction "R_R2") (pintype "input"))
      (node (ref "C39") (pin "U2") (pinfunction "P$1_U2") (pintype "passive"))
      (node (ref "F07") (pin "H2") (pinfunction "O$1_H2") (pintype "open_collector"))
      (node (ref "F07") (pin "J2") (pinfunction "P$1_J2") (pintype "passive"))
    )
    (net (code "425") (name "Net-(D06E-O$1)") (class "Default")
      (node (ref "D06") (pin "N2") (pinfunction "O$1_N2") (pintype "open_collector"))
      (node (ref "D07") (pin "V2") (pinfunction "O$1_V2") (pintype "open_collector"))
      (node (ref "E06") (pin "V2") (pinfunction "EN1_V2") (pintype "input"))
    )
    (net (code "426") (name "Net-(D09A-O)") (class "Default")
      (node (ref "D09") (pin "F2") (pinfunction "O_F2") (pintype "open_collector"))
      (node (ref "F03") (pin "N2") (pinfunction "PU0_N2") (pintype "input"))
    )
    (net (code "427") (name "Net-(D10E-PU0)") (class "Default")
      (node (ref "D10") (pin "R2") (pinfunction "PU0_R2") (pintype "input"))
      (node (ref "E05") (pin "E2") (pinfunction "P$1_E2") (pintype "passive"))
      (node (ref "E05") (pin "F2") (pinfunction "F_F2") (pintype "output"))
    )
    (net (code "428") (name "Net-(D11C-0)") (class "Default")
      (node (ref "D11") (pin "H2") (pinfunction "0_H2") (pintype "open_collector"))
      (node (ref "D11") (pin "V2") (pinfunction "EN1_V2") (pintype "input"))
      (node (ref "F08") (pin "V2") (pinfunction "P$1_V2") (pintype "passive"))
      (node (ref "F09") (pin "J2") (pinfunction "P$1_J2") (pintype "passive"))
      (node (ref "F12") (pin "S2") (pinfunction "I$1_S2") (pintype "input"))
    )
    (net (code "429") (name "Net-(D11C-1)") (class "Default")
      (node (ref "D11") (pin "J2") (pinfunction "1_J2") (pintype "open_collector"))
      (node (ref "D11") (pin "P2") (pinfunction "EN0_P2") (pintype "input"))
      (node (ref "F12") (pin "E2") (pinfunction "I$1_E2") (pintype "input"))
    )
    (net (code "430") (name "Net-(D11D-0)") (class "Default")
      (node (ref "D11") (pin "S2") (pinfunction "0_S2") (pintype "open_collector"))
      (node (ref "D12") (pin "L2") (pinfunction "EN1_L2") (pintype "input"))
      (node (ref "F12") (pin "U2") (pinfunction "I$1_U2") (pintype "input"))
    )
    (net (code "431") (name "Net-(D11D-1)") (class "Default")
      (node (ref "D11") (pin "T2") (pinfunction "1_T2") (pintype "open_collector"))
      (node (ref "D12") (pin "E2") (pinfunction "EN0_E2") (pintype "input"))
      (node (ref "F12") (pin "H2") (pinfunction "I$1_H2") (pintype "input"))
    )
    (net (code "432") (name "Net-(D12C-0)") (class "Default")
      (node (ref "D12") (pin "H2") (pinfunction "0_H2") (pintype "open_collector"))
      (node (ref "D12") (pin "V2") (pinfunction "EN1_V2") (pintype "input"))
      (node (ref "F11") (pin "E2") (pinfunction "I$1_E2") (pintype "input"))
    )
    (net (code "433") (name "Net-(D12C-1)") (class "Default")
      (node (ref "D12") (pin "J2") (pinfunction "1_J2") (pintype "open_collector"))
      (node (ref "D12") (pin "P2") (pinfunction "EN0_P2") (pintype "input"))
      (node (ref "F12") (pin "K2") (pinfunction "I$1_K2") (pintype "input"))
    )
    (net (code "434") (name "Net-(D12D-0)") (class "Default")
      (node (ref "D12") (pin "S2") (pinfunction "0_S2") (pintype "open_collector"))
      (node (ref "D13") (pin "L2") (pinfunction "EN1_L2") (pintype "input"))
      (node (ref "F11") (pin "H2") (pinfunction "I$1_H2") (pintype "input"))
    )
    (net (code "435") (name "Net-(D12D-1)") (class "Default")
      (node (ref "D12") (pin "T2") (pinfunction "1_T2") (pintype "open_collector"))
      (node (ref "D13") (pin "E2") (pinfunction "EN0_E2") (pintype "input"))
      (node (ref "D18") (pin "P2") (pinfunction "I$1_P2") (pintype "input"))
    )
    (net (code "436") (name "Net-(D13C-0)") (class "Default")
      (node (ref "D13") (pin "H2") (pinfunction "0_H2") (pintype "open_collector"))
      (node (ref "D13") (pin "V2") (pinfunction "EN1_V2") (pintype "input"))
      (node (ref "F11") (pin "K2") (pinfunction "I$1_K2") (pintype "input"))
    )
    (net (code "437") (name "Net-(D13C-1)") (class "Default")
      (node (ref "D13") (pin "J2") (pinfunction "1_J2") (pintype "open_collector"))
      (node (ref "D13") (pin "P2") (pinfunction "EN0_P2") (pintype "input"))
      (node (ref "D18") (pin "K2") (pinfunction "I$1_K2") (pintype "input"))
    )
    (net (code "438") (name "Net-(D13D-0)") (class "Default")
      (node (ref "D13") (pin "S2") (pinfunction "0_S2") (pintype "open_collector"))
      (node (ref "D14") (pin "L2") (pinfunction "EN1_L2") (pintype "input"))
      (node (ref "F11") (pin "M2") (pinfunction "I$1_M2") (pintype "input"))
    )
    (net (code "439") (name "Net-(D13D-1)") (class "Default")
      (node (ref "D13") (pin "T2") (pinfunction "1_T2") (pintype "open_collector"))
      (node (ref "D14") (pin "E2") (pinfunction "EN0_E2") (pintype "input"))
      (node (ref "D18") (pin "S2") (pinfunction "I$1_S2") (pintype "input"))
    )
    (net (code "440") (name "Net-(D14C-0)") (class "Default")
      (node (ref "D14") (pin "H2") (pinfunction "0_H2") (pintype "open_collector"))
      (node (ref "D14") (pin "V2") (pinfunction "EN1_V2") (pintype "input"))
      (node (ref "F18") (pin "E2") (pinfunction "I$1_E2") (pintype "input"))
    )
    (net (code "441") (name "Net-(D14C-1)") (class "Default")
      (node (ref "D14") (pin "J2") (pinfunction "1_J2") (pintype "open_collector"))
      (node (ref "D14") (pin "P2") (pinfunction "EN0_P2") (pintype "input"))
      (node (ref "D18") (pin "E2") (pinfunction "I$1_E2") (pintype "input"))
    )
    (net (code "442") (name "Net-(D14D-0)") (class "Default")
      (node (ref "D14") (pin "S2") (pinfunction "0_S2") (pintype "open_collector"))
      (node (ref "D15") (pin "L2") (pinfunction "EN1_L2") (pintype "input"))
      (node (ref "F11") (pin "P2") (pinfunction "I$1_P2") (pintype "input"))
    )
    (net (code "443") (name "Net-(D14D-1)") (class "Default")
      (node (ref "D14") (pin "T2") (pinfunction "1_T2") (pintype "open_collector"))
      (node (ref "D15") (pin "E2") (pinfunction "EN0_E2") (pintype "input"))
      (node (ref "D18") (pin "M2") (pinfunction "I$1_M2") (pintype "input"))
    )
    (net (code "444") (name "Net-(D15C-0)") (class "Default")
      (node (ref "D15") (pin "H2") (pinfunction "0_H2") (pintype "open_collector"))
      (node (ref "D15") (pin "V2") (pinfunction "EN1_V2") (pintype "input"))
      (node (ref "F11") (pin "S2") (pinfunction "I$1_S2") (pintype "input"))
    )
    (net (code "445") (name "Net-(D15C-1)") (class "Default")
      (node (ref "D15") (pin "J2") (pinfunction "1_J2") (pintype "open_collector"))
      (node (ref "D15") (pin "P2") (pinfunction "EN0_P2") (pintype "input"))
      (node (ref "D18") (pin "U2") (pinfunction "I$1_U2") (pintype "input"))
    )
    (net (code "446") (name "Net-(D15D-0)") (class "Default")
      (node (ref "D15") (pin "S2") (pinfunction "0_S2") (pintype "open_collector"))
      (node (ref "D16") (pin "L2") (pinfunction "EN1_L2") (pintype "input"))
      (node (ref "F11") (pin "U2") (pinfunction "I$1_U2") (pintype "input"))
    )
    (net (code "447") (name "Net-(D15D-1)") (class "Default")
      (node (ref "D15") (pin "T2") (pinfunction "1_T2") (pintype "open_collector"))
      (node (ref "D16") (pin "E2") (pinfunction "EN0_E2") (pintype "input"))
      (node (ref "F12") (pin "M2") (pinfunction "I$1_M2") (pintype "input"))
    )
    (net (code "448") (name "Net-(D16C-0)") (class "Default")
      (node (ref "D16") (pin "H2") (pinfunction "0_H2") (pintype "open_collector"))
      (node (ref "D16") (pin "V2") (pinfunction "EN1_V2") (pintype "input"))
      (node (ref "F13") (pin "M2") (pinfunction "I$1_M2") (pintype "input"))
    )
    (net (code "449") (name "Net-(D16C-1)") (class "Default")
      (node (ref "D16") (pin "J2") (pinfunction "1_J2") (pintype "open_collector"))
      (node (ref "D16") (pin "P2") (pinfunction "EN0_P2") (pintype "input"))
      (node (ref "F12") (pin "P2") (pinfunction "I$1_P2") (pintype "input"))
    )
    (net (code "450") (name "Net-(D16D-0)") (class "Default")
      (node (ref "D16") (pin "S2") (pinfunction "0_S2") (pintype "open_collector"))
      (node (ref "F13") (pin "H2") (pinfunction "I$1_H2") (pintype "input"))
    )
    (net (code "451") (name "Net-(E03H-E)") (class "Default")
      (node (ref "E03") (pin "S2") (pinfunction "E_S2") (pintype "open_collector"))
      (node (ref "F05") (pin "J2") (pinfunction "1_J2") (pintype "open_collector"))
      (node (ref "F05") (pin "P2") (pinfunction "EN0_P2") (pintype "input"))
    )
    (net (code "452") (name "Net-(E05C-L)") (class "Default")
      (node (ref "E05") (pin "K2") (pinfunction "K_K2") (pintype "output"))
      (node (ref "E05") (pin "L2") (pinfunction "L_L2") (pintype "input"))
    )
    (net (code "453") (name "Net-(E05C-M)") (class "Default")
      (node (ref "E05") (pin "M2") (pinfunction "M_M2") (pintype "input"))
      (node (ref "E05") (pin "N2") (pinfunction "N_N2") (pintype "output"))
    )
    (net (code "454") (name "Net-(E07D-O$1)") (class "Default")
      (node (ref "E07") (pin "J2") (pinfunction "O$1_J2") (pintype "output"))
      (node (ref "F02") (pin "R2") (pinfunction "P$2_R2") (pintype "bidirectional"))
    )
    (net (code "455") (name "Net-(E07E-O$1)") (class "Default")
      (node (ref "E07") (pin "L2") (pinfunction "O$1_L2") (pintype "output"))
      (node (ref "F02") (pin "T2") (pinfunction "P$2_T2") (pintype "bidirectional"))
    )
    (net (code "456") (name "Net-(E09A-O$1)") (class "Default")
      (node (ref "E09") (pin "F2") (pinfunction "O$1_F2") (pintype "open_collector"))
      (node (ref "F16") (pin "D2") (pinfunction "D_D2") (pintype "input"))
    )
    (net (code "457") (name "Net-(E09D-O$1)") (class "Default")
      (node (ref "E09") (pin "K2") (pinfunction "O$1_K2") (pintype "open_collector"))
      (node (ref "F16") (pin "F2") (pinfunction "D_F2") (pintype "input"))
    )
    (net (code "458") (name "Net-(E09E-O$1)") (class "Default")
      (node (ref "E09") (pin "N2") (pinfunction "O$1_N2") (pintype "open_collector"))
      (node (ref "F18") (pin "U2") (pinfunction "I$1_U2") (pintype "input"))
    )
    (net (code "459") (name "Net-(E09F-O$1)") (class "Default")
      (node (ref "E09") (pin "S2") (pinfunction "O$1_S2") (pintype "open_collector"))
      (node (ref "F13") (pin "P2") (pinfunction "I$1_P2") (pintype "input"))
    )
    (net (code "460") (name "Net-(E09G-O$1)") (class "Default")
      (node (ref "E09") (pin "V2") (pinfunction "O$1_V2") (pintype "open_collector"))
      (node (ref "F13") (pin "K2") (pinfunction "I$1_K2") (pintype "input"))
    )
    (net (code "461") (name "Net-(E10E-I$1)") (class "Default")
      (node (ref "E10") (pin "L2") (pinfunction "I$1_L2") (pintype "input"))
      (node (ref "F19") (pin "L2") (pinfunction "O$1_L2") (pintype "open_collector"))
    )
    (net (code "462") (name "Net-(E10E-O$1)") (class "Default")
      (node (ref "E10") (pin "N2") (pinfunction "O$1_N2") (pintype "open_collector"))
      (node (ref "F19") (pin "H2") (pinfunction "I$1_H2") (pintype "input"))
    )
    (net (code "463") (name "Net-(E11E-O$1)") (class "Default")
      (node (ref "E11") (pin "N2") (pinfunction "O$1_N2") (pintype "open_collector"))
      (node (ref "F15") (pin "K2") (pinfunction "I$1_K2") (pintype "input"))
    )
    (net (code "464") (name "Net-(E12C-EN1)") (class "Default")
      (node (ref "E12") (pin "L2") (pinfunction "EN1_L2") (pintype "input"))
      (node (ref "E13") (pin "N2") (pinfunction "O$1_N2") (pintype "open_collector"))
    )
    (net (code "465") (name "Net-(E15C-1)") (class "Default")
      (node (ref "E15") (pin "J2") (pinfunction "1_J2") (pintype "open_collector"))
      (node (ref "E15") (pin "P2") (pinfunction "EN0_P2") (pintype "input"))
    )
    (net (code "466") (name "Net-(E15D-1)") (class "Default")
      (node (ref "E15") (pin "T2") (pinfunction "1_T2") (pintype "open_collector"))
      (node (ref "E16") (pin "E2") (pinfunction "EN0_E2") (pintype "input"))
    )
    (net (code "467") (name "Net-(E16C-1)") (class "Default")
      (node (ref "E16") (pin "J2") (pinfunction "1_J2") (pintype "open_collector"))
      (node (ref "E16") (pin "P2") (pinfunction "EN0_P2") (pintype "input"))
    )
    (net (code "468") (name "Net-(E16D-1)") (class "Default")
      (node (ref "E16") (pin "T2") (pinfunction "1_T2") (pintype "open_collector"))
      (node (ref "E17") (pin "E2") (pinfunction "EN0_E2") (pintype "input"))
    )
    (net (code "469") (name "Net-(E17C-1)") (class "Default")
      (node (ref "E17") (pin "J2") (pinfunction "1_J2") (pintype "open_collector"))
      (node (ref "E17") (pin "P2") (pinfunction "EN0_P2") (pintype "input"))
    )
    (net (code "470") (name "Net-(E17D-1)") (class "Default")
      (node (ref "E17") (pin "T2") (pinfunction "1_T2") (pintype "open_collector"))
      (node (ref "E18") (pin "E2") (pinfunction "EN0_E2") (pintype "input"))
    )
    (net (code "471") (name "Net-(E18C-1)") (class "Default")
      (node (ref "E18") (pin "J2") (pinfunction "1_J2") (pintype "open_collector"))
      (node (ref "E18") (pin "P2") (pinfunction "EN0_P2") (pintype "input"))
    )
    (net (code "472") (name "Net-(E18D-1)") (class "Default")
      (node (ref "E18") (pin "T2") (pinfunction "1_T2") (pintype "open_collector"))
      (node (ref "E19") (pin "E2") (pinfunction "EN0_E2") (pintype "input"))
    )
    (net (code "473") (name "Net-(E19C-1)") (class "Default")
      (node (ref "E19") (pin "J2") (pinfunction "1_J2") (pintype "open_collector"))
      (node (ref "E19") (pin "P2") (pinfunction "EN0_P2") (pintype "input"))
    )
    (net (code "474") (name "Net-(E19D-1)") (class "Default")
      (node (ref "E19") (pin "T2") (pinfunction "1_T2") (pintype "open_collector"))
      (node (ref "E20") (pin "E2") (pinfunction "EN0_E2") (pintype "input"))
    )
    (net (code "475") (name "Net-(E20C-1)") (class "Default")
      (node (ref "E20") (pin "J2") (pinfunction "1_J2") (pintype "open_collector"))
      (node (ref "E20") (pin "P2") (pinfunction "EN0_P2") (pintype "input"))
    )
    (net (code "476") (name "Net-(F05C-0)") (class "Default")
      (node (ref "F05") (pin "H2") (pinfunction "0_H2") (pintype "open_collector"))
      (node (ref "F05") (pin "V2") (pinfunction "EN1_V2") (pintype "input"))
    )
    (net (code "477") (name "Net-(F06F-E)") (class "Default")
      (node (ref "F06") (pin "M2") (pinfunction "E_M2") (pintype "open_collector"))
      (node (ref "F08") (pin "M2") (pinfunction "I$3_M2") (pintype "passive"))
    )
    (net (code "478") (name "Net-(F07C-I$3)") (class "Default")
      (node (ref "F07") (pin "F2") (pinfunction "I$3_F2") (pintype "passive"))
      (node (ref "F16") (pin "K2") (pinfunction "E_K2") (pintype "open_collector"))
    )
    (net (code "479") (name "Net-(F07G-I$1)") (class "Default")
      (node (ref "F07") (pin "R2") (pinfunction "I$1_R2") (pintype "input"))
      (node (ref "F18") (pin "F2") (pinfunction "O$1_F2") (pintype "open_collector"))
    )
    (net (code "480") (name "Net-(F15E-I$3)") (class "Default")
      (node (ref "F15") (pin "M2") (pinfunction "I$3_M2") (pintype "passive"))
      (node (ref "F16") (pin "P2") (pinfunction "E_P2") (pintype "open_collector"))
    )
    (net (code "481") (name "Net-(F15G-I$3)") (class "Default")
      (node (ref "F15") (pin "T2") (pinfunction "I$3_T2") (pintype "passive"))
      (node (ref "F16") (pin "S2") (pinfunction "E_S2") (pintype "open_collector"))
      (node (ref "F16") (pin "U2") (pinfunction "E_U2") (pintype "open_collector"))
    )
    (net (code "482") (name "Net-(F16A-E)") (class "Default")
      (node (ref "F16") (pin "E2") (pinfunction "E_E2") (pintype "open_collector"))
      (node (ref "F17") (pin "F2") (pinfunction "I$3_F2") (pintype "passive"))
    )
    (net (code "483") (name "Net-(F16D-E)") (class "Default")
      (node (ref "F16") (pin "H2") (pinfunction "E_H2") (pintype "open_collector"))
      (node (ref "F17") (pin "M2") (pinfunction "I$3_M2") (pintype "passive"))
    )
    (net (code "484") (name "Net-(F16F-E)") (class "Default")
      (node (ref "F16") (pin "M2") (pinfunction "E_M2") (pintype "open_collector"))
      (node (ref "F17") (pin "T2") (pinfunction "I$3_T2") (pintype "passive"))
    )
    (net (code "485") (name "Net-(F37D-K)") (class "Default")
      (node (ref "F37") (pin "U2") (pinfunction "K_U2") (pintype "open_collector"))
      (node (ref "F38") (pin "S2") (pinfunction "H_S2") (pintype "input"))
      (node (ref "F39") (pin "S2") (pinfunction "H_S2") (pintype "input"))
    )
    (net (code "486") (name "OP+IOT") (class "Default")
      (node (ref "E11") (pin "K2") (pinfunction "O$1_K2") (pintype "open_collector"))
      (node (ref "F13") (pin "S2") (pinfunction "I$1_S2") (pintype "input"))
    )
    (net (code "487") (name "OP1") (class "Default")
      (node (ref "B26") (pin "E2") (pinfunction "E_E2") (pintype "input"))
      (node (ref "B26") (pin "P2") (pinfunction "D_P2") (pintype "input"))
      (node (ref "C11") (pin "D2") (pinfunction "D_D2") (pintype "input"))
      (node (ref "E13") (pin "R2") (pinfunction "I$2_R2") (pintype "input"))
      (node (ref "E13") (pin "U2") (pinfunction "I$2_U2") (pintype "input"))
      (node (ref "F14") (pin "D2") (pinfunction "I$1_D2") (pintype "input"))
      (node (ref "F14") (pin "H2") (pinfunction "I$1_H2") (pintype "input"))
      (node (ref "F17") (pin "D2") (pinfunction "I$1_D2") (pintype "input"))
      (node (ref "F17") (pin "K2") (pinfunction "I$1_K2") (pintype "input"))
      (node (ref "F18") (pin "J2") (pinfunction "O$1_J2") (pintype "open_collector"))
    )
    (net (code "488") (name "OP2") (class "Default")
      (node (ref "A34") (pin "E2") (pinfunction "I$2_E2") (pintype "input"))
      (node (ref "A35") (pin "F2") (pinfunction "D_F2") (pintype "input"))
      (node (ref "B15") (pin "T2") (pinfunction "I$1_T2") (pintype "input"))
      (node (ref "B23") (pin "S2") (pinfunction "I$2_S2") (pintype "input"))
      (node (ref "F18") (pin "N2") (pinfunction "O$1_N2") (pintype "open_collector"))
    )
    (net (code "489") (name "OPR") (class "Default")
      (node (ref "A07") (pin "H2") (pinfunction "I$1_H2") (pintype "input"))
      (node (ref "E10") (pin "D2") (pinfunction "I$1_D2") (pintype "input"))
      (node (ref "E11") (pin "E2") (pinfunction "I$2_E2") (pintype "input"))
      (node (ref "F19") (pin "J2") (pinfunction "O$1_J2") (pintype "open_collector"))
    )
    (net (code "490") (name "PB") (class "Default")
      (node (ref "D06") (pin "M2") (pinfunction "I$2_M2") (pintype "input"))
      (node (ref "E07") (pin "K2") (pinfunction "I$1_K2") (pintype "input"))
      (node (ref "F05") (pin "T2") (pinfunction "1_T2") (pintype "open_collector"))
      (node (ref "F06") (pin "H2") (pinfunction "E_H2") (pintype "open_collector"))
      (node (ref "F06") (pin "P2") (pinfunction "E_P2") (pintype "open_collector"))
      (node (ref "F10") (pin "H2") (pinfunction "I$1_H2") (pintype "input"))
      (node (ref "F36") (pin "U2") (pinfunction "I$2_U2") (pintype "input"))
    )
    (net (code "491") (name "PC11") (class "Default")
      (node (ref "A27") (pin "H2") (pinfunction "I$1_H2") (pintype "input"))
      (node (ref "B25") (pin "D2") (pinfunction "I$1_D2") (pintype "input"))
      (node (ref "D08") (pin "D2") (pinfunction "I$1_D2") (pintype "input"))
      (node (ref "D08") (pin "T2") (pinfunction "I$1_T2") (pintype "input"))
      (node (ref "E13") (pin "H2") (pinfunction "I$1_H2") (pintype "input"))
      (node (ref "E14") (pin "L2") (pinfunction "I$1_L2") (pintype "input"))
    )
    (net (code "492") (name "PE") (class "Default")
      (node (ref "E06") (pin "T2") (pinfunction "1_T2") (pintype "open_collector"))
      (node (ref "E07") (pin "H2") (pinfunction "I$1_H2") (pintype "input"))
    )
    (net (code "493") (name "PGZ") (class "Default")
      (node (ref "E12") (pin "J2") (pinfunction "1_J2") (pintype "open_collector"))
    )
    (net (code "494") (name "PIR") (class "Default")
      (node (ref "A10") (pin "T2") (pinfunction "I$1_T2") (pintype "input"))
    )
    (net (code "495") (name "PT") (class "Default")
      (node (ref "D07") (pin "T2") (pinfunction "I$1_T2") (pintype "input"))
      (node (ref "E06") (pin "J2") (pinfunction "1_J2") (pintype "open_collector"))
    )
    (net (code "496") (name "RAMD00") (class "Default")
      (node (ref "C22") (pin "D2") (pinfunction "OUT_D2") (pintype "output"))
      (node (ref "C23") (pin "E2") (pinfunction "IN_E2") (pintype "input"))
      (node (ref "C28") (pin "D2") (pinfunction "P$2_D2") (pintype "bidirectional"))
    )
    (net (code "497") (name "RAMD01") (class "Default")
      (node (ref "C22") (pin "F2") (pinfunction "OUT_F2") (pintype "output"))
      (node (ref "C23") (pin "H2") (pinfunction "IN_H2") (pintype "input"))
      (node (ref "C28") (pin "E2") (pinfunction "P$2_E2") (pintype "bidirectional"))
    )
    (net (code "498") (name "RAMD02") (class "Default")
      (node (ref "C22") (pin "J2") (pinfunction "OUT_J2") (pintype "output"))
      (node (ref "C23") (pin "K2") (pinfunction "IN_K2") (pintype "input"))
      (node (ref "C28") (pin "F2") (pinfunction "P$2_F2") (pintype "bidirectional"))
    )
    (net (code "499") (name "RAMD03") (class "Default")
      (node (ref "C22") (pin "L2") (pinfunction "OUT_L2") (pintype "output"))
      (node (ref "C23") (pin "M2") (pinfunction "IN_M2") (pintype "input"))
      (node (ref "C28") (pin "H2") (pinfunction "P$2_H2") (pintype "bidirectional"))
    )
    (net (code "500") (name "RAMD04") (class "Default")
      (node (ref "C22") (pin "N2") (pinfunction "OUT_N2") (pintype "output"))
      (node (ref "C23") (pin "P2") (pinfunction "IN_P2") (pintype "input"))
      (node (ref "C28") (pin "J2") (pinfunction "P$2_J2") (pintype "bidirectional"))
    )
    (net (code "501") (name "RAMD05") (class "Default")
      (node (ref "C22") (pin "R2") (pinfunction "OUT_R2") (pintype "output"))
      (node (ref "C23") (pin "S2") (pinfunction "IN_S2") (pintype "input"))
      (node (ref "C28") (pin "K2") (pinfunction "P$2_K2") (pintype "bidirectional"))
    )
    (net (code "502") (name "RAMD06") (class "Default")
      (node (ref "C25") (pin "D2") (pinfunction "OUT_D2") (pintype "output"))
      (node (ref "C26") (pin "E2") (pinfunction "IN_E2") (pintype "input"))
      (node (ref "C28") (pin "L2") (pinfunction "P$2_L2") (pintype "bidirectional"))
    )
    (net (code "503") (name "RAMD07") (class "Default")
      (node (ref "C25") (pin "F2") (pinfunction "OUT_F2") (pintype "output"))
      (node (ref "C26") (pin "H2") (pinfunction "IN_H2") (pintype "input"))
      (node (ref "C28") (pin "M2") (pinfunction "P$2_M2") (pintype "bidirectional"))
    )
    (net (code "504") (name "RAMD08") (class "Default")
      (node (ref "C25") (pin "J2") (pinfunction "OUT_J2") (pintype "output"))
      (node (ref "C26") (pin "K2") (pinfunction "IN_K2") (pintype "input"))
      (node (ref "C28") (pin "N2") (pinfunction "P$2_N2") (pintype "bidirectional"))
    )
    (net (code "505") (name "RAMD09") (class "Default")
      (node (ref "C25") (pin "L2") (pinfunction "OUT_L2") (pintype "output"))
      (node (ref "C26") (pin "M2") (pinfunction "IN_M2") (pintype "input"))
      (node (ref "C28") (pin "P2") (pinfunction "P$2_P2") (pintype "bidirectional"))
    )
    (net (code "506") (name "RAMD10") (class "Default")
      (node (ref "C25") (pin "N2") (pinfunction "OUT_N2") (pintype "output"))
      (node (ref "C26") (pin "P2") (pinfunction "IN_P2") (pintype "input"))
      (node (ref "C28") (pin "R2") (pinfunction "P$2_R2") (pintype "bidirectional"))
    )
    (net (code "507") (name "RAMD11") (class "Default")
      (node (ref "C25") (pin "R2") (pinfunction "OUT_R2") (pintype "output"))
      (node (ref "C26") (pin "S2") (pinfunction "IN_S2") (pintype "input"))
      (node (ref "C28") (pin "S2") (pinfunction "P$2_S2") (pintype "bidirectional"))
    )
    (net (code "508") (name "RAMD12") (class "Default")
      (node (ref "C26") (pin "U2") (pinfunction "IN_U2") (pintype "input"))
      (node (ref "C27") (pin "D2") (pinfunction "OUT_D2") (pintype "output"))
      (node (ref "C28") (pin "T2") (pinfunction "P$2_T2") (pintype "bidirectional"))
    )
    (net (code "509") (name "RIMA") (class "Default")
      (node (ref "A18") (pin "L2") (pinfunction "O$1_L2") (pintype "open_collector"))
      (node (ref "E15") (pin "L2") (pinfunction "EN1_L2") (pintype "input"))
    )
    (net (code "510") (name "ROTR") (class "Default")
      (node (ref "A26") (pin "U2") (pinfunction "I$2_U2") (pintype "input"))
      (node (ref "F19") (pin "R2") (pinfunction "O$1_R2") (pintype "open_collector"))
    )
    (net (code "511") (name "ROTR+ROTL+TAD") (class "Default")
      (node (ref "A21") (pin "S2") (pinfunction "I$2_S2") (pintype "input"))
      (node (ref "F17") (pin "U2") (pinfunction "O$1_U2") (pintype "open_collector"))
      (node (ref "F17") (pin "V2") (pinfunction "P$1_V2") (pintype "passive"))
    )
    (net (code "512") (name "RUN") (class "Default")
      (node (ref "A05") (pin "E2") (pinfunction "I$1_E2") (pintype "input"))
      (node (ref "A35") (pin "M2") (pinfunction "E_M2") (pintype "open_collector"))
      (node (ref "B14") (pin "N2") (pinfunction "F_N2") (pintype "open_collector"))
      (node (ref "B34") (pin "T2") (pinfunction "1_T2") (pintype "open_collector"))
    )
    (net (code "513") (name "S") (class "Default")
      (node (ref "A17") (pin "J2") (pinfunction "O$1_J2") (pintype "open_collector"))
      (node (ref "B40") (pin "D2") (pinfunction "P$1_D2") (pintype "passive"))
      (node (ref "B40") (pin "H2") (pinfunction "P$1_H2") (pintype "passive"))
      (node (ref "D07") (pin "D2") (pinfunction "I$1_D2") (pintype "input"))
      (node (ref "D08") (pin "H2") (pinfunction "I$1_H2") (pintype "input"))
      (node (ref "E14") (pin "P2") (pinfunction "I$1_P2") (pintype "input"))
    )
    (net (code "514") (name "SDF0") (class "Default")
      (node (ref "F01") (pin "E2") (pinfunction "P$2_E2") (pintype "bidirectional"))
    )
    (net (code "515") (name "SDF1") (class "Default")
      (node (ref "F01") (pin "H2") (pinfunction "P$2_H2") (pintype "bidirectional"))
    )
    (net (code "516") (name "SDF2") (class "Default")
      (node (ref "F01") (pin "L2") (pinfunction "P$2_L2") (pintype "bidirectional"))
    )
    (net (code "517") (name "SIF0") (class "Default")
      (node (ref "E01") (pin "L2") (pinfunction "P$2_L2") (pintype "bidirectional"))
    )
    (net (code "518") (name "SIF1") (class "Default")
      (node (ref "E01") (pin "R2") (pinfunction "P$2_R2") (pintype "bidirectional"))
    )
    (net (code "519") (name "SIF2") (class "Default")
      (node (ref "E01") (pin "U2") (pinfunction "P$2_U2") (pintype "bidirectional"))
    )
    (net (code "520") (name "SKP") (class "Default")
      (node (ref "E11") (pin "L2") (pinfunction "I$1_L2") (pintype "input"))
      (node (ref "F03") (pin "S2") (pinfunction "0_S2") (pintype "open_collector"))
    )
    (net (code "521") (name "SX") (class "Default")
      (node (ref "A23") (pin "D2") (pinfunction "I$1_D2") (pintype "input"))
      (node (ref "A23") (pin "K2") (pinfunction "I$1_K2") (pintype "input"))
      (node (ref "A24") (pin "F2") (pinfunction "O$1_F2") (pintype "open_collector"))
      (node (ref "B24") (pin "D2") (pinfunction "I$1_D2") (pintype "input"))
      (node (ref "B25") (pin "T2") (pinfunction "I$1_T2") (pintype "input"))
      (node (ref "B40") (pin "V2") (pinfunction "P$1_V2") (pintype "passive"))
    )
    (net (code "522") (name "SY") (class "Default")
      (node (ref "A23") (pin "L2") (pinfunction "I$2_L2") (pintype "input"))
      (node (ref "A23") (pin "S2") (pinfunction "I$2_S2") (pintype "input"))
      (node (ref "A24") (pin "T2") (pinfunction "O$1_T2") (pintype "open_collector"))
      (node (ref "B24") (pin "H2") (pinfunction "I$1_H2") (pintype "input"))
      (node (ref "B25") (pin "U2") (pinfunction "I$2_U2") (pintype "input"))
    )
    (net (code "523") (name "T0") (class "Default")
      (node (ref "A29") (pin "J2") (pinfunction "1_J2") (pintype "open_collector"))
      (node (ref "A30") (pin "P2") (pinfunction "EN0_P2") (pintype "input"))
      (node (ref "A33") (pin "E2") (pinfunction "E_E2") (pintype "open_collector"))
    )
    (net (code "524") (name "T1") (class "Default")
      (node (ref "A30") (pin "E2") (pinfunction "EN0_E2") (pintype "input"))
      (node (ref "A30") (pin "T2") (pinfunction "1_T2") (pintype "open_collector"))
      (node (ref "A33") (pin "H2") (pinfunction "E_H2") (pintype "open_collector"))
    )
    (net (code "525") (name "T2") (class "Default")
      (node (ref "A30") (pin "J2") (pinfunction "1_J2") (pintype "open_collector"))
      (node (ref "A31") (pin "P2") (pinfunction "EN0_P2") (pintype "input"))
      (node (ref "A33") (pin "K2") (pinfunction "E_K2") (pintype "open_collector"))
    )
    (net (code "526") (name "T3") (class "Default")
      (node (ref "A31") (pin "E2") (pinfunction "EN0_E2") (pintype "input"))
      (node (ref "A31") (pin "T2") (pinfunction "1_T2") (pintype "open_collector"))
      (node (ref "A33") (pin "M2") (pinfunction "E_M2") (pintype "open_collector"))
    )
    (net (code "527") (name "T4") (class "Default")
      (node (ref "A31") (pin "J2") (pinfunction "1_J2") (pintype "open_collector"))
      (node (ref "A32") (pin "P2") (pinfunction "EN0_P2") (pintype "input"))
      (node (ref "A33") (pin "P2") (pinfunction "E_P2") (pintype "open_collector"))
      (node (ref "C14") (pin "T2") (pinfunction "I$1_T2") (pintype "input"))
    )
    (net (code "528") (name "T5") (class "Default")
      (node (ref "A26") (pin "R2") (pinfunction "I$2_R2") (pintype "input"))
      (node (ref "A32") (pin "E2") (pinfunction "EN0_E2") (pintype "input"))
      (node (ref "A32") (pin "T2") (pinfunction "1_T2") (pintype "open_collector"))
      (node (ref "A33") (pin "S2") (pinfunction "E_S2") (pintype "open_collector"))
    )
    (net (code "529") (name "T6") (class "Default")
      (node (ref "A24") (pin "M2") (pinfunction "I$1_M2") (pintype "input"))
      (node (ref "A26") (pin "M2") (pinfunction "I$2_M2") (pintype "input"))
      (node (ref "A27") (pin "E2") (pinfunction "I$2_E2") (pintype "input"))
      (node (ref "A29") (pin "L2") (pinfunction "EN1_L2") (pintype "input"))
      (node (ref "A32") (pin "J2") (pinfunction "1_J2") (pintype "open_collector"))
      (node (ref "A33") (pin "U2") (pinfunction "E_U2") (pintype "open_collector"))
      (node (ref "C14") (pin "U2") (pinfunction "I$2_U2") (pintype "input"))
    )
    (net (code "530") (name "TAD") (class "Default")
      (node (ref "A06") (pin "K2") (pinfunction "I$1_K2") (pintype "input"))
      (node (ref "A15") (pin "U2") (pinfunction "I$2_U2") (pintype "input"))
      (node (ref "F20") (pin "F2") (pinfunction "O$1_F2") (pintype "open_collector"))
    )
    (net (code "531") (name "TAD+IAC+CMA") (class "Default")
      (node (ref "E10") (pin "S2") (pinfunction "O$1_S2") (pintype "open_collector"))
      (node (ref "E10") (pin "T2") (pinfunction "I$1_T2") (pintype "input"))
    )
    (net (code "532") (name "VCC") (class "Default")
      (node (ref "C28") (pin "A2") (pinfunction "P$2_A2") (pintype "bidirectional"))
      (node (ref "D28") (pin "A2") (pinfunction "P$2_A2") (pintype "bidirectional"))
    )
    (net (code "533") (name "WTB") (class "Default")
      (node (ref "A05") (pin "K2") (pinfunction "I$1_K2") (pintype "input"))
      (node (ref "A09") (pin "U2") (pinfunction "I$1_U2") (pintype "input"))
      (node (ref "C13") (pin "N2") (pinfunction "O$1_N2") (pintype "open_collector"))
      (node (ref "D08") (pin "U2") (pinfunction "I$2_U2") (pintype "input"))
    )
    (net (code "534") (name "WTD") (class "Default")
      (node (ref "A05") (pin "S2") (pinfunction "I$1_S2") (pintype "input"))
      (node (ref "A08") (pin "M2") (pinfunction "I$2_M2") (pintype "input"))
      (node (ref "A09") (pin "H2") (pinfunction "I$1_H2") (pintype "input"))
      (node (ref "B17") (pin "J2") (pinfunction "I$2_J2") (pintype "input"))
      (node (ref "C13") (pin "D2") (pinfunction "O$1_D2") (pintype "open_collector"))
      (node (ref "E14") (pin "H2") (pinfunction "I$1_H2") (pintype "input"))
    )
    (net (code "535") (name "WTE") (class "Default")
      (node (ref "A05") (pin "M2") (pinfunction "I$1_M2") (pintype "input"))
      (node (ref "A10") (pin "R2") (pinfunction "I$2_R2") (pintype "input"))
      (node (ref "A10") (pin "U2") (pinfunction "I$2_U2") (pintype "input"))
      (node (ref "A15") (pin "R2") (pinfunction "I$2_R2") (pintype "input"))
      (node (ref "A34") (pin "L2") (pinfunction "I$2_L2") (pintype "input"))
      (node (ref "B08") (pin "D2") (pinfunction "O$1_D2") (pintype "open_collector"))
      (node (ref "B15") (pin "P2") (pinfunction "I$1_P2") (pintype "input"))
      (node (ref "B26") (pin "T2") (pinfunction "D_T2") (pintype "input"))
      (node (ref "D07") (pin "P2") (pinfunction "I$1_P2") (pintype "input"))
    )
    (net (code "536") (name "WTE*-[(ISZ*ZI)+JMS+(OP+IOT)*SKP+JMP]") (class "Default")
      (node (ref "B08") (pin "T2") (pinfunction "O$1_T2") (pintype "open_collector"))
      (node (ref "E14") (pin "M2") (pinfunction "I$2_M2") (pintype "input"))
    )
    (net (code "537") (name "WTE*[(ISZ*ZI)+JMS+(OP+IOT)*SKP]") (class "Default")
      (node (ref "A18") (pin "R2") (pinfunction "O$1_R2") (pintype "open_collector"))
      (node (ref "E14") (pin "R2") (pinfunction "I$2_R2") (pintype "input"))
    )
    (net (code "538") (name "WTF") (class "Default")
      (node (ref "A06") (pin "E2") (pinfunction "I$1_E2") (pintype "input"))
      (node (ref "A08") (pin "H2") (pinfunction "I$1_H2") (pintype "input"))
      (node (ref "A15") (pin "J2") (pinfunction "I$2_J2") (pintype "input"))
      (node (ref "A22") (pin "T2") (pinfunction "D_T2") (pintype "input"))
      (node (ref "B15") (pin "L2") (pinfunction "I$1_L2") (pintype "input"))
      (node (ref "B17") (pin "P2") (pinfunction "I$1_P2") (pintype "input"))
      (node (ref "B26") (pin "J2") (pinfunction "E_J2") (pintype "input"))
      (node (ref "B36") (pin "J2") (pinfunction "I$2_J2") (pintype "input"))
      (node (ref "B36") (pin "M2") (pinfunction "I$2_M2") (pintype "input"))
      (node (ref "C08") (pin "J2") (pinfunction "E_J2") (pintype "input"))
      (node (ref "C09") (pin "R2") (pinfunction "O$1_R2") (pintype "open_collector"))
      (node (ref "C10") (pin "L2") (pinfunction "I$2_L2") (pintype "input"))
      (node (ref "C12") (pin "K2") (pinfunction "I$1_K2") (pintype "input"))
      (node (ref "D08") (pin "M2") (pinfunction "I$2_M2") (pintype "input"))
      (node (ref "E13") (pin "L2") (pinfunction "I$1_L2") (pintype "input"))
      (node (ref "F06") (pin "L2") (pinfunction "D_L2") (pintype "input"))
    )
    (net (code "539") (name "WTF*-(OP+IOT)") (class "Default")
      (node (ref "A08") (pin "D2") (pinfunction "I$1_D2") (pintype "input"))
      (node (ref "B08") (pin "L2") (pinfunction "O$1_L2") (pintype "open_collector"))
      (node (ref "B17") (pin "M2") (pinfunction "I$2_M2") (pintype "input"))
      (node (ref "B17") (pin "T2") (pinfunction "I$1_T2") (pintype "input"))
    )
    (net (code "540") (name "WTF*BT(00-06)") (class "Default")
      (node (ref "A09") (pin "L2") (pinfunction "O$1_L2") (pintype "open_collector"))
      (node (ref "E14") (pin "E2") (pinfunction "I$2_E2") (pintype "input"))
    )
    (net (code "541") (name "WTF*BT(07-11)*-PGZ") (class "Default")
      (node (ref "C09") (pin "J2") (pinfunction "O$1_J2") (pintype "open_collector"))
      (node (ref "E14") (pin "U2") (pinfunction "I$2_U2") (pintype "input"))
    )
    (net (code "542") (name "WTF+WTB+EX+DC+LD") (class "Default")
      (node (ref "B13") (pin "U2") (pinfunction "O$1_U2") (pintype "open_collector"))
      (node (ref "B13") (pin "V2") (pinfunction "P$1_V2") (pintype "passive"))
    )
    (net (code "543") (name "WTF+WTI+WTD+WTB") (class "Default")
      (node (ref "A14") (pin "N2") (pinfunction "O$1_N2") (pintype "open_collector"))
      (node (ref "A14") (pin "P2") (pinfunction "P$1_P2") (pintype "passive"))
      (node (ref "B16") (pin "K2") (pinfunction "I$1_K2") (pintype "input"))
      (node (ref "B16") (pin "U2") (pinfunction "I$1_U2") (pintype "input"))
    )
    (net (code "544") (name "WTI") (class "Default")
      (node (ref "A05") (pin "U2") (pinfunction "I$1_U2") (pintype "input"))
      (node (ref "B08") (pin "H2") (pinfunction "I$1_H2") (pintype "input"))
      (node (ref "C09") (pin "F2") (pinfunction "O$1_F2") (pintype "open_collector"))
      (node (ref "D07") (pin "E2") (pinfunction "I$2_E2") (pintype "input"))
    )
    (net (code "545") (name "WTI+(WTX*TAD)+(WTX*ISZ)") (class "Default")
      (node (ref "A27") (pin "R2") (pinfunction "I$2_R2") (pintype "input"))
      (node (ref "C10") (pin "H2") (pinfunction "O$1_H2") (pintype "open_collector"))
      (node (ref "C10") (pin "J2") (pinfunction "P$1_J2") (pintype "passive"))
    )
    (net (code "546") (name "WTINCPC") (class "Default")
      (node (ref "A27") (pin "J2") (pinfunction "I$2_J2") (pintype "input"))
    )
    (net (code "547") (name "WTINCR") (class "Default")
      (node (ref "B25") (pin "R2") (pinfunction "I$2_R2") (pintype "input"))
    )
    (net (code "548") (name "WTINC_PC") (class "Default")
      (node (ref "C12") (pin "H2") (pinfunction "O$1_H2") (pintype "open_collector"))
      (node (ref "C12") (pin "J2") (pinfunction "P$1_J2") (pintype "passive"))
    )
    (net (code "549") (name "WTS") (class "Default")
      (node (ref "A05") (pin "H2") (pinfunction "I$1_H2") (pintype "input"))
      (node (ref "C04") (pin "J2") (pinfunction "J_J2") (pintype "input"))
      (node (ref "C08") (pin "V2") (pinfunction "F_V2") (pintype "open_collector"))
      (node (ref "E12") (pin "T2") (pinfunction "1_T2") (pintype "open_collector"))
    )
    (net (code "550") (name "WTX") (class "Default")
      (node (ref "A05") (pin "P2") (pinfunction "I$1_P2") (pintype "input"))
      (node (ref "A10") (pin "D2") (pinfunction "I$1_D2") (pintype "input"))
      (node (ref "A10") (pin "H2") (pinfunction "I$1_H2") (pintype "input"))
      (node (ref "A10") (pin "L2") (pinfunction "I$1_L2") (pintype "input"))
      (node (ref "A15") (pin "T2") (pinfunction "I$1_T2") (pintype "input"))
      (node (ref "A21") (pin "R2") (pinfunction "I$1_R2") (pintype "input"))
      (node (ref "A25") (pin "L2") (pinfunction "I$2_L2") (pintype "input"))
      (node (ref "A25") (pin "S2") (pinfunction "I$2_S2") (pintype "input"))
      (node (ref "A26") (pin "T2") (pinfunction "I$1_T2") (pintype "input"))
      (node (ref "B15") (pin "H2") (pinfunction "I$1_H2") (pintype "input"))
      (node (ref "B15") (pin "U2") (pinfunction "I$2_U2") (pintype "input"))
      (node (ref "B17") (pin "D2") (pinfunction "I$1_D2") (pintype "input"))
      (node (ref "B21") (pin "D2") (pinfunction "D_D2") (pintype "input"))
      (node (ref "C12") (pin "R2") (pinfunction "I$1_R2") (pintype "input"))
      (node (ref "C13") (pin "J2") (pinfunction "O$1_J2") (pintype "open_collector"))
      (node (ref "D06") (pin "H2") (pinfunction "I$1_H2") (pintype "input"))
      (node (ref "D07") (pin "L2") (pinfunction "I$1_L2") (pintype "input"))
      (node (ref "E10") (pin "U2") (pinfunction "I$2_U2") (pintype "input"))
      (node (ref "F18") (pin "M2") (pinfunction "I$1_M2") (pintype "input"))
    )
    (net (code "551") (name "WTX*(JMP+JMS)") (class "Default")
      (node (ref "A09") (pin "P2") (pinfunction "I$1_P2") (pintype "input"))
      (node (ref "A15") (pin "N2") (pinfunction "O$1_N2") (pintype "open_collector"))
      (node (ref "E13") (pin "D2") (pinfunction "I$1_D2") (pintype "input"))
    )
    (net (code "552") (name "WTX*DCA") (class "Default")
      (node (ref "B08") (pin "R2") (pinfunction "O$1_R2") (pintype "open_collector"))
      (node (ref "D08") (pin "R2") (pinfunction "I$2_R2") (pintype "input"))
    )
    (net (code "553") (name "WTX*ISZ") (class "Default")
      (node (ref "B08") (pin "N2") (pinfunction "O$1_N2") (pintype "open_collector"))
      (node (ref "D08") (pin "J2") (pinfunction "I$2_J2") (pintype "input"))
    )
    (net (code "554") (name "WTX*JMS") (class "Default")
      (node (ref "A09") (pin "D2") (pinfunction "O$1_D2") (pintype "open_collector"))
      (node (ref "A15") (pin "L2") (pinfunction "I$1_L2") (pintype "input"))
      (node (ref "D08") (pin "E2") (pinfunction "I$2_E2") (pintype "input"))
    )
    (net (code "555") (name "WTX*OP2") (class "Default")
      (node (ref "A18") (pin "J2") (pinfunction "O$1_J2") (pintype "open_collector"))
    )
    (net (code "556") (name "WTX*ROTR") (class "Default")
      (node (ref "A26") (pin "V2") (pinfunction "O$1_V2") (pintype "open_collector"))
    )
    (net (code "557") (name "WTX*TAD") (class "Default")
      (node (ref "A18") (pin "D2") (pinfunction "O$1_D2") (pintype "open_collector"))
      (node (ref "B25") (pin "M2") (pinfunction "I$2_M2") (pintype "input"))
    )
    (net (code "558") (name "WT_INCR") (class "Default")
      (node (ref "A14") (pin "H2") (pinfunction "O$1_H2") (pintype "open_collector"))
      (node (ref "A14") (pin "J2") (pinfunction "P$1_J2") (pintype "passive"))
    )
    (net (code "559") (name "Z1") (class "Default")
      (node (ref "B28") (pin "H2") (pinfunction "0_H2") (pintype "open_collector"))
      (node (ref "E11") (pin "U2") (pinfunction "I$2_U2") (pintype "input"))
    )
    (net (code "560") (name "ZI") (class "Default")
      (node (ref "F09") (pin "D2") (pinfunction "I$1_D2") (pintype "input"))
    )
    (net (code "561") (name "unconnected-(A01H-P$2-PadJ2)") (class "Default")
      (node (ref "A01") (pin "J2") (pinfunction "P$2_J2") (pintype "bidirectional"))
    )
    (net (code "562") (name "unconnected-(A09I-I$2-PadV2)") (class "Default")
      (node (ref "A09") (pin "V2") (pinfunction "I$2_V2") (pintype "passive"))
    )
    (net (code "563") (name "unconnected-(A12A-E-PadE2)") (class "Default")
      (node (ref "A12") (pin "E2") (pinfunction "E_E2") (pintype "input"))
    )
    (net (code "564") (name "unconnected-(A13F-D-PadP2)") (class "Default")
      (node (ref "A13") (pin "P2") (pinfunction "D_P2") (pintype "input"))
    )
    (net (code "565") (name "unconnected-(A15D-O$1-PadK2)") (class "Default")
      (node (ref "A15") (pin "K2") (pinfunction "O$1_K2") (pintype "open_collector"))
    )
    (net (code "566") (name "unconnected-(A16D-L-PadV2)") (class "Default")
      (node (ref "A16") (pin "V2") (pinfunction "L_V2") (pintype "input"))
    )
    (net (code "567") (name "unconnected-(A18I-I$2-PadV2)") (class "Default")
      (node (ref "A18") (pin "V2") (pinfunction "I$2_V2") (pintype "passive"))
    )
    (net (code "568") (name "unconnected-(A20D-I$1-PadP2)") (class "Default")
      (node (ref "A20") (pin "P2") (pinfunction "I$1_P2") (pintype "passive"))
    )
    (net (code "569") (name "unconnected-(A24I-I$2-PadV2)") (class "Default")
      (node (ref "A24") (pin "V2") (pinfunction "I$2_V2") (pintype "passive"))
    )
    (net (code "570") (name "unconnected-(A28C-D-PadD2)") (class "Default")
      (node (ref "A28") (pin "D2") (pinfunction "D_D2") (pintype "passive"))
    )
    (net (code "571") (name "unconnected-(A28C-L-PadL2)") (class "Default")
      (node (ref "A28") (pin "L2") (pinfunction "L_L2") (pintype "input"))
    )
    (net (code "572") (name "unconnected-(A28C-M-PadM2)") (class "Default")
      (node (ref "A28") (pin "M2") (pinfunction "M_M2") (pintype "passive"))
    )
    (net (code "573") (name "unconnected-(A29C-SET-PadM2)") (class "Default")
      (node (ref "A29") (pin "M2") (pinfunction "SET_M2") (pintype "passive"))
    )
    (net (code "574") (name "unconnected-(A30C-SET-PadM2)") (class "Default")
      (node (ref "A30") (pin "M2") (pinfunction "SET_M2") (pintype "passive"))
    )
    (net (code "575") (name "unconnected-(A31C-SET-PadM2)") (class "Default")
      (node (ref "A31") (pin "M2") (pinfunction "SET_M2") (pintype "passive"))
    )
    (net (code "576") (name "unconnected-(A32C-SET-PadM2)") (class "Default")
      (node (ref "A32") (pin "M2") (pinfunction "SET_M2") (pintype "passive"))
    )
    (net (code "577") (name "unconnected-(A34C-I$3-PadF2)") (class "Default")
      (node (ref "A34") (pin "F2") (pinfunction "I$3_F2") (pintype "passive"))
    )
    (net (code "578") (name "unconnected-(A36C-H-PadH2)") (class "Default")
      (node (ref "A36") (pin "H2") (pinfunction "H_H2") (pintype "passive"))
    )
    (net (code "579") (name "unconnected-(A36C-L-PadL2)") (class "Default")
      (node (ref "A36") (pin "L2") (pinfunction "L_L2") (pintype "passive"))
    )
    (net (code "580") (name "unconnected-(A36D-H-PadR2)") (class "Default")
      (node (ref "A36") (pin "R2") (pinfunction "H_R2") (pintype "passive"))
    )
    (net (code "581") (name "unconnected-(A36D-L-PadU2)") (class "Default")
      (node (ref "A36") (pin "U2") (pinfunction "L_U2") (pintype "passive"))
    )
    (net (code "582") (name "unconnected-(B03A-I$1-PadJ2)") (class "Default")
      (node (ref "B03") (pin "J2") (pinfunction "I$1_J2") (pintype "passive"))
    )
    (net (code "583") (name "unconnected-(B03D-I$1-PadP2)") (class "Default")
      (node (ref "B03") (pin "P2") (pinfunction "I$1_P2") (pintype "passive"))
    )
    (net (code "584") (name "unconnected-(B03E-I$1-PadV2)") (class "Default")
      (node (ref "B03") (pin "V2") (pinfunction "I$1_V2") (pintype "passive"))
    )
    (net (code "585") (name "unconnected-(B08I-I$2-PadV2)") (class "Default")
      (node (ref "B08") (pin "V2") (pinfunction "I$2_V2") (pintype "passive"))
    )
    (net (code "586") (name "unconnected-(B09C-0-PadH2)") (class "Default")
      (node (ref "B09") (pin "H2") (pinfunction "0_H2") (pintype "open_collector"))
    )
    (net (code "587") (name "unconnected-(B09C-RESET-PadF2)") (class "Default")
      (node (ref "B09") (pin "F2") (pinfunction "RESET_F2") (pintype "input"))
    )
    (net (code "588") (name "unconnected-(B09C-SET-PadM2)") (class "Default")
      (node (ref "B09") (pin "M2") (pinfunction "SET_M2") (pintype "passive"))
    )
    (net (code "589") (name "unconnected-(B10C-SET-PadM2)") (class "Default")
      (node (ref "B10") (pin "M2") (pinfunction "SET_M2") (pintype "passive"))
    )
    (net (code "590") (name "unconnected-(B11C-SET-PadM2)") (class "Default")
      (node (ref "B11") (pin "M2") (pinfunction "SET_M2") (pintype "passive"))
    )
    (net (code "591") (name "unconnected-(B11D-1-PadT2)") (class "Default")
      (node (ref "B11") (pin "T2") (pinfunction "1_T2") (pintype "open_collector"))
    )
    (net (code "592") (name "unconnected-(B12C-SET-PadM2)") (class "Default")
      (node (ref "B12") (pin "M2") (pinfunction "SET_M2") (pintype "passive"))
    )
    (net (code "593") (name "unconnected-(B14E-D-PadL2)") (class "Default")
      (node (ref "B14") (pin "L2") (pinfunction "D_L2") (pintype "input"))
    )
    (net (code "594") (name "unconnected-(B16I-I$2-PadV2)") (class "Default")
      (node (ref "B16") (pin "V2") (pinfunction "I$2_V2") (pintype "passive"))
    )
    (net (code "595") (name "unconnected-(B18E-I$1-PadV2)") (class "Default")
      (node (ref "B18") (pin "V2") (pinfunction "I$1_V2") (pintype "passive"))
    )
    (net (code "596") (name "unconnected-(B19E-I$1-PadV2)") (class "Default")
      (node (ref "B19") (pin "V2") (pinfunction "I$1_V2") (pintype "passive"))
    )
    (net (code "597") (name "unconnected-(B20C-I$1-PadD2)") (class "Default")
      (node (ref "B20") (pin "D2") (pinfunction "I$1_D2") (pintype "input"))
    )
    (net (code "598") (name "unconnected-(B21F-E-PadR2)") (class "Default")
      (node (ref "B21") (pin "R2") (pinfunction "E_R2") (pintype "input"))
    )
    (net (code "599") (name "unconnected-(B22D-I$1-PadP2)") (class "Default")
      (node (ref "B22") (pin "P2") (pinfunction "I$1_P2") (pintype "passive"))
    )
    (net (code "600") (name "unconnected-(B22E-I$1-PadV2)") (class "Default")
      (node (ref "B22") (pin "V2") (pinfunction "I$1_V2") (pintype "passive"))
    )
    (net (code "601") (name "unconnected-(B26G-E-PadU2)") (class "Default")
      (node (ref "B26") (pin "U2") (pinfunction "E_U2") (pintype "input"))
    )
    (net (code "602") (name "unconnected-(B27C-D-PadD2)") (class "Default")
      (node (ref "B27") (pin "D2") (pinfunction "D_D2") (pintype "passive"))
    )
    (net (code "603") (name "unconnected-(B27C-L-PadL2)") (class "Default")
      (node (ref "B27") (pin "L2") (pinfunction "L_L2") (pintype "input"))
    )
    (net (code "604") (name "unconnected-(B27C-M-PadM2)") (class "Default")
      (node (ref "B27") (pin "M2") (pinfunction "M_M2") (pintype "passive"))
    )
    (net (code "605") (name "unconnected-(B28C-SET-PadM2)") (class "Default")
      (node (ref "B28") (pin "M2") (pinfunction "SET_M2") (pintype "passive"))
    )
    (net (code "606") (name "unconnected-(B28D-RESET-PadR2)") (class "Default")
      (node (ref "B28") (pin "R2") (pinfunction "RESET_R2") (pintype "input"))
    )
    (net (code "607") (name "unconnected-(B29A-I$1-PadJ2)") (class "Default")
      (node (ref "B29") (pin "J2") (pinfunction "I$1_J2") (pintype "passive"))
    )
    (net (code "608") (name "unconnected-(B29D-I$1-PadP2)") (class "Default")
      (node (ref "B29") (pin "P2") (pinfunction "I$1_P2") (pintype "passive"))
    )
    (net (code "609") (name "unconnected-(B30A-I$1-PadJ2)") (class "Default")
      (node (ref "B30") (pin "J2") (pinfunction "I$1_J2") (pintype "passive"))
    )
    (net (code "610") (name "unconnected-(B30D-I$1-PadP2)") (class "Default")
      (node (ref "B30") (pin "P2") (pinfunction "I$1_P2") (pintype "passive"))
    )
    (net (code "611") (name "unconnected-(B30E-I$1-PadV2)") (class "Default")
      (node (ref "B30") (pin "V2") (pinfunction "I$1_V2") (pintype "passive"))
    )
    (net (code "612") (name "unconnected-(B31A-I$1-PadJ2)") (class "Default")
      (node (ref "B31") (pin "J2") (pinfunction "I$1_J2") (pintype "passive"))
    )
    (net (code "613") (name "unconnected-(B31D-I$1-PadP2)") (class "Default")
      (node (ref "B31") (pin "P2") (pinfunction "I$1_P2") (pintype "passive"))
    )
    (net (code "614") (name "unconnected-(B31E-I$1-PadV2)") (class "Default")
      (node (ref "B31") (pin "V2") (pinfunction "I$1_V2") (pintype "passive"))
    )
    (net (code "615") (name "unconnected-(B32A-F-PadF2)") (class "Default")
      (node (ref "B32") (pin "F2") (pinfunction "F_F2") (pintype "passive"))
    )
    (net (code "616") (name "unconnected-(B32A-H-PadH2)") (class "Default")
      (node (ref "B32") (pin "H2") (pinfunction "H_H2") (pintype "passive"))
    )
    (net (code "617") (name "unconnected-(B32A-L-PadL2)") (class "Default")
      (node (ref "B32") (pin "L2") (pinfunction "L_L2") (pintype "passive"))
    )
    (net (code "618") (name "unconnected-(B32A-M-PadM2)") (class "Default")
      (node (ref "B32") (pin "M2") (pinfunction "M_M2") (pintype "passive"))
    )
    (net (code "619") (name "unconnected-(B32A-N-PadN2)") (class "Default")
      (node (ref "B32") (pin "N2") (pinfunction "N_N2") (pintype "passive"))
    )
    (net (code "620") (name "unconnected-(B32A-P-PadP2)") (class "Default")
      (node (ref "B32") (pin "P2") (pinfunction "P_P2") (pintype "passive"))
    )
    (net (code "621") (name "unconnected-(B32A-T-PadT2)") (class "Default")
      (node (ref "B32") (pin "T2") (pinfunction "T_T2") (pintype "passive"))
    )
    (net (code "622") (name "unconnected-(B35C-SET-PadM2)") (class "Default")
      (node (ref "B35") (pin "M2") (pinfunction "SET_M2") (pintype "passive"))
    )
    (net (code "623") (name "unconnected-(B37I-I$2-PadV2)") (class "Default")
      (node (ref "B37") (pin "V2") (pinfunction "I$2_V2") (pintype "passive"))
    )
    (net (code "624") (name "unconnected-(C04C-E-PadE2)") (class "Default")
      (node (ref "C04") (pin "E2") (pinfunction "E_E2") (pintype "input"))
    )
    (net (code "625") (name "unconnected-(C04C-F-PadF2)") (class "Default")
      (node (ref "C04") (pin "F2") (pinfunction "F_F2") (pintype "input"))
    )
    (net (code "626") (name "unconnected-(C04C-L-PadL2)") (class "Default")
      (node (ref "C04") (pin "L2") (pinfunction "L_L2") (pintype "input"))
    )
    (net (code "627") (name "unconnected-(C05I-I$2-PadV2)") (class "Default")
      (node (ref "C05") (pin "V2") (pinfunction "I$2_V2") (pintype "passive"))
    )
    (net (code "628") (name "unconnected-(C07E-I$3-PadM2)") (class "Default")
      (node (ref "C07") (pin "M2") (pinfunction "I$3_M2") (pintype "passive"))
    )
    (net (code "629") (name "unconnected-(C07G-I$3-PadT2)") (class "Default")
      (node (ref "C07") (pin "T2") (pinfunction "I$3_T2") (pintype "passive"))
    )
    (net (code "630") (name "unconnected-(C08F-E-PadR2)") (class "Default")
      (node (ref "C08") (pin "R2") (pinfunction "E_R2") (pintype "input"))
    )
    (net (code "631") (name "unconnected-(C08G-E-PadU2)") (class "Default")
      (node (ref "C08") (pin "U2") (pinfunction "E_U2") (pintype "input"))
    )
    (net (code "632") (name "unconnected-(C09I-I$2-PadV2)") (class "Default")
      (node (ref "C09") (pin "V2") (pinfunction "I$2_V2") (pintype "passive"))
    )
    (net (code "633") (name "unconnected-(C13I-I$2-PadV2)") (class "Default")
      (node (ref "C13") (pin "V2") (pinfunction "I$2_V2") (pintype "passive"))
    )
    (net (code "634") (name "unconnected-(C21I-I$2-PadV2)") (class "Default")
      (node (ref "C21") (pin "V2") (pinfunction "I$2_V2") (pintype "passive"))
    )
    (net (code "635") (name "unconnected-(C24I-I$2-PadV2)") (class "Default")
      (node (ref "C24") (pin "V2") (pinfunction "I$2_V2") (pintype "passive"))
    )
    (net (code "636") (name "unconnected-(C37E-I$1-PadV2)") (class "Default")
      (node (ref "C37") (pin "V2") (pinfunction "I$1_V2") (pintype "passive"))
    )
    (net (code "637") (name "unconnected-(C38D-L-PadV2)") (class "Default")
      (node (ref "C38") (pin "V2") (pinfunction "L_V2") (pintype "input"))
    )
    (net (code "638") (name "unconnected-(C39G-S-PadS2)") (class "Default")
      (node (ref "C39") (pin "S2") (pinfunction "S_S2") (pintype "passive"))
    )
    (net (code "639") (name "unconnected-(D06A-I$2-PadE2)") (class "Default")
      (node (ref "D06") (pin "E2") (pinfunction "I$2_E2") (pintype "input"))
    )
    (net (code "640") (name "unconnected-(D06AG-I$1-PadT2)") (class "Default")
      (node (ref "D06A") (pin "T2") (pinfunction "I$1_T2") (pintype "input"))
    )
    (net (code "641") (name "unconnected-(D06AG-I$2-PadU2)") (class "Default")
      (node (ref "D06A") (pin "U2") (pinfunction "I$2_U2") (pintype "input"))
    )
    (net (code "642") (name "unconnected-(D06AG-O$1-PadV2)") (class "Default")
      (node (ref "D06A") (pin "V2") (pinfunction "O$1_V2") (pintype "open_collector"))
    )
    (net (code "643") (name "unconnected-(D06G-I$2-PadU2)") (class "Default")
      (node (ref "D06") (pin "U2") (pinfunction "I$2_U2") (pintype "input"))
    )
    (net (code "644") (name "unconnected-(D09A-I$1-PadJ2)") (class "Default")
      (node (ref "D09") (pin "J2") (pinfunction "I$1_J2") (pintype "passive"))
    )
    (net (code "645") (name "unconnected-(D09D-I$1-PadP2)") (class "Default")
      (node (ref "D09") (pin "P2") (pinfunction "I$1_P2") (pintype "passive"))
    )
    (net (code "646") (name "unconnected-(D09E-I$1-PadV2)") (class "Default")
      (node (ref "D09") (pin "V2") (pinfunction "I$1_V2") (pintype "passive"))
    )
    (net (code "647") (name "unconnected-(D10A-I$1-PadJ2)") (class "Default")
      (node (ref "D10") (pin "J2") (pinfunction "I$1_J2") (pintype "passive"))
    )
    (net (code "648") (name "unconnected-(D10D-I$1-PadP2)") (class "Default")
      (node (ref "D10") (pin "P2") (pinfunction "I$1_P2") (pintype "passive"))
    )
    (net (code "649") (name "unconnected-(D10E-I$1-PadV2)") (class "Default")
      (node (ref "D10") (pin "V2") (pinfunction "I$1_V2") (pintype "passive"))
    )
    (net (code "650") (name "unconnected-(D18I-I$2-PadV2)") (class "Default")
      (node (ref "D18") (pin "V2") (pinfunction "I$2_V2") (pintype "passive"))
    )
    (net (code "651") (name "unconnected-(D19C-SET-PadM2)") (class "Default")
      (node (ref "D19") (pin "M2") (pinfunction "SET_M2") (pintype "passive"))
    )
    (net (code "652") (name "unconnected-(D20C-SET-PadM2)") (class "Default")
      (node (ref "D20") (pin "M2") (pinfunction "SET_M2") (pintype "passive"))
    )
    (net (code "653") (name "unconnected-(E05C-P-PadP2)") (class "Default")
      (node (ref "E05") (pin "P2") (pinfunction "P_P2") (pintype "input"))
    )
    (net (code "654") (name "unconnected-(E06C-RESET-PadF2)") (class "Default")
      (node (ref "E06") (pin "F2") (pinfunction "RESET_F2") (pintype "input"))
    )
    (net (code "655") (name "unconnected-(E06C-SET-PadM2)") (class "Default")
      (node (ref "E06") (pin "M2") (pinfunction "SET_M2") (pintype "passive"))
    )
    (net (code "656") (name "unconnected-(E06D-RESET-PadR2)") (class "Default")
      (node (ref "E06") (pin "R2") (pinfunction "RESET_R2") (pintype "input"))
    )
    (net (code "657") (name "unconnected-(E09D-I$2-PadJ2)") (class "Default")
      (node (ref "E09") (pin "J2") (pinfunction "I$2_J2") (pintype "input"))
    )
    (net (code "658") (name "unconnected-(E11F-I$1-PadP2)") (class "Default")
      (node (ref "E11") (pin "P2") (pinfunction "I$1_P2") (pintype "input"))
    )
    (net (code "659") (name "unconnected-(E12C-RESET-PadF2)") (class "Default")
      (node (ref "E12") (pin "F2") (pinfunction "RESET_F2") (pintype "input"))
    )
    (net (code "660") (name "unconnected-(E12C-SET-PadM2)") (class "Default")
      (node (ref "E12") (pin "M2") (pinfunction "SET_M2") (pintype "passive"))
    )
    (net (code "661") (name "unconnected-(E15C-RESET-PadF2)") (class "Default")
      (node (ref "E15") (pin "F2") (pinfunction "RESET_F2") (pintype "input"))
    )
    (net (code "662") (name "unconnected-(E15C-SET-PadM2)") (class "Default")
      (node (ref "E15") (pin "M2") (pinfunction "SET_M2") (pintype "passive"))
    )
    (net (code "663") (name "unconnected-(E15D-RESET-PadR2)") (class "Default")
      (node (ref "E15") (pin "R2") (pinfunction "RESET_R2") (pintype "input"))
    )
    (net (code "664") (name "unconnected-(E16C-RESET-PadF2)") (class "Default")
      (node (ref "E16") (pin "F2") (pinfunction "RESET_F2") (pintype "input"))
    )
    (net (code "665") (name "unconnected-(E16C-SET-PadM2)") (class "Default")
      (node (ref "E16") (pin "M2") (pinfunction "SET_M2") (pintype "passive"))
    )
    (net (code "666") (name "unconnected-(E16D-RESET-PadR2)") (class "Default")
      (node (ref "E16") (pin "R2") (pinfunction "RESET_R2") (pintype "input"))
    )
    (net (code "667") (name "unconnected-(E17C-RESET-PadF2)") (class "Default")
      (node (ref "E17") (pin "F2") (pinfunction "RESET_F2") (pintype "input"))
    )
    (net (code "668") (name "unconnected-(E17C-SET-PadM2)") (class "Default")
      (node (ref "E17") (pin "M2") (pinfunction "SET_M2") (pintype "passive"))
    )
    (net (code "669") (name "unconnected-(E17D-RESET-PadR2)") (class "Default")
      (node (ref "E17") (pin "R2") (pinfunction "RESET_R2") (pintype "input"))
    )
    (net (code "670") (name "unconnected-(E18C-RESET-PadF2)") (class "Default")
      (node (ref "E18") (pin "F2") (pinfunction "RESET_F2") (pintype "input"))
    )
    (net (code "671") (name "unconnected-(E18C-SET-PadM2)") (class "Default")
      (node (ref "E18") (pin "M2") (pinfunction "SET_M2") (pintype "passive"))
    )
    (net (code "672") (name "unconnected-(E18D-RESET-PadR2)") (class "Default")
      (node (ref "E18") (pin "R2") (pinfunction "RESET_R2") (pintype "input"))
    )
    (net (code "673") (name "unconnected-(E19C-RESET-PadF2)") (class "Default")
      (node (ref "E19") (pin "F2") (pinfunction "RESET_F2") (pintype "input"))
    )
    (net (code "674") (name "unconnected-(E19C-SET-PadM2)") (class "Default")
      (node (ref "E19") (pin "M2") (pinfunction "SET_M2") (pintype "passive"))
    )
    (net (code "675") (name "unconnected-(E19D-RESET-PadR2)") (class "Default")
      (node (ref "E19") (pin "R2") (pinfunction "RESET_R2") (pintype "input"))
    )
    (net (code "676") (name "unconnected-(E20C-RESET-PadF2)") (class "Default")
      (node (ref "E20") (pin "F2") (pinfunction "RESET_F2") (pintype "input"))
    )
    (net (code "677") (name "unconnected-(E20C-SET-PadM2)") (class "Default")
      (node (ref "E20") (pin "M2") (pinfunction "SET_M2") (pintype "passive"))
    )
    (net (code "678") (name "unconnected-(E20D-RESET-PadR2)") (class "Default")
      (node (ref "E20") (pin "R2") (pinfunction "RESET_R2") (pintype "input"))
    )
    (net (code "679") (name "unconnected-(F05D-0-PadS2)") (class "Default")
      (node (ref "F05") (pin "S2") (pinfunction "0_S2") (pintype "open_collector"))
    )
    (net (code "680") (name "unconnected-(F05D-RESET-PadR2)") (class "Default")
      (node (ref "F05") (pin "R2") (pinfunction "RESET_R2") (pintype "input"))
    )
    (net (code "681") (name "unconnected-(F07G-I$3-PadT2)") (class "Default")
      (node (ref "F07") (pin "T2") (pinfunction "I$3_T2") (pintype "passive"))
    )
    (net (code "682") (name "unconnected-(F08G-I$3-PadT2)") (class "Default")
      (node (ref "F08") (pin "T2") (pinfunction "I$3_T2") (pintype "passive"))
    )
    (net (code "683") (name "unconnected-(F09C-I$3-PadF2)") (class "Default")
      (node (ref "F09") (pin "F2") (pinfunction "I$3_F2") (pintype "passive"))
    )
    (net (code "684") (name "unconnected-(F10I-I$2-PadV2)") (class "Default")
      (node (ref "F10") (pin "V2") (pinfunction "I$2_V2") (pintype "passive"))
    )
    (net (code "685") (name "unconnected-(F11I-I$2-PadV2)") (class "Default")
      (node (ref "F11") (pin "V2") (pinfunction "I$2_V2") (pintype "passive"))
    )
    (net (code "686") (name "unconnected-(F12I-I$2-PadV2)") (class "Default")
      (node (ref "F12") (pin "V2") (pinfunction "I$2_V2") (pintype "passive"))
    )
    (net (code "687") (name "unconnected-(F13I-I$2-PadV2)") (class "Default")
      (node (ref "F13") (pin "V2") (pinfunction "I$2_V2") (pintype "passive"))
    )
    (net (code "688") (name "unconnected-(F15C-I$3-PadF2)") (class "Default")
      (node (ref "F15") (pin "F2") (pinfunction "I$3_F2") (pintype "passive"))
    )
    (net (code "689") (name "unconnected-(F18I-I$2-PadV2)") (class "Default")
      (node (ref "F18") (pin "V2") (pinfunction "I$2_V2") (pintype "passive"))
    )
    (net (code "690") (name "unconnected-(F19I-I$2-PadV2)") (class "Default")
      (node (ref "F19") (pin "V2") (pinfunction "I$2_V2") (pintype "passive"))
    )
    (net (code "691") (name "unconnected-(F20I-I$2-PadV2)") (class "Default")
      (node (ref "F20") (pin "V2") (pinfunction "I$2_V2") (pintype "passive"))
    )
    (net (code "692") (name "unconnected-(F22AP-P$1-PadU2)") (class "Default")
      (node (ref "F22A") (pin "U2") (pinfunction "P$1_U2") (pintype "passive"))
    )
    (net (code "693") (name "unconnected-(F37D-L-PadV2)") (class "Default")
      (node (ref "F37") (pin "V2") (pinfunction "L_V2") (pintype "input"))
    )
    (net (code "694") (name "unconnected-(F38D-E-PadP2)") (class "Default")
      (node (ref "F38") (pin "P2") (pinfunction "E_P2") (pintype "input"))
    )
    (net (code "695") (name "unconnected-(F38D-F-PadR2)") (class "Default")
      (node (ref "F38") (pin "R2") (pinfunction "F_R2") (pintype "input"))
    )
    (net (code "696") (name "unconnected-(F38D-L-PadV2)") (class "Default")
      (node (ref "F38") (pin "V2") (pinfunction "L_V2") (pintype "input"))
    )
    (net (code "697") (name "unconnected-(F39D-E-PadP2)") (class "Default")
      (node (ref "F39") (pin "P2") (pinfunction "E_P2") (pintype "input"))
    )
    (net (code "698") (name "unconnected-(F39D-F-PadR2)") (class "Default")
      (node (ref "F39") (pin "R2") (pinfunction "F_R2") (pintype "input"))
    )
    (net (code "699") (name "unconnected-(F39D-L-PadV2)") (class "Default")
      (node (ref "F39") (pin "V2") (pinfunction "L_V2") (pintype "input"))
    )
    (net (code "700") (name "~{RAMA00}") (class "Default")
      (node (ref "D21") (pin "D2") (pinfunction "OUT_D2") (pintype "output"))
      (node (ref "D28") (pin "D2") (pinfunction "P$2_D2") (pintype "bidirectional"))
    )
    (net (code "701") (name "~{RAMA01}") (class "Default")
      (node (ref "D21") (pin "F2") (pinfunction "OUT_F2") (pintype "output"))
      (node (ref "D28") (pin "E2") (pinfunction "P$2_E2") (pintype "bidirectional"))
    )
    (net (code "702") (name "~{RAMA02}") (class "Default")
      (node (ref "D21") (pin "J2") (pinfunction "OUT_J2") (pintype "output"))
      (node (ref "D28") (pin "F2") (pinfunction "P$2_F2") (pintype "bidirectional"))
    )
    (net (code "703") (name "~{RAMA03}") (class "Default")
      (node (ref "D21") (pin "L2") (pinfunction "OUT_L2") (pintype "output"))
      (node (ref "D28") (pin "H2") (pinfunction "P$2_H2") (pintype "bidirectional"))
    )
    (net (code "704") (name "~{RAMA04}") (class "Default")
      (node (ref "D21") (pin "N2") (pinfunction "OUT_N2") (pintype "output"))
      (node (ref "D28") (pin "J2") (pinfunction "P$2_J2") (pintype "bidirectional"))
    )
    (net (code "705") (name "~{RAMA05}") (class "Default")
      (node (ref "D21") (pin "R2") (pinfunction "OUT_R2") (pintype "output"))
      (node (ref "D28") (pin "K2") (pinfunction "P$2_K2") (pintype "bidirectional"))
    )
    (net (code "706") (name "~{RAMA06}") (class "Default")
      (node (ref "D22") (pin "D2") (pinfunction "OUT_D2") (pintype "output"))
      (node (ref "D28") (pin "L2") (pinfunction "P$2_L2") (pintype "bidirectional"))
    )
    (net (code "707") (name "~{RAMA07}") (class "Default")
      (node (ref "D22") (pin "F2") (pinfunction "OUT_F2") (pintype "output"))
      (node (ref "D28") (pin "M2") (pinfunction "P$2_M2") (pintype "bidirectional"))
    )
    (net (code "708") (name "~{RAMA08}") (class "Default")
      (node (ref "D22") (pin "J2") (pinfunction "OUT_J2") (pintype "output"))
      (node (ref "D28") (pin "N2") (pinfunction "P$2_N2") (pintype "bidirectional"))
    )
    (net (code "709") (name "~{RAMA09}") (class "Default")
      (node (ref "D22") (pin "L2") (pinfunction "OUT_L2") (pintype "output"))
      (node (ref "D28") (pin "P2") (pinfunction "P$2_P2") (pintype "bidirectional"))
    )
    (net (code "710") (name "~{RAMA10}") (class "Default")
      (node (ref "D22") (pin "N2") (pinfunction "OUT_N2") (pintype "output"))
      (node (ref "D28") (pin "R2") (pinfunction "P$2_R2") (pintype "bidirectional"))
    )
    (net (code "711") (name "~{RAMA11}") (class "Default")
      (node (ref "D22") (pin "R2") (pinfunction "OUT_R2") (pintype "output"))
      (node (ref "D28") (pin "S2") (pinfunction "P$2_S2") (pintype "bidirectional"))
    )
    (net (code "712") (name "~{RAMA12}") (class "Default")
      (node (ref "D27") (pin "D2") (pinfunction "OUT_D2") (pintype "output"))
      (node (ref "D28") (pin "T2") (pinfunction "P$2_T2") (pintype "bidirectional"))
    )
    (net (code "713") (name "~{RAMA13}") (class "Default")
      (node (ref "D27") (pin "F2") (pinfunction "OUT_F2") (pintype "output"))
      (node (ref "D28") (pin "U2") (pinfunction "P$2_U2") (pintype "bidirectional"))
    )
    (net (code "714") (name "~{RAMA14}") (class "Default")
      (node (ref "D27") (pin "J2") (pinfunction "OUT_J2") (pintype "output"))
      (node (ref "D28") (pin "V2") (pinfunction "P$2_V2") (pintype "bidirectional"))
    )
    (net (code "715") (name "~{RD}") (class "Default")
      (node (ref "C28") (pin "V2") (pinfunction "P$2_V2") (pintype "bidirectional"))
      (node (ref "D27") (pin "N2") (pinfunction "OUT_N2") (pintype "output"))
    )
    (net (code "716") (name "~{WR}") (class "Default")
      (node (ref "C28") (pin "U2") (pinfunction "P$2_U2") (pintype "bidirectional"))
      (node (ref "D27") (pin "L2") (pinfunction "OUT_L2") (pintype "output"))
    )
  )
)
